# TestBoardTarget.net
KiCad netlist of a schematic drawn in EAGLE
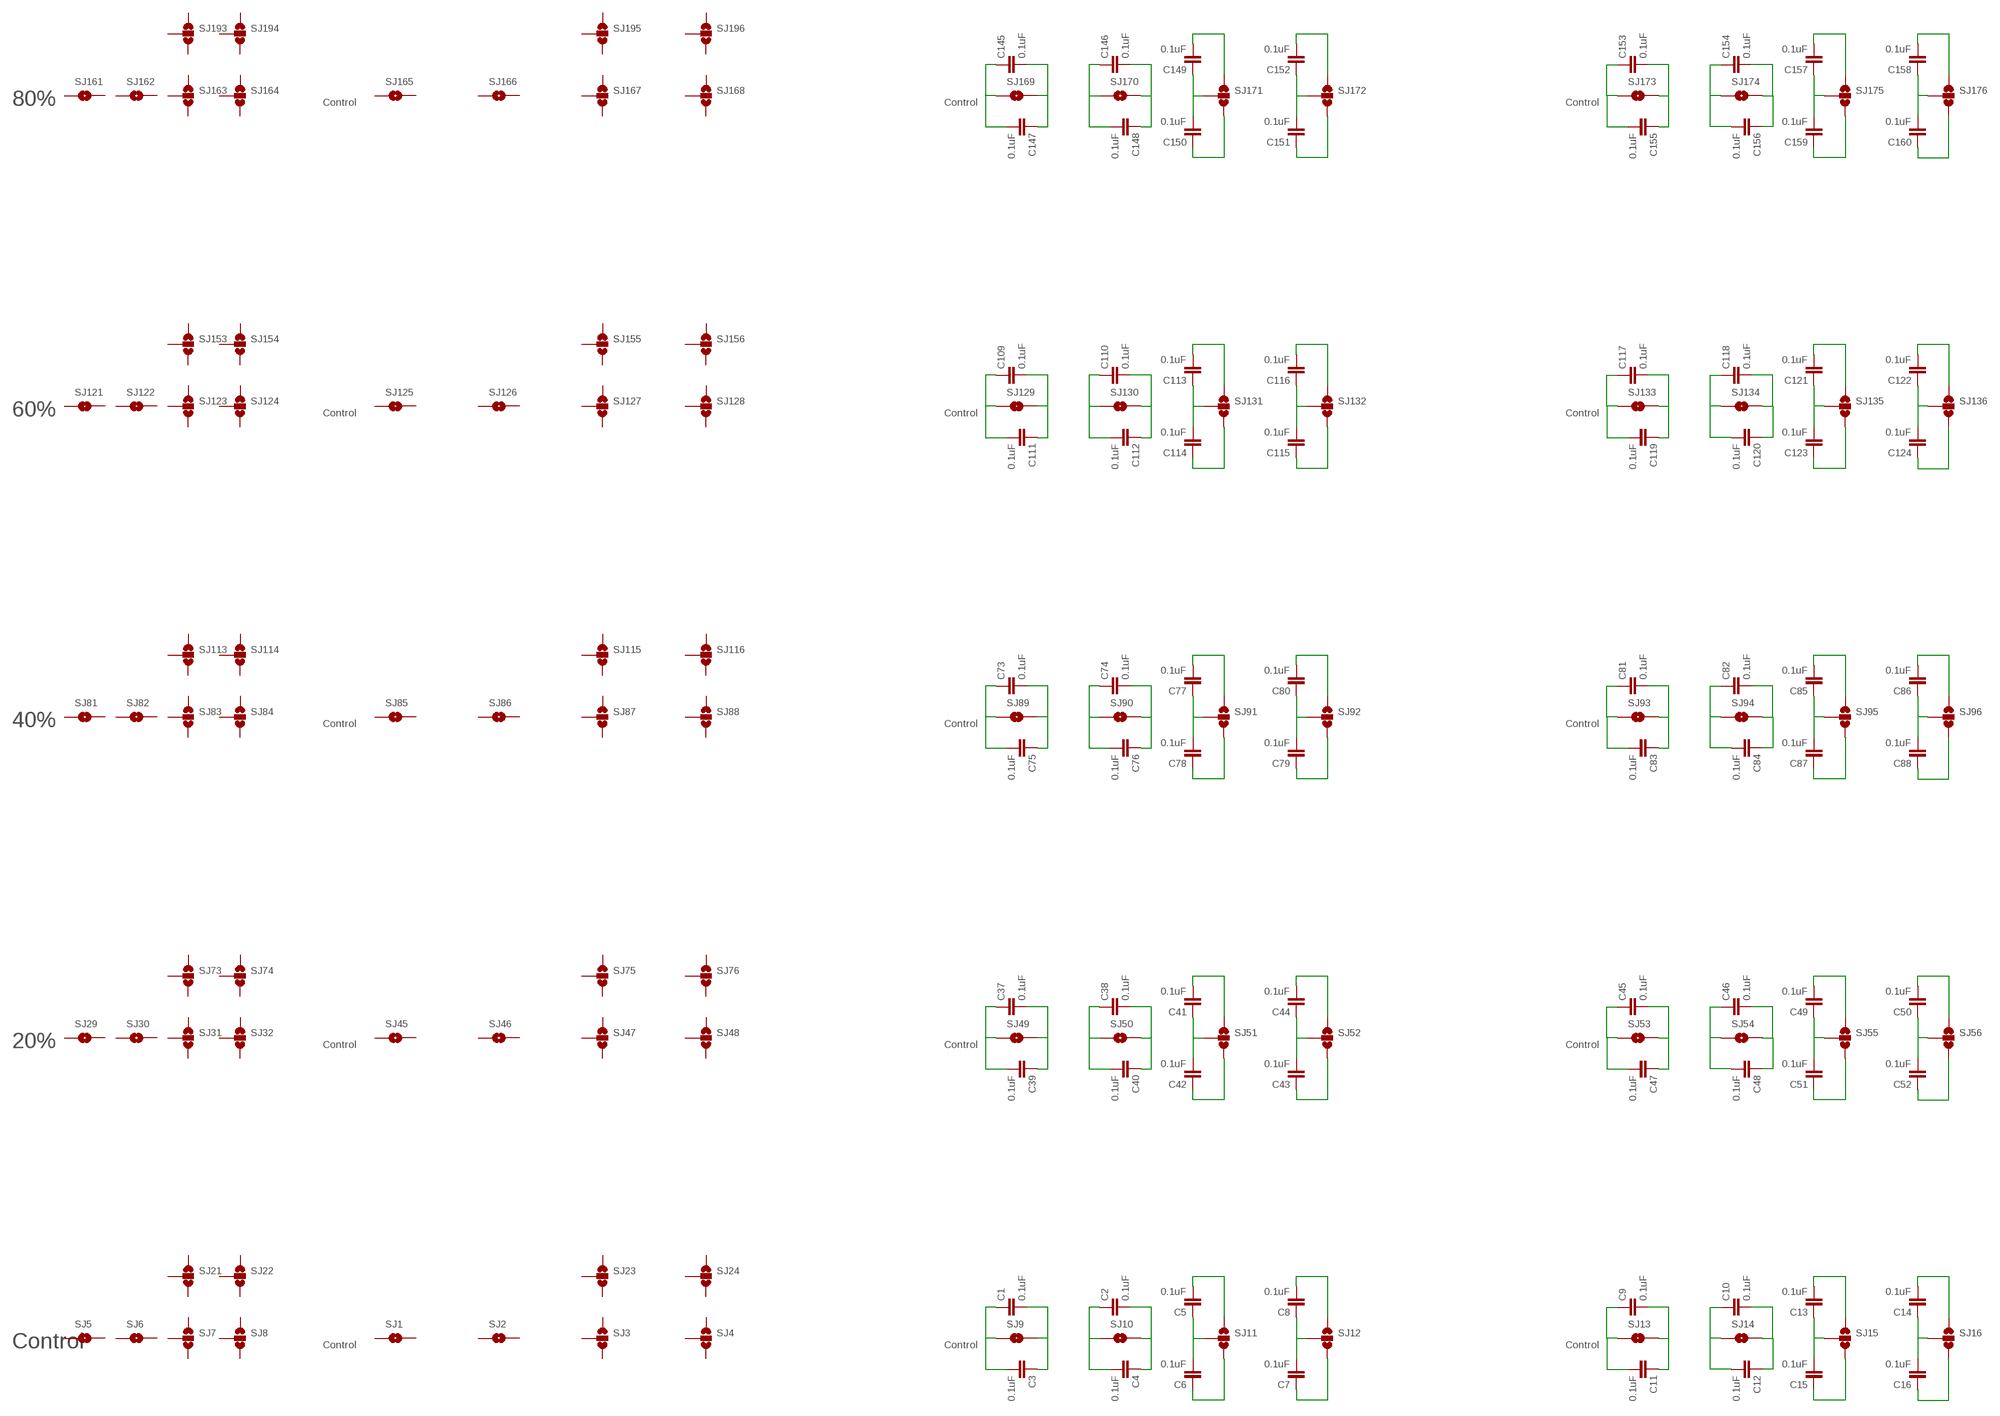
[diagram p0: schematic, sheet 1, part 1 of 3]
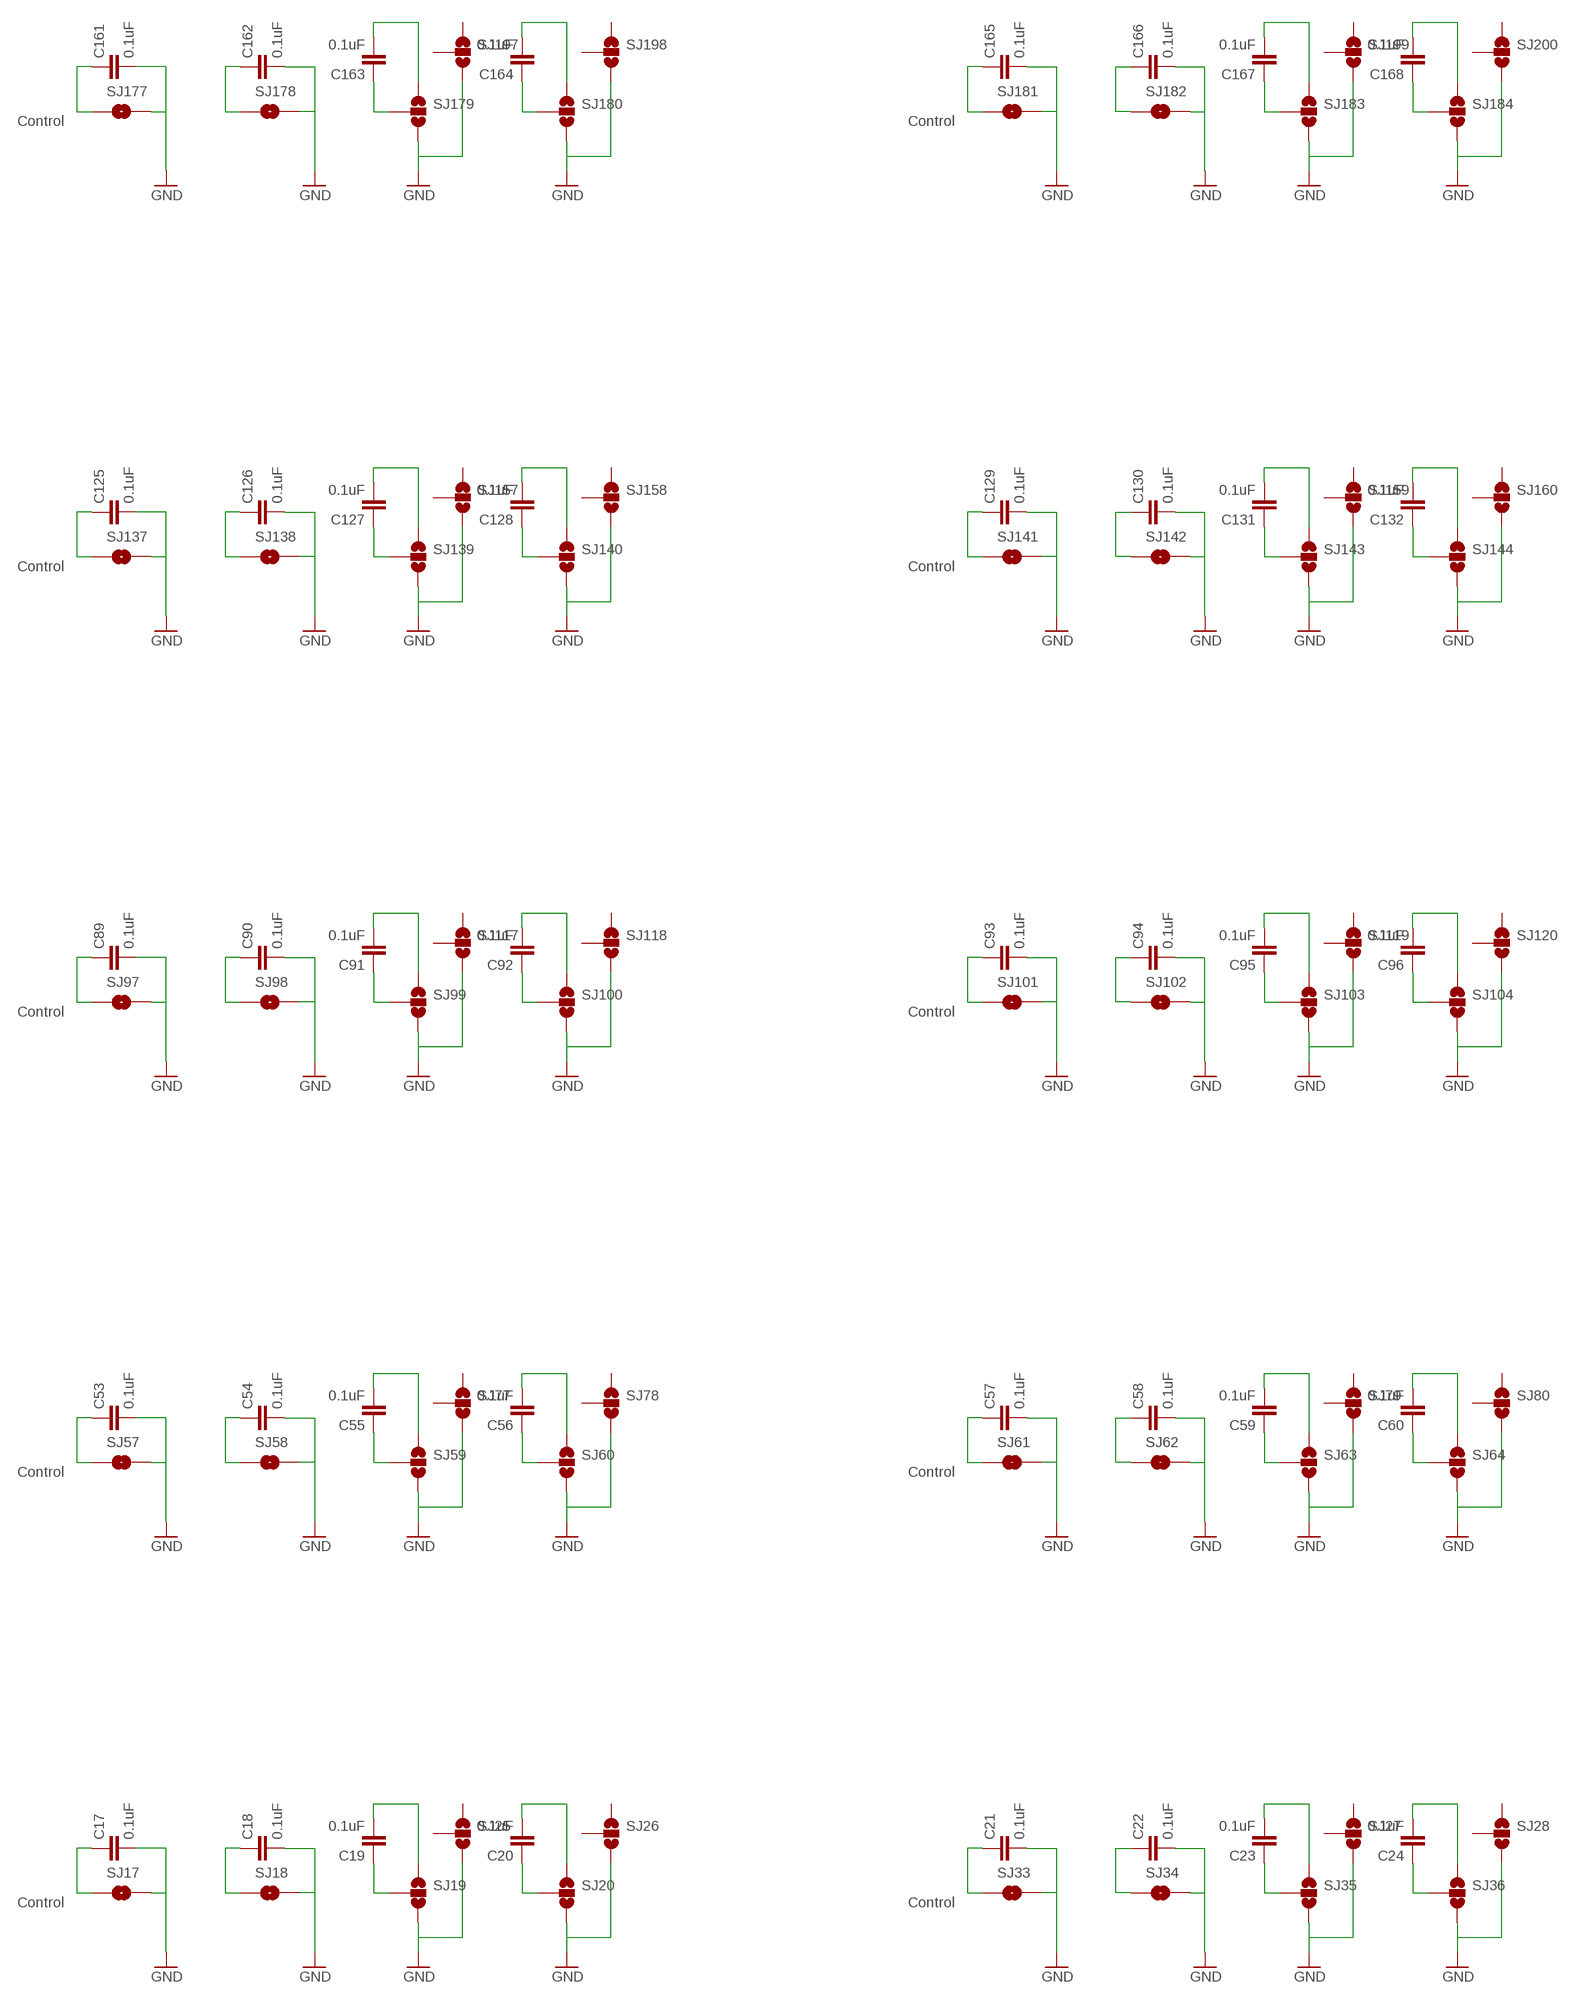
[diagram p1: schematic, sheet 1, part 2 of 3]
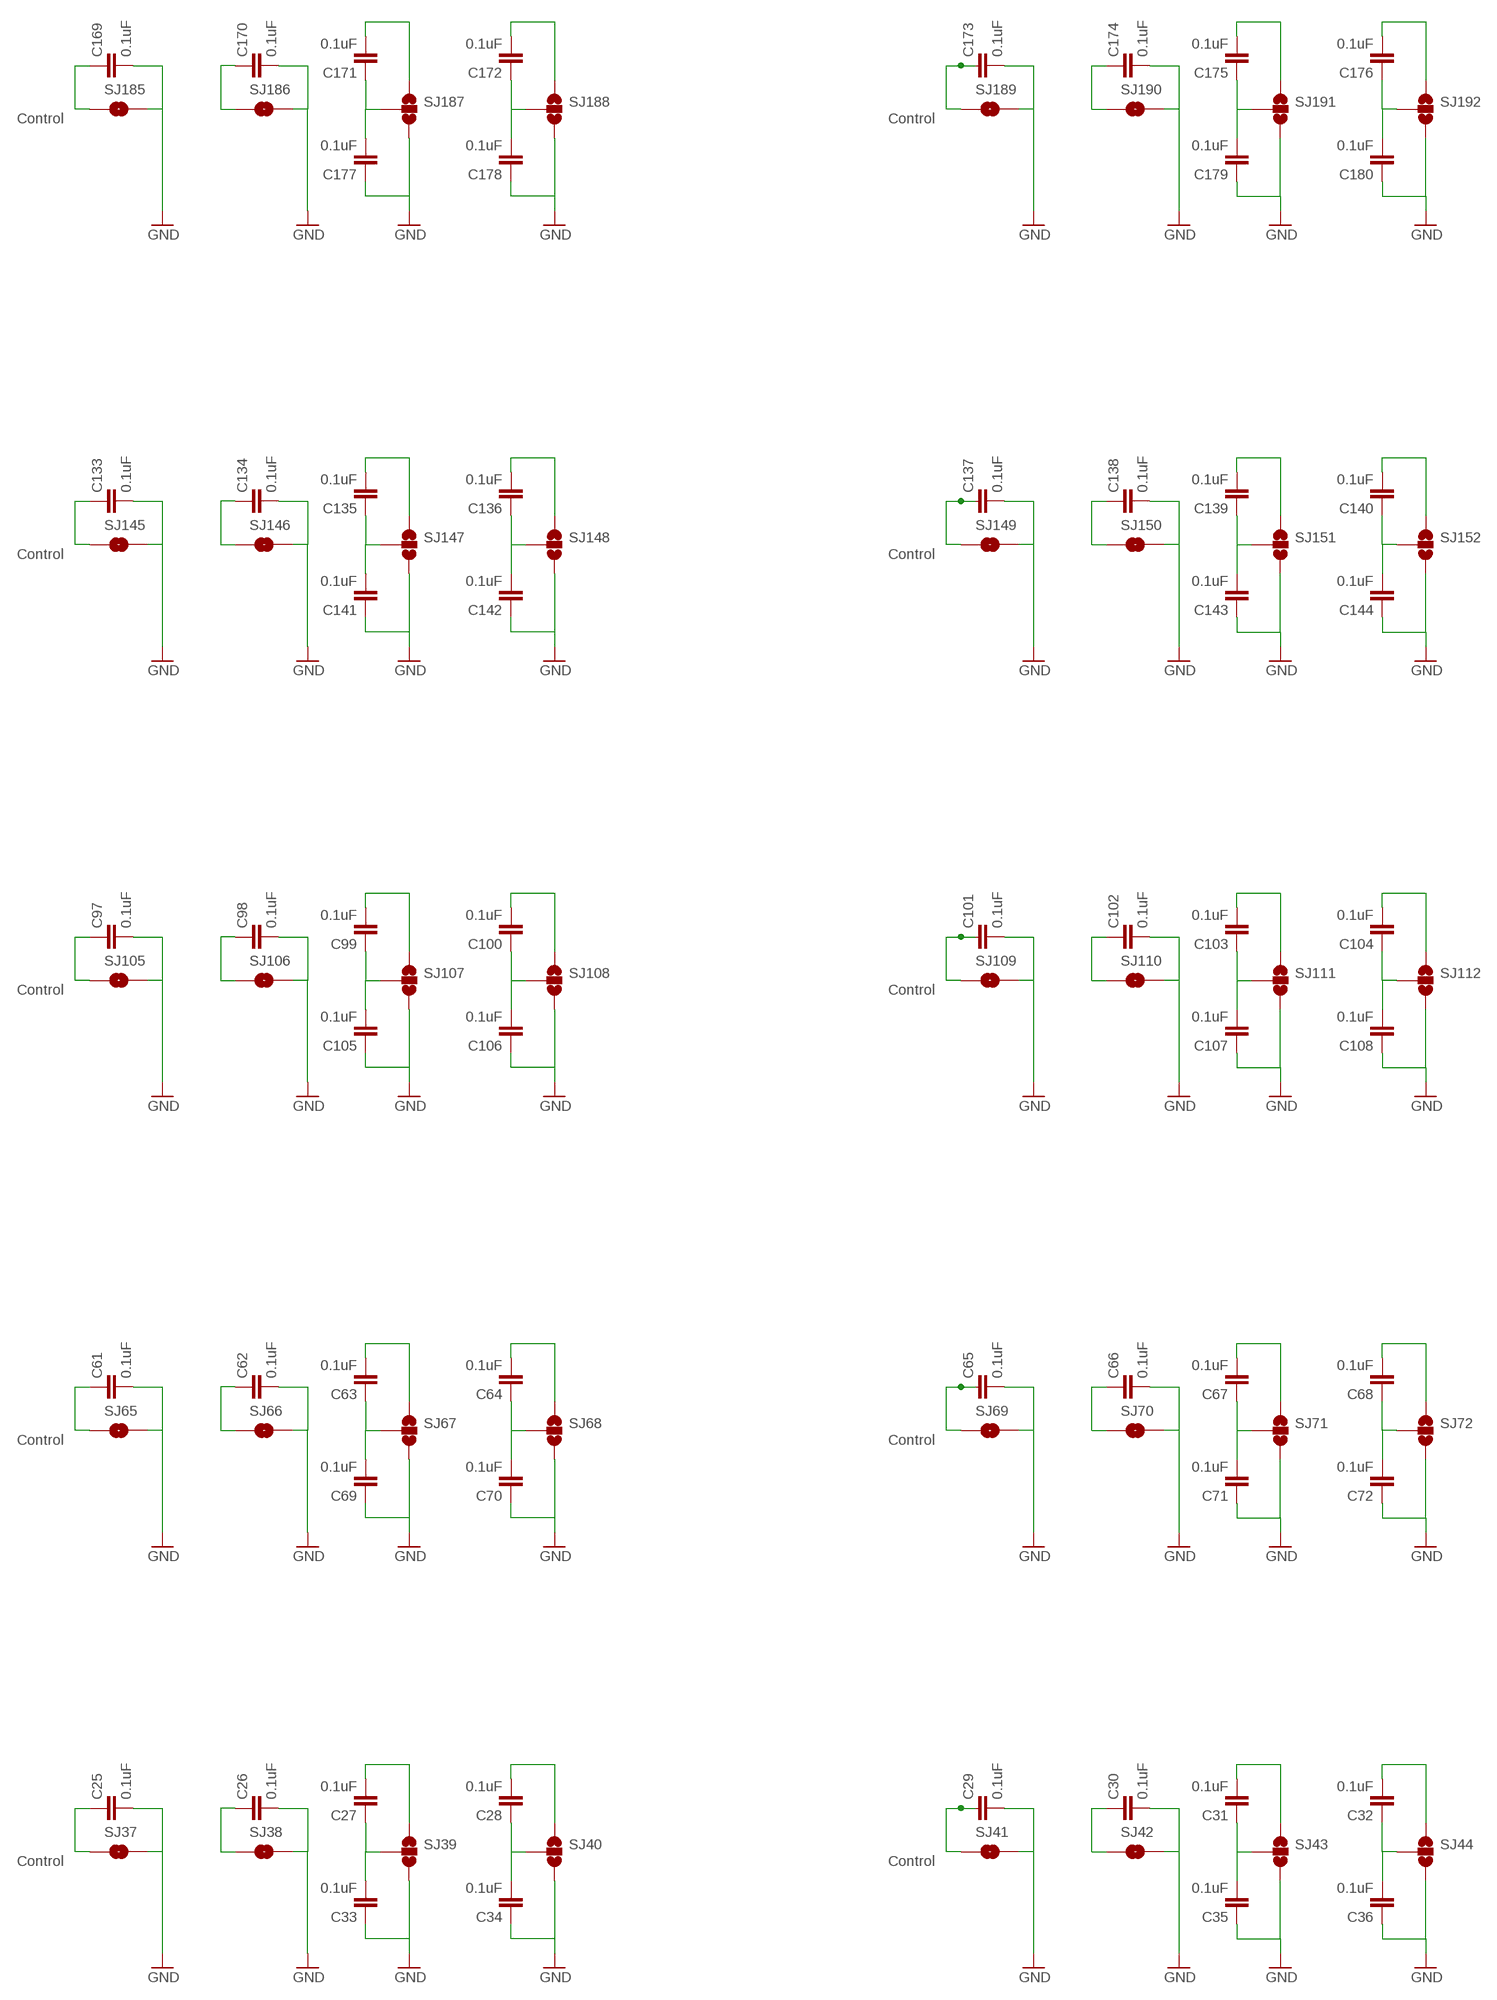
[diagram p2: schematic, sheet 1, part 3 of 3]

(export (version "E")
  (design (tool "Eeschema 10.0.6"))
  (components
    (comp (ref "C1")
      (value "0.1uF")
      (footprint "eagle-import:0603-CAP")
      (libsource (lib "eagle-import") (part "0.1UF-25V-5%(0603)"))
    )
    (comp (ref "C2")
      (value "0.1uF")
      (footprint "eagle-import:0603-CAP")
      (libsource (lib "eagle-import") (part "0.1UF-25V-5%(0603)"))
    )
    (comp (ref "C3")
      (value "0.1uF")
      (footprint "eagle-import:0603-CAP")
      (libsource (lib "eagle-import") (part "0.1UF-25V-5%(0603)"))
    )
    (comp (ref "C4")
      (value "0.1uF")
      (footprint "eagle-import:0603-CAP")
      (libsource (lib "eagle-import") (part "0.1UF-25V-5%(0603)"))
    )
    (comp (ref "C5")
      (value "0.1uF")
      (footprint "eagle-import:0603-CAP")
      (libsource (lib "eagle-import") (part "0.1UF-25V-5%(0603)"))
    )
    (comp (ref "C6")
      (value "0.1uF")
      (footprint "eagle-import:0603-CAP")
      (libsource (lib "eagle-import") (part "0.1UF-25V-5%(0603)"))
    )
    (comp (ref "C7")
      (value "0.1uF")
      (footprint "eagle-import:0603-CAP")
      (libsource (lib "eagle-import") (part "0.1UF-25V-5%(0603)"))
    )
    (comp (ref "C8")
      (value "0.1uF")
      (footprint "eagle-import:0603-CAP")
      (libsource (lib "eagle-import") (part "0.1UF-25V-5%(0603)"))
    )
    (comp (ref "C9")
      (value "0.1uF")
      (footprint "eagle-import:0603-CAP")
      (libsource (lib "eagle-import") (part "0.1UF-25V-5%(0603)"))
    )
    (comp (ref "C10")
      (value "0.1uF")
      (footprint "eagle-import:0603-CAP")
      (libsource (lib "eagle-import") (part "0.1UF-25V-5%(0603)"))
    )
    (comp (ref "C11")
      (value "0.1uF")
      (footprint "eagle-import:0603-CAP")
      (libsource (lib "eagle-import") (part "0.1UF-25V-5%(0603)"))
    )
    (comp (ref "C12")
      (value "0.1uF")
      (footprint "eagle-import:0603-CAP")
      (libsource (lib "eagle-import") (part "0.1UF-25V-5%(0603)"))
    )
    (comp (ref "C13")
      (value "0.1uF")
      (footprint "eagle-import:0603-CAP")
      (libsource (lib "eagle-import") (part "0.1UF-25V-5%(0603)"))
    )
    (comp (ref "C14")
      (value "0.1uF")
      (footprint "eagle-import:0603-CAP")
      (libsource (lib "eagle-import") (part "0.1UF-25V-5%(0603)"))
    )
    (comp (ref "C15")
      (value "0.1uF")
      (footprint "eagle-import:0603-CAP")
      (libsource (lib "eagle-import") (part "0.1UF-25V-5%(0603)"))
    )
    (comp (ref "C16")
      (value "0.1uF")
      (footprint "eagle-import:0603-CAP")
      (libsource (lib "eagle-import") (part "0.1UF-25V-5%(0603)"))
    )
    (comp (ref "C17")
      (value "0.1uF")
      (footprint "eagle-import:0603-CAP")
      (libsource (lib "eagle-import") (part "0.1UF-25V-5%(0603)"))
    )
    (comp (ref "C18")
      (value "0.1uF")
      (footprint "eagle-import:0603-CAP")
      (libsource (lib "eagle-import") (part "0.1UF-25V-5%(0603)"))
    )
    (comp (ref "C19")
      (value "0.1uF")
      (footprint "eagle-import:0603-CAP")
      (libsource (lib "eagle-import") (part "0.1UF-25V-5%(0603)"))
    )
    (comp (ref "C20")
      (value "0.1uF")
      (footprint "eagle-import:0603-CAP")
      (libsource (lib "eagle-import") (part "0.1UF-25V-5%(0603)"))
    )
    (comp (ref "C21")
      (value "0.1uF")
      (footprint "eagle-import:0603-CAP")
      (libsource (lib "eagle-import") (part "0.1UF-25V-5%(0603)"))
    )
    (comp (ref "C22")
      (value "0.1uF")
      (footprint "eagle-import:0603-CAP")
      (libsource (lib "eagle-import") (part "0.1UF-25V-5%(0603)"))
    )
    (comp (ref "C23")
      (value "0.1uF")
      (footprint "eagle-import:0603-CAP")
      (libsource (lib "eagle-import") (part "0.1UF-25V-5%(0603)"))
    )
    (comp (ref "C24")
      (value "0.1uF")
      (footprint "eagle-import:0603-CAP")
      (libsource (lib "eagle-import") (part "0.1UF-25V-5%(0603)"))
    )
    (comp (ref "C25")
      (value "0.1uF")
      (footprint "eagle-import:0603-CAP")
      (libsource (lib "eagle-import") (part "0.1UF-25V-5%(0603)"))
    )
    (comp (ref "C26")
      (value "0.1uF")
      (footprint "eagle-import:0603-CAP")
      (libsource (lib "eagle-import") (part "0.1UF-25V-5%(0603)"))
    )
    (comp (ref "C27")
      (value "0.1uF")
      (footprint "eagle-import:0603-CAP")
      (libsource (lib "eagle-import") (part "0.1UF-25V-5%(0603)"))
    )
    (comp (ref "C28")
      (value "0.1uF")
      (footprint "eagle-import:0603-CAP")
      (libsource (lib "eagle-import") (part "0.1UF-25V-5%(0603)"))
    )
    (comp (ref "C29")
      (value "0.1uF")
      (footprint "eagle-import:0603-CAP")
      (libsource (lib "eagle-import") (part "0.1UF-25V-5%(0603)"))
    )
    (comp (ref "C30")
      (value "0.1uF")
      (footprint "eagle-import:0603-CAP")
      (libsource (lib "eagle-import") (part "0.1UF-25V-5%(0603)"))
    )
    (comp (ref "C31")
      (value "0.1uF")
      (footprint "eagle-import:0603-CAP")
      (libsource (lib "eagle-import") (part "0.1UF-25V-5%(0603)"))
    )
    (comp (ref "C32")
      (value "0.1uF")
      (footprint "eagle-import:0603-CAP")
      (libsource (lib "eagle-import") (part "0.1UF-25V-5%(0603)"))
    )
    (comp (ref "C33")
      (value "0.1uF")
      (footprint "eagle-import:0603-CAP")
      (libsource (lib "eagle-import") (part "0.1UF-25V-5%(0603)"))
    )
    (comp (ref "C34")
      (value "0.1uF")
      (footprint "eagle-import:0603-CAP")
      (libsource (lib "eagle-import") (part "0.1UF-25V-5%(0603)"))
    )
    (comp (ref "C35")
      (value "0.1uF")
      (footprint "eagle-import:0603-CAP")
      (libsource (lib "eagle-import") (part "0.1UF-25V-5%(0603)"))
    )
    (comp (ref "C36")
      (value "0.1uF")
      (footprint "eagle-import:0603-CAP")
      (libsource (lib "eagle-import") (part "0.1UF-25V-5%(0603)"))
    )
    (comp (ref "C37")
      (value "0.1uF")
      (footprint "eagle-import:0603-CAP")
      (libsource (lib "eagle-import") (part "0.1UF-25V-5%(0603)"))
    )
    (comp (ref "C38")
      (value "0.1uF")
      (footprint "eagle-import:0603-CAP")
      (libsource (lib "eagle-import") (part "0.1UF-25V-5%(0603)"))
    )
    (comp (ref "C39")
      (value "0.1uF")
      (footprint "eagle-import:0603-CAP")
      (libsource (lib "eagle-import") (part "0.1UF-25V-5%(0603)"))
    )
    (comp (ref "C40")
      (value "0.1uF")
      (footprint "eagle-import:0603-CAP")
      (libsource (lib "eagle-import") (part "0.1UF-25V-5%(0603)"))
    )
    (comp (ref "C41")
      (value "0.1uF")
      (footprint "eagle-import:0603-CAP")
      (libsource (lib "eagle-import") (part "0.1UF-25V-5%(0603)"))
    )
    (comp (ref "C42")
      (value "0.1uF")
      (footprint "eagle-import:0603-CAP")
      (libsource (lib "eagle-import") (part "0.1UF-25V-5%(0603)"))
    )
    (comp (ref "C43")
      (value "0.1uF")
      (footprint "eagle-import:0603-CAP")
      (libsource (lib "eagle-import") (part "0.1UF-25V-5%(0603)"))
    )
    (comp (ref "C44")
      (value "0.1uF")
      (footprint "eagle-import:0603-CAP")
      (libsource (lib "eagle-import") (part "0.1UF-25V-5%(0603)"))
    )
    (comp (ref "C45")
      (value "0.1uF")
      (footprint "eagle-import:0603-CAP")
      (libsource (lib "eagle-import") (part "0.1UF-25V-5%(0603)"))
    )
    (comp (ref "C46")
      (value "0.1uF")
      (footprint "eagle-import:0603-CAP")
      (libsource (lib "eagle-import") (part "0.1UF-25V-5%(0603)"))
    )
    (comp (ref "C47")
      (value "0.1uF")
      (footprint "eagle-import:0603-CAP")
      (libsource (lib "eagle-import") (part "0.1UF-25V-5%(0603)"))
    )
    (comp (ref "C48")
      (value "0.1uF")
      (footprint "eagle-import:0603-CAP")
      (libsource (lib "eagle-import") (part "0.1UF-25V-5%(0603)"))
    )
    (comp (ref "C49")
      (value "0.1uF")
      (footprint "eagle-import:0603-CAP")
      (libsource (lib "eagle-import") (part "0.1UF-25V-5%(0603)"))
    )
    (comp (ref "C50")
      (value "0.1uF")
      (footprint "eagle-import:0603-CAP")
      (libsource (lib "eagle-import") (part "0.1UF-25V-5%(0603)"))
    )
    (comp (ref "C51")
      (value "0.1uF")
      (footprint "eagle-import:0603-CAP")
      (libsource (lib "eagle-import") (part "0.1UF-25V-5%(0603)"))
    )
    (comp (ref "C52")
      (value "0.1uF")
      (footprint "eagle-import:0603-CAP")
      (libsource (lib "eagle-import") (part "0.1UF-25V-5%(0603)"))
    )
    (comp (ref "C53")
      (value "0.1uF")
      (footprint "eagle-import:0603-CAP")
      (libsource (lib "eagle-import") (part "0.1UF-25V-5%(0603)"))
    )
    (comp (ref "C54")
      (value "0.1uF")
      (footprint "eagle-import:0603-CAP")
      (libsource (lib "eagle-import") (part "0.1UF-25V-5%(0603)"))
    )
    (comp (ref "C55")
      (value "0.1uF")
      (footprint "eagle-import:0603-CAP")
      (libsource (lib "eagle-import") (part "0.1UF-25V-5%(0603)"))
    )
    (comp (ref "C56")
      (value "0.1uF")
      (footprint "eagle-import:0603-CAP")
      (libsource (lib "eagle-import") (part "0.1UF-25V-5%(0603)"))
    )
    (comp (ref "C57")
      (value "0.1uF")
      (footprint "eagle-import:0603-CAP")
      (libsource (lib "eagle-import") (part "0.1UF-25V-5%(0603)"))
    )
    (comp (ref "C58")
      (value "0.1uF")
      (footprint "eagle-import:0603-CAP")
      (libsource (lib "eagle-import") (part "0.1UF-25V-5%(0603)"))
    )
    (comp (ref "C59")
      (value "0.1uF")
      (footprint "eagle-import:0603-CAP")
      (libsource (lib "eagle-import") (part "0.1UF-25V-5%(0603)"))
    )
    (comp (ref "C60")
      (value "0.1uF")
      (footprint "eagle-import:0603-CAP")
      (libsource (lib "eagle-import") (part "0.1UF-25V-5%(0603)"))
    )
    (comp (ref "C61")
      (value "0.1uF")
      (footprint "eagle-import:0603-CAP")
      (libsource (lib "eagle-import") (part "0.1UF-25V-5%(0603)"))
    )
    (comp (ref "C62")
      (value "0.1uF")
      (footprint "eagle-import:0603-CAP")
      (libsource (lib "eagle-import") (part "0.1UF-25V-5%(0603)"))
    )
    (comp (ref "C63")
      (value "0.1uF")
      (footprint "eagle-import:0603-CAP")
      (libsource (lib "eagle-import") (part "0.1UF-25V-5%(0603)"))
    )
    (comp (ref "C64")
      (value "0.1uF")
      (footprint "eagle-import:0603-CAP")
      (libsource (lib "eagle-import") (part "0.1UF-25V-5%(0603)"))
    )
    (comp (ref "C65")
      (value "0.1uF")
      (footprint "eagle-import:0603-CAP")
      (libsource (lib "eagle-import") (part "0.1UF-25V-5%(0603)"))
    )
    (comp (ref "C66")
      (value "0.1uF")
      (footprint "eagle-import:0603-CAP")
      (libsource (lib "eagle-import") (part "0.1UF-25V-5%(0603)"))
    )
    (comp (ref "C67")
      (value "0.1uF")
      (footprint "eagle-import:0603-CAP")
      (libsource (lib "eagle-import") (part "0.1UF-25V-5%(0603)"))
    )
    (comp (ref "C68")
      (value "0.1uF")
      (footprint "eagle-import:0603-CAP")
      (libsource (lib "eagle-import") (part "0.1UF-25V-5%(0603)"))
    )
    (comp (ref "C69")
      (value "0.1uF")
      (footprint "eagle-import:0603-CAP")
      (libsource (lib "eagle-import") (part "0.1UF-25V-5%(0603)"))
    )
    (comp (ref "C70")
      (value "0.1uF")
      (footprint "eagle-import:0603-CAP")
      (libsource (lib "eagle-import") (part "0.1UF-25V-5%(0603)"))
    )
    (comp (ref "C71")
      (value "0.1uF")
      (footprint "eagle-import:0603-CAP")
      (libsource (lib "eagle-import") (part "0.1UF-25V-5%(0603)"))
    )
    (comp (ref "C72")
      (value "0.1uF")
      (footprint "eagle-import:0603-CAP")
      (libsource (lib "eagle-import") (part "0.1UF-25V-5%(0603)"))
    )
    (comp (ref "C73")
      (value "0.1uF")
      (footprint "eagle-import:0603-CAP")
      (libsource (lib "eagle-import") (part "0.1UF-25V-5%(0603)"))
    )
    (comp (ref "C74")
      (value "0.1uF")
      (footprint "eagle-import:0603-CAP")
      (libsource (lib "eagle-import") (part "0.1UF-25V-5%(0603)"))
    )
    (comp (ref "C75")
      (value "0.1uF")
      (footprint "eagle-import:0603-CAP")
      (libsource (lib "eagle-import") (part "0.1UF-25V-5%(0603)"))
    )
    (comp (ref "C76")
      (value "0.1uF")
      (footprint "eagle-import:0603-CAP")
      (libsource (lib "eagle-import") (part "0.1UF-25V-5%(0603)"))
    )
    (comp (ref "C77")
      (value "0.1uF")
      (footprint "eagle-import:0603-CAP")
      (libsource (lib "eagle-import") (part "0.1UF-25V-5%(0603)"))
    )
    (comp (ref "C78")
      (value "0.1uF")
      (footprint "eagle-import:0603-CAP")
      (libsource (lib "eagle-import") (part "0.1UF-25V-5%(0603)"))
    )
    (comp (ref "C79")
      (value "0.1uF")
      (footprint "eagle-import:0603-CAP")
      (libsource (lib "eagle-import") (part "0.1UF-25V-5%(0603)"))
    )
    (comp (ref "C80")
      (value "0.1uF")
      (footprint "eagle-import:0603-CAP")
      (libsource (lib "eagle-import") (part "0.1UF-25V-5%(0603)"))
    )
    (comp (ref "C81")
      (value "0.1uF")
      (footprint "eagle-import:0603-CAP")
      (libsource (lib "eagle-import") (part "0.1UF-25V-5%(0603)"))
    )
    (comp (ref "C82")
      (value "0.1uF")
      (footprint "eagle-import:0603-CAP")
      (libsource (lib "eagle-import") (part "0.1UF-25V-5%(0603)"))
    )
    (comp (ref "C83")
      (value "0.1uF")
      (footprint "eagle-import:0603-CAP")
      (libsource (lib "eagle-import") (part "0.1UF-25V-5%(0603)"))
    )
    (comp (ref "C84")
      (value "0.1uF")
      (footprint "eagle-import:0603-CAP")
      (libsource (lib "eagle-import") (part "0.1UF-25V-5%(0603)"))
    )
    (comp (ref "C85")
      (value "0.1uF")
      (footprint "eagle-import:0603-CAP")
      (libsource (lib "eagle-import") (part "0.1UF-25V-5%(0603)"))
    )
    (comp (ref "C86")
      (value "0.1uF")
      (footprint "eagle-import:0603-CAP")
      (libsource (lib "eagle-import") (part "0.1UF-25V-5%(0603)"))
    )
    (comp (ref "C87")
      (value "0.1uF")
      (footprint "eagle-import:0603-CAP")
      (libsource (lib "eagle-import") (part "0.1UF-25V-5%(0603)"))
    )
    (comp (ref "C88")
      (value "0.1uF")
      (footprint "eagle-import:0603-CAP")
      (libsource (lib "eagle-import") (part "0.1UF-25V-5%(0603)"))
    )
    (comp (ref "C89")
      (value "0.1uF")
      (footprint "eagle-import:0603-CAP")
      (libsource (lib "eagle-import") (part "0.1UF-25V-5%(0603)"))
    )
    (comp (ref "C90")
      (value "0.1uF")
      (footprint "eagle-import:0603-CAP")
      (libsource (lib "eagle-import") (part "0.1UF-25V-5%(0603)"))
    )
    (comp (ref "C91")
      (value "0.1uF")
      (footprint "eagle-import:0603-CAP")
      (libsource (lib "eagle-import") (part "0.1UF-25V-5%(0603)"))
    )
    (comp (ref "C92")
      (value "0.1uF")
      (footprint "eagle-import:0603-CAP")
      (libsource (lib "eagle-import") (part "0.1UF-25V-5%(0603)"))
    )
    (comp (ref "C93")
      (value "0.1uF")
      (footprint "eagle-import:0603-CAP")
      (libsource (lib "eagle-import") (part "0.1UF-25V-5%(0603)"))
    )
    (comp (ref "C94")
      (value "0.1uF")
      (footprint "eagle-import:0603-CAP")
      (libsource (lib "eagle-import") (part "0.1UF-25V-5%(0603)"))
    )
    (comp (ref "C95")
      (value "0.1uF")
      (footprint "eagle-import:0603-CAP")
      (libsource (lib "eagle-import") (part "0.1UF-25V-5%(0603)"))
    )
    (comp (ref "C96")
      (value "0.1uF")
      (footprint "eagle-import:0603-CAP")
      (libsource (lib "eagle-import") (part "0.1UF-25V-5%(0603)"))
    )
    (comp (ref "C97")
      (value "0.1uF")
      (footprint "eagle-import:0603-CAP")
      (libsource (lib "eagle-import") (part "0.1UF-25V-5%(0603)"))
    )
    (comp (ref "C98")
      (value "0.1uF")
      (footprint "eagle-import:0603-CAP")
      (libsource (lib "eagle-import") (part "0.1UF-25V-5%(0603)"))
    )
    (comp (ref "C99")
      (value "0.1uF")
      (footprint "eagle-import:0603-CAP")
      (libsource (lib "eagle-import") (part "0.1UF-25V-5%(0603)"))
    )
    (comp (ref "C100")
      (value "0.1uF")
      (footprint "eagle-import:0603-CAP")
      (libsource (lib "eagle-import") (part "0.1UF-25V-5%(0603)"))
    )
    (comp (ref "C101")
      (value "0.1uF")
      (footprint "eagle-import:0603-CAP")
      (libsource (lib "eagle-import") (part "0.1UF-25V-5%(0603)"))
    )
    (comp (ref "C102")
      (value "0.1uF")
      (footprint "eagle-import:0603-CAP")
      (libsource (lib "eagle-import") (part "0.1UF-25V-5%(0603)"))
    )
    (comp (ref "C103")
      (value "0.1uF")
      (footprint "eagle-import:0603-CAP")
      (libsource (lib "eagle-import") (part "0.1UF-25V-5%(0603)"))
    )
    (comp (ref "C104")
      (value "0.1uF")
      (footprint "eagle-import:0603-CAP")
      (libsource (lib "eagle-import") (part "0.1UF-25V-5%(0603)"))
    )
    (comp (ref "C105")
      (value "0.1uF")
      (footprint "eagle-import:0603-CAP")
      (libsource (lib "eagle-import") (part "0.1UF-25V-5%(0603)"))
    )
    (comp (ref "C106")
      (value "0.1uF")
      (footprint "eagle-import:0603-CAP")
      (libsource (lib "eagle-import") (part "0.1UF-25V-5%(0603)"))
    )
    (comp (ref "C107")
      (value "0.1uF")
      (footprint "eagle-import:0603-CAP")
      (libsource (lib "eagle-import") (part "0.1UF-25V-5%(0603)"))
    )
    (comp (ref "C108")
      (value "0.1uF")
      (footprint "eagle-import:0603-CAP")
      (libsource (lib "eagle-import") (part "0.1UF-25V-5%(0603)"))
    )
    (comp (ref "C109")
      (value "0.1uF")
      (footprint "eagle-import:0603-CAP")
      (libsource (lib "eagle-import") (part "0.1UF-25V-5%(0603)"))
    )
    (comp (ref "C110")
      (value "0.1uF")
      (footprint "eagle-import:0603-CAP")
      (libsource (lib "eagle-import") (part "0.1UF-25V-5%(0603)"))
    )
    (comp (ref "C111")
      (value "0.1uF")
      (footprint "eagle-import:0603-CAP")
      (libsource (lib "eagle-import") (part "0.1UF-25V-5%(0603)"))
    )
    (comp (ref "C112")
      (value "0.1uF")
      (footprint "eagle-import:0603-CAP")
      (libsource (lib "eagle-import") (part "0.1UF-25V-5%(0603)"))
    )
    (comp (ref "C113")
      (value "0.1uF")
      (footprint "eagle-import:0603-CAP")
      (libsource (lib "eagle-import") (part "0.1UF-25V-5%(0603)"))
    )
    (comp (ref "C114")
      (value "0.1uF")
      (footprint "eagle-import:0603-CAP")
      (libsource (lib "eagle-import") (part "0.1UF-25V-5%(0603)"))
    )
    (comp (ref "C115")
      (value "0.1uF")
      (footprint "eagle-import:0603-CAP")
      (libsource (lib "eagle-import") (part "0.1UF-25V-5%(0603)"))
    )
    (comp (ref "C116")
      (value "0.1uF")
      (footprint "eagle-import:0603-CAP")
      (libsource (lib "eagle-import") (part "0.1UF-25V-5%(0603)"))
    )
    (comp (ref "C117")
      (value "0.1uF")
      (footprint "eagle-import:0603-CAP")
      (libsource (lib "eagle-import") (part "0.1UF-25V-5%(0603)"))
    )
    (comp (ref "C118")
      (value "0.1uF")
      (footprint "eagle-import:0603-CAP")
      (libsource (lib "eagle-import") (part "0.1UF-25V-5%(0603)"))
    )
    (comp (ref "C119")
      (value "0.1uF")
      (footprint "eagle-import:0603-CAP")
      (libsource (lib "eagle-import") (part "0.1UF-25V-5%(0603)"))
    )
    (comp (ref "C120")
      (value "0.1uF")
      (footprint "eagle-import:0603-CAP")
      (libsource (lib "eagle-import") (part "0.1UF-25V-5%(0603)"))
    )
    (comp (ref "C121")
      (value "0.1uF")
      (footprint "eagle-import:0603-CAP")
      (libsource (lib "eagle-import") (part "0.1UF-25V-5%(0603)"))
    )
    (comp (ref "C122")
      (value "0.1uF")
      (footprint "eagle-import:0603-CAP")
      (libsource (lib "eagle-import") (part "0.1UF-25V-5%(0603)"))
    )
    (comp (ref "C123")
      (value "0.1uF")
      (footprint "eagle-import:0603-CAP")
      (libsource (lib "eagle-import") (part "0.1UF-25V-5%(0603)"))
    )
    (comp (ref "C124")
      (value "0.1uF")
      (footprint "eagle-import:0603-CAP")
      (libsource (lib "eagle-import") (part "0.1UF-25V-5%(0603)"))
    )
    (comp (ref "C125")
      (value "0.1uF")
      (footprint "eagle-import:0603-CAP")
      (libsource (lib "eagle-import") (part "0.1UF-25V-5%(0603)"))
    )
    (comp (ref "C126")
      (value "0.1uF")
      (footprint "eagle-import:0603-CAP")
      (libsource (lib "eagle-import") (part "0.1UF-25V-5%(0603)"))
    )
    (comp (ref "C127")
      (value "0.1uF")
      (footprint "eagle-import:0603-CAP")
      (libsource (lib "eagle-import") (part "0.1UF-25V-5%(0603)"))
    )
    (comp (ref "C128")
      (value "0.1uF")
      (footprint "eagle-import:0603-CAP")
      (libsource (lib "eagle-import") (part "0.1UF-25V-5%(0603)"))
    )
    (comp (ref "C129")
      (value "0.1uF")
      (footprint "eagle-import:0603-CAP")
      (libsource (lib "eagle-import") (part "0.1UF-25V-5%(0603)"))
    )
    (comp (ref "C130")
      (value "0.1uF")
      (footprint "eagle-import:0603-CAP")
      (libsource (lib "eagle-import") (part "0.1UF-25V-5%(0603)"))
    )
    (comp (ref "C131")
      (value "0.1uF")
      (footprint "eagle-import:0603-CAP")
      (libsource (lib "eagle-import") (part "0.1UF-25V-5%(0603)"))
    )
    (comp (ref "C132")
      (value "0.1uF")
      (footprint "eagle-import:0603-CAP")
      (libsource (lib "eagle-import") (part "0.1UF-25V-5%(0603)"))
    )
    (comp (ref "C133")
      (value "0.1uF")
      (footprint "eagle-import:0603-CAP")
      (libsource (lib "eagle-import") (part "0.1UF-25V-5%(0603)"))
    )
    (comp (ref "C134")
      (value "0.1uF")
      (footprint "eagle-import:0603-CAP")
      (libsource (lib "eagle-import") (part "0.1UF-25V-5%(0603)"))
    )
    (comp (ref "C135")
      (value "0.1uF")
      (footprint "eagle-import:0603-CAP")
      (libsource (lib "eagle-import") (part "0.1UF-25V-5%(0603)"))
    )
    (comp (ref "C136")
      (value "0.1uF")
      (footprint "eagle-import:0603-CAP")
      (libsource (lib "eagle-import") (part "0.1UF-25V-5%(0603)"))
    )
    (comp (ref "C137")
      (value "0.1uF")
      (footprint "eagle-import:0603-CAP")
      (libsource (lib "eagle-import") (part "0.1UF-25V-5%(0603)"))
    )
    (comp (ref "C138")
      (value "0.1uF")
      (footprint "eagle-import:0603-CAP")
      (libsource (lib "eagle-import") (part "0.1UF-25V-5%(0603)"))
    )
    (comp (ref "C139")
      (value "0.1uF")
      (footprint "eagle-import:0603-CAP")
      (libsource (lib "eagle-import") (part "0.1UF-25V-5%(0603)"))
    )
    (comp (ref "C140")
      (value "0.1uF")
      (footprint "eagle-import:0603-CAP")
      (libsource (lib "eagle-import") (part "0.1UF-25V-5%(0603)"))
    )
    (comp (ref "C141")
      (value "0.1uF")
      (footprint "eagle-import:0603-CAP")
      (libsource (lib "eagle-import") (part "0.1UF-25V-5%(0603)"))
    )
    (comp (ref "C142")
      (value "0.1uF")
      (footprint "eagle-import:0603-CAP")
      (libsource (lib "eagle-import") (part "0.1UF-25V-5%(0603)"))
    )
    (comp (ref "C143")
      (value "0.1uF")
      (footprint "eagle-import:0603-CAP")
      (libsource (lib "eagle-import") (part "0.1UF-25V-5%(0603)"))
    )
    (comp (ref "C144")
      (value "0.1uF")
      (footprint "eagle-import:0603-CAP")
      (libsource (lib "eagle-import") (part "0.1UF-25V-5%(0603)"))
    )
    (comp (ref "C145")
      (value "0.1uF")
      (footprint "eagle-import:0603-CAP")
      (libsource (lib "eagle-import") (part "0.1UF-25V-5%(0603)"))
    )
    (comp (ref "C146")
      (value "0.1uF")
      (footprint "eagle-import:0603-CAP")
      (libsource (lib "eagle-import") (part "0.1UF-25V-5%(0603)"))
    )
    (comp (ref "C147")
      (value "0.1uF")
      (footprint "eagle-import:0603-CAP")
      (libsource (lib "eagle-import") (part "0.1UF-25V-5%(0603)"))
    )
    (comp (ref "C148")
      (value "0.1uF")
      (footprint "eagle-import:0603-CAP")
      (libsource (lib "eagle-import") (part "0.1UF-25V-5%(0603)"))
    )
    (comp (ref "C149")
      (value "0.1uF")
      (footprint "eagle-import:0603-CAP")
      (libsource (lib "eagle-import") (part "0.1UF-25V-5%(0603)"))
    )
    (comp (ref "C150")
      (value "0.1uF")
      (footprint "eagle-import:0603-CAP")
      (libsource (lib "eagle-import") (part "0.1UF-25V-5%(0603)"))
    )
    (comp (ref "C151")
      (value "0.1uF")
      (footprint "eagle-import:0603-CAP")
      (libsource (lib "eagle-import") (part "0.1UF-25V-5%(0603)"))
    )
    (comp (ref "C152")
      (value "0.1uF")
      (footprint "eagle-import:0603-CAP")
      (libsource (lib "eagle-import") (part "0.1UF-25V-5%(0603)"))
    )
    (comp (ref "C153")
      (value "0.1uF")
      (footprint "eagle-import:0603-CAP")
      (libsource (lib "eagle-import") (part "0.1UF-25V-5%(0603)"))
    )
    (comp (ref "C154")
      (value "0.1uF")
      (footprint "eagle-import:0603-CAP")
      (libsource (lib "eagle-import") (part "0.1UF-25V-5%(0603)"))
    )
    (comp (ref "C155")
      (value "0.1uF")
      (footprint "eagle-import:0603-CAP")
      (libsource (lib "eagle-import") (part "0.1UF-25V-5%(0603)"))
    )
    (comp (ref "C156")
      (value "0.1uF")
      (footprint "eagle-import:0603-CAP")
      (libsource (lib "eagle-import") (part "0.1UF-25V-5%(0603)"))
    )
    (comp (ref "C157")
      (value "0.1uF")
      (footprint "eagle-import:0603-CAP")
      (libsource (lib "eagle-import") (part "0.1UF-25V-5%(0603)"))
    )
    (comp (ref "C158")
      (value "0.1uF")
      (footprint "eagle-import:0603-CAP")
      (libsource (lib "eagle-import") (part "0.1UF-25V-5%(0603)"))
    )
    (comp (ref "C159")
      (value "0.1uF")
      (footprint "eagle-import:0603-CAP")
      (libsource (lib "eagle-import") (part "0.1UF-25V-5%(0603)"))
    )
    (comp (ref "C160")
      (value "0.1uF")
      (footprint "eagle-import:0603-CAP")
      (libsource (lib "eagle-import") (part "0.1UF-25V-5%(0603)"))
    )
    (comp (ref "C161")
      (value "0.1uF")
      (footprint "eagle-import:0603-CAP")
      (libsource (lib "eagle-import") (part "0.1UF-25V-5%(0603)"))
    )
    (comp (ref "C162")
      (value "0.1uF")
      (footprint "eagle-import:0603-CAP")
      (libsource (lib "eagle-import") (part "0.1UF-25V-5%(0603)"))
    )
    (comp (ref "C163")
      (value "0.1uF")
      (footprint "eagle-import:0603-CAP")
      (libsource (lib "eagle-import") (part "0.1UF-25V-5%(0603)"))
    )
    (comp (ref "C164")
      (value "0.1uF")
      (footprint "eagle-import:0603-CAP")
      (libsource (lib "eagle-import") (part "0.1UF-25V-5%(0603)"))
    )
    (comp (ref "C165")
      (value "0.1uF")
      (footprint "eagle-import:0603-CAP")
      (libsource (lib "eagle-import") (part "0.1UF-25V-5%(0603)"))
    )
    (comp (ref "C166")
      (value "0.1uF")
      (footprint "eagle-import:0603-CAP")
      (libsource (lib "eagle-import") (part "0.1UF-25V-5%(0603)"))
    )
    (comp (ref "C167")
      (value "0.1uF")
      (footprint "eagle-import:0603-CAP")
      (libsource (lib "eagle-import") (part "0.1UF-25V-5%(0603)"))
    )
    (comp (ref "C168")
      (value "0.1uF")
      (footprint "eagle-import:0603-CAP")
      (libsource (lib "eagle-import") (part "0.1UF-25V-5%(0603)"))
    )
    (comp (ref "C169")
      (value "0.1uF")
      (footprint "eagle-import:0603-CAP")
      (libsource (lib "eagle-import") (part "0.1UF-25V-5%(0603)"))
    )
    (comp (ref "C170")
      (value "0.1uF")
      (footprint "eagle-import:0603-CAP")
      (libsource (lib "eagle-import") (part "0.1UF-25V-5%(0603)"))
    )
    (comp (ref "C171")
      (value "0.1uF")
      (footprint "eagle-import:0603-CAP")
      (libsource (lib "eagle-import") (part "0.1UF-25V-5%(0603)"))
    )
    (comp (ref "C172")
      (value "0.1uF")
      (footprint "eagle-import:0603-CAP")
      (libsource (lib "eagle-import") (part "0.1UF-25V-5%(0603)"))
    )
    (comp (ref "C173")
      (value "0.1uF")
      (footprint "eagle-import:0603-CAP")
      (libsource (lib "eagle-import") (part "0.1UF-25V-5%(0603)"))
    )
    (comp (ref "C174")
      (value "0.1uF")
      (footprint "eagle-import:0603-CAP")
      (libsource (lib "eagle-import") (part "0.1UF-25V-5%(0603)"))
    )
    (comp (ref "C175")
      (value "0.1uF")
      (footprint "eagle-import:0603-CAP")
      (libsource (lib "eagle-import") (part "0.1UF-25V-5%(0603)"))
    )
    (comp (ref "C176")
      (value "0.1uF")
      (footprint "eagle-import:0603-CAP")
      (libsource (lib "eagle-import") (part "0.1UF-25V-5%(0603)"))
    )
    (comp (ref "C177")
      (value "0.1uF")
      (footprint "eagle-import:0603-CAP")
      (libsource (lib "eagle-import") (part "0.1UF-25V-5%(0603)"))
    )
    (comp (ref "C178")
      (value "0.1uF")
      (footprint "eagle-import:0603-CAP")
      (libsource (lib "eagle-import") (part "0.1UF-25V-5%(0603)"))
    )
    (comp (ref "C179")
      (value "0.1uF")
      (footprint "eagle-import:0603-CAP")
      (libsource (lib "eagle-import") (part "0.1UF-25V-5%(0603)"))
    )
    (comp (ref "C180")
      (value "0.1uF")
      (footprint "eagle-import:0603-CAP")
      (libsource (lib "eagle-import") (part "0.1UF-25V-5%(0603)"))
    )
    (comp (ref "SJ1")
      (value "JUMPER-PAD-2-NO")
      (footprint "eagle-import:PAD-JUMPER-2-NO_NO_SILK")
      (libsource (lib "eagle-import") (part "JUMPER-PAD-2-NO"))
    )
    (comp (ref "SJ2")
      (value "JUMPER-PAD-2-NO")
      (footprint "eagle-import:PAD-JUMPER-2-NO_NO_SILK")
      (libsource (lib "eagle-import") (part "JUMPER-PAD-2-NO"))
    )
    (comp (ref "SJ3")
      (value "JUMPER-PAD-3-NOYES_SILK")
      (footprint "eagle-import:PAD-JUMPER-3-NO_YES_SILK")
      (libsource (lib "eagle-import") (part "JUMPER-PAD-3-NOYES_SILK"))
    )
    (comp (ref "SJ4")
      (value "JUMPER-PAD-3-NOYES_SILK")
      (footprint "eagle-import:PAD-JUMPER-3-NO_YES_SILK")
      (libsource (lib "eagle-import") (part "JUMPER-PAD-3-NOYES_SILK"))
    )
    (comp (ref "SJ5")
      (value "JUMPER-PAD-2-NO")
      (footprint "eagle-import:PAD-JUMPER-2-NO_NO_SILK")
      (libsource (lib "eagle-import") (part "JUMPER-PAD-2-NO"))
    )
    (comp (ref "SJ6")
      (value "JUMPER-PAD-2-NO")
      (footprint "eagle-import:PAD-JUMPER-2-NO_NO_SILK")
      (libsource (lib "eagle-import") (part "JUMPER-PAD-2-NO"))
    )
    (comp (ref "SJ7")
      (value "JUMPER-PAD-3-NOYES_SILK")
      (footprint "eagle-import:PAD-JUMPER-3-NO_YES_SILK")
      (libsource (lib "eagle-import") (part "JUMPER-PAD-3-NOYES_SILK"))
    )
    (comp (ref "SJ8")
      (value "JUMPER-PAD-3-NOYES_SILK")
      (footprint "eagle-import:PAD-JUMPER-3-NO_YES_SILK")
      (libsource (lib "eagle-import") (part "JUMPER-PAD-3-NOYES_SILK"))
    )
    (comp (ref "SJ9")
      (value "JUMPER-PAD-2-NO")
      (footprint "eagle-import:PAD-JUMPER-2-NO_NO_SILK")
      (libsource (lib "eagle-import") (part "JUMPER-PAD-2-NO"))
    )
    (comp (ref "SJ10")
      (value "JUMPER-PAD-2-NO")
      (footprint "eagle-import:PAD-JUMPER-2-NO_NO_SILK")
      (libsource (lib "eagle-import") (part "JUMPER-PAD-2-NO"))
    )
    (comp (ref "SJ11")
      (value "JUMPER-PAD-3-NOYES_SILK")
      (footprint "eagle-import:PAD-JUMPER-3-NO_YES_SILK")
      (libsource (lib "eagle-import") (part "JUMPER-PAD-3-NOYES_SILK"))
    )
    (comp (ref "SJ12")
      (value "JUMPER-PAD-3-NOYES_SILK")
      (footprint "eagle-import:PAD-JUMPER-3-NO_YES_SILK")
      (libsource (lib "eagle-import") (part "JUMPER-PAD-3-NOYES_SILK"))
    )
    (comp (ref "SJ13")
      (value "JUMPER-PAD-2-NO")
      (footprint "eagle-import:PAD-JUMPER-2-NO_NO_SILK")
      (libsource (lib "eagle-import") (part "JUMPER-PAD-2-NO"))
    )
    (comp (ref "SJ14")
      (value "JUMPER-PAD-2-NO")
      (footprint "eagle-import:PAD-JUMPER-2-NO_NO_SILK")
      (libsource (lib "eagle-import") (part "JUMPER-PAD-2-NO"))
    )
    (comp (ref "SJ15")
      (value "JUMPER-PAD-3-NOYES_SILK")
      (footprint "eagle-import:PAD-JUMPER-3-NO_YES_SILK")
      (libsource (lib "eagle-import") (part "JUMPER-PAD-3-NOYES_SILK"))
    )
    (comp (ref "SJ16")
      (value "JUMPER-PAD-3-NOYES_SILK")
      (footprint "eagle-import:PAD-JUMPER-3-NO_YES_SILK")
      (libsource (lib "eagle-import") (part "JUMPER-PAD-3-NOYES_SILK"))
    )
    (comp (ref "SJ17")
      (value "JUMPER-PAD-2-NO")
      (footprint "eagle-import:PAD-JUMPER-2-NO_NO_SILK")
      (libsource (lib "eagle-import") (part "JUMPER-PAD-2-NO"))
    )
    (comp (ref "SJ18")
      (value "JUMPER-PAD-2-NO")
      (footprint "eagle-import:PAD-JUMPER-2-NO_NO_SILK")
      (libsource (lib "eagle-import") (part "JUMPER-PAD-2-NO"))
    )
    (comp (ref "SJ19")
      (value "JUMPER-PAD-3-NOYES_SILK")
      (footprint "eagle-import:PAD-JUMPER-3-NO_YES_SILK")
      (libsource (lib "eagle-import") (part "JUMPER-PAD-3-NOYES_SILK"))
    )
    (comp (ref "SJ20")
      (value "JUMPER-PAD-3-NOYES_SILK")
      (footprint "eagle-import:PAD-JUMPER-3-NO_YES_SILK")
      (libsource (lib "eagle-import") (part "JUMPER-PAD-3-NOYES_SILK"))
    )
    (comp (ref "SJ21")
      (value "JUMPER-PAD-3-NOYES_SILK")
      (footprint "eagle-import:PAD-JUMPER-3-NO_YES_SILK")
      (libsource (lib "eagle-import") (part "JUMPER-PAD-3-NOYES_SILK"))
    )
    (comp (ref "SJ22")
      (value "JUMPER-PAD-3-NOYES_SILK")
      (footprint "eagle-import:PAD-JUMPER-3-NO_YES_SILK")
      (libsource (lib "eagle-import") (part "JUMPER-PAD-3-NOYES_SILK"))
    )
    (comp (ref "SJ23")
      (value "JUMPER-PAD-3-NOYES_SILK")
      (footprint "eagle-import:PAD-JUMPER-3-NO_YES_SILK")
      (libsource (lib "eagle-import") (part "JUMPER-PAD-3-NOYES_SILK"))
    )
    (comp (ref "SJ24")
      (value "JUMPER-PAD-3-NOYES_SILK")
      (footprint "eagle-import:PAD-JUMPER-3-NO_YES_SILK")
      (libsource (lib "eagle-import") (part "JUMPER-PAD-3-NOYES_SILK"))
    )
    (comp (ref "SJ25")
      (value "JUMPER-PAD-3-NO3_0")
      (footprint "eagle-import:PAD-JUMPER-3-NO_YES_SILK_ALL")
      (libsource (lib "eagle-import") (part "JUMPER-PAD-3-NO3_0"))
    )
    (comp (ref "SJ26")
      (value "JUMPER-PAD-3-NO3_0")
      (footprint "eagle-import:PAD-JUMPER-3-NO_YES_SILK_ALL")
      (libsource (lib "eagle-import") (part "JUMPER-PAD-3-NO3_0"))
    )
    (comp (ref "SJ27")
      (value "JUMPER-PAD-3-NO3_0")
      (footprint "eagle-import:PAD-JUMPER-3-NO_YES_SILK_ALL")
      (libsource (lib "eagle-import") (part "JUMPER-PAD-3-NO3_0"))
    )
    (comp (ref "SJ28")
      (value "JUMPER-PAD-3-NO3_0")
      (footprint "eagle-import:PAD-JUMPER-3-NO_YES_SILK_ALL")
      (libsource (lib "eagle-import") (part "JUMPER-PAD-3-NO3_0"))
    )
    (comp (ref "SJ29")
      (value "JUMPER-PAD-2-NO20")
      (footprint "eagle-import:PAD-JUMPER-2-NO_NO_SILK_20")
      (libsource (lib "eagle-import") (part "JUMPER-PAD-2-NO20"))
    )
    (comp (ref "SJ30")
      (value "JUMPER-PAD-2-NO20")
      (footprint "eagle-import:PAD-JUMPER-2-NO_NO_SILK_20")
      (libsource (lib "eagle-import") (part "JUMPER-PAD-2-NO20"))
    )
    (comp (ref "SJ31")
      (value "JUMPER-PAD-3-NO2_20")
      (footprint "eagle-import:PAD-JUMPER-3-NO_YES_SILK_20")
      (libsource (lib "eagle-import") (part "JUMPER-PAD-3-NO2_20"))
    )
    (comp (ref "SJ32")
      (value "JUMPER-PAD-3-NO2_20")
      (footprint "eagle-import:PAD-JUMPER-3-NO_YES_SILK_20")
      (libsource (lib "eagle-import") (part "JUMPER-PAD-3-NO2_20"))
    )
    (comp (ref "SJ33")
      (value "JUMPER-PAD-2-NO")
      (footprint "eagle-import:PAD-JUMPER-2-NO_NO_SILK")
      (libsource (lib "eagle-import") (part "JUMPER-PAD-2-NO"))
    )
    (comp (ref "SJ34")
      (value "JUMPER-PAD-2-NO")
      (footprint "eagle-import:PAD-JUMPER-2-NO_NO_SILK")
      (libsource (lib "eagle-import") (part "JUMPER-PAD-2-NO"))
    )
    (comp (ref "SJ35")
      (value "JUMPER-PAD-3-NOYES_SILK")
      (footprint "eagle-import:PAD-JUMPER-3-NO_YES_SILK")
      (libsource (lib "eagle-import") (part "JUMPER-PAD-3-NOYES_SILK"))
    )
    (comp (ref "SJ36")
      (value "JUMPER-PAD-3-NOYES_SILK")
      (footprint "eagle-import:PAD-JUMPER-3-NO_YES_SILK")
      (libsource (lib "eagle-import") (part "JUMPER-PAD-3-NOYES_SILK"))
    )
    (comp (ref "SJ37")
      (value "JUMPER-PAD-2-NO")
      (footprint "eagle-import:PAD-JUMPER-2-NO_NO_SILK")
      (libsource (lib "eagle-import") (part "JUMPER-PAD-2-NO"))
    )
    (comp (ref "SJ38")
      (value "JUMPER-PAD-2-NO")
      (footprint "eagle-import:PAD-JUMPER-2-NO_NO_SILK")
      (libsource (lib "eagle-import") (part "JUMPER-PAD-2-NO"))
    )
    (comp (ref "SJ39")
      (value "JUMPER-PAD-3-NOYES_SILK")
      (footprint "eagle-import:PAD-JUMPER-3-NO_YES_SILK")
      (libsource (lib "eagle-import") (part "JUMPER-PAD-3-NOYES_SILK"))
    )
    (comp (ref "SJ40")
      (value "JUMPER-PAD-3-NOYES_SILK")
      (footprint "eagle-import:PAD-JUMPER-3-NO_YES_SILK")
      (libsource (lib "eagle-import") (part "JUMPER-PAD-3-NOYES_SILK"))
    )
    (comp (ref "SJ41")
      (value "JUMPER-PAD-2-NO")
      (footprint "eagle-import:PAD-JUMPER-2-NO_NO_SILK")
      (libsource (lib "eagle-import") (part "JUMPER-PAD-2-NO"))
    )
    (comp (ref "SJ42")
      (value "JUMPER-PAD-2-NO")
      (footprint "eagle-import:PAD-JUMPER-2-NO_NO_SILK")
      (libsource (lib "eagle-import") (part "JUMPER-PAD-2-NO"))
    )
    (comp (ref "SJ43")
      (value "JUMPER-PAD-3-NOYES_SILK")
      (footprint "eagle-import:PAD-JUMPER-3-NO_YES_SILK")
      (libsource (lib "eagle-import") (part "JUMPER-PAD-3-NOYES_SILK"))
    )
    (comp (ref "SJ44")
      (value "JUMPER-PAD-3-NOYES_SILK")
      (footprint "eagle-import:PAD-JUMPER-3-NO_YES_SILK")
      (libsource (lib "eagle-import") (part "JUMPER-PAD-3-NOYES_SILK"))
    )
    (comp (ref "SJ45")
      (value "JUMPER-PAD-2-NO20")
      (footprint "eagle-import:PAD-JUMPER-2-NO_NO_SILK_20")
      (libsource (lib "eagle-import") (part "JUMPER-PAD-2-NO20"))
    )
    (comp (ref "SJ46")
      (value "JUMPER-PAD-2-NO20")
      (footprint "eagle-import:PAD-JUMPER-2-NO_NO_SILK_20")
      (libsource (lib "eagle-import") (part "JUMPER-PAD-2-NO20"))
    )
    (comp (ref "SJ47")
      (value "JUMPER-PAD-3-NO2_20")
      (footprint "eagle-import:PAD-JUMPER-3-NO_YES_SILK_20")
      (libsource (lib "eagle-import") (part "JUMPER-PAD-3-NO2_20"))
    )
    (comp (ref "SJ48")
      (value "JUMPER-PAD-3-NO2_20")
      (footprint "eagle-import:PAD-JUMPER-3-NO_YES_SILK_20")
      (libsource (lib "eagle-import") (part "JUMPER-PAD-3-NO2_20"))
    )
    (comp (ref "SJ49")
      (value "JUMPER-PAD-2-NO20")
      (footprint "eagle-import:PAD-JUMPER-2-NO_NO_SILK_20")
      (libsource (lib "eagle-import") (part "JUMPER-PAD-2-NO20"))
    )
    (comp (ref "SJ50")
      (value "JUMPER-PAD-2-NO20")
      (footprint "eagle-import:PAD-JUMPER-2-NO_NO_SILK_20")
      (libsource (lib "eagle-import") (part "JUMPER-PAD-2-NO20"))
    )
    (comp (ref "SJ51")
      (value "JUMPER-PAD-3-NO2_20")
      (footprint "eagle-import:PAD-JUMPER-3-NO_YES_SILK_20")
      (libsource (lib "eagle-import") (part "JUMPER-PAD-3-NO2_20"))
    )
    (comp (ref "SJ52")
      (value "JUMPER-PAD-3-NO2_20")
      (footprint "eagle-import:PAD-JUMPER-3-NO_YES_SILK_20")
      (libsource (lib "eagle-import") (part "JUMPER-PAD-3-NO2_20"))
    )
    (comp (ref "SJ53")
      (value "JUMPER-PAD-2-NO20")
      (footprint "eagle-import:PAD-JUMPER-2-NO_NO_SILK_20")
      (libsource (lib "eagle-import") (part "JUMPER-PAD-2-NO20"))
    )
    (comp (ref "SJ54")
      (value "JUMPER-PAD-2-NO20")
      (footprint "eagle-import:PAD-JUMPER-2-NO_NO_SILK_20")
      (libsource (lib "eagle-import") (part "JUMPER-PAD-2-NO20"))
    )
    (comp (ref "SJ55")
      (value "JUMPER-PAD-3-NO2_20")
      (footprint "eagle-import:PAD-JUMPER-3-NO_YES_SILK_20")
      (libsource (lib "eagle-import") (part "JUMPER-PAD-3-NO2_20"))
    )
    (comp (ref "SJ56")
      (value "JUMPER-PAD-3-NO2_20")
      (footprint "eagle-import:PAD-JUMPER-3-NO_YES_SILK_20")
      (libsource (lib "eagle-import") (part "JUMPER-PAD-3-NO2_20"))
    )
    (comp (ref "SJ57")
      (value "JUMPER-PAD-2-NO20")
      (footprint "eagle-import:PAD-JUMPER-2-NO_NO_SILK_20")
      (libsource (lib "eagle-import") (part "JUMPER-PAD-2-NO20"))
    )
    (comp (ref "SJ58")
      (value "JUMPER-PAD-2-NO20")
      (footprint "eagle-import:PAD-JUMPER-2-NO_NO_SILK_20")
      (libsource (lib "eagle-import") (part "JUMPER-PAD-2-NO20"))
    )
    (comp (ref "SJ59")
      (value "JUMPER-PAD-3-NO2_20")
      (footprint "eagle-import:PAD-JUMPER-3-NO_YES_SILK_20")
      (libsource (lib "eagle-import") (part "JUMPER-PAD-3-NO2_20"))
    )
    (comp (ref "SJ60")
      (value "JUMPER-PAD-3-NO2_20")
      (footprint "eagle-import:PAD-JUMPER-3-NO_YES_SILK_20")
      (libsource (lib "eagle-import") (part "JUMPER-PAD-3-NO2_20"))
    )
    (comp (ref "SJ61")
      (value "JUMPER-PAD-2-NO20")
      (footprint "eagle-import:PAD-JUMPER-2-NO_NO_SILK_20")
      (libsource (lib "eagle-import") (part "JUMPER-PAD-2-NO20"))
    )
    (comp (ref "SJ62")
      (value "JUMPER-PAD-2-NO20")
      (footprint "eagle-import:PAD-JUMPER-2-NO_NO_SILK_20")
      (libsource (lib "eagle-import") (part "JUMPER-PAD-2-NO20"))
    )
    (comp (ref "SJ63")
      (value "JUMPER-PAD-3-NO2_20")
      (footprint "eagle-import:PAD-JUMPER-3-NO_YES_SILK_20")
      (libsource (lib "eagle-import") (part "JUMPER-PAD-3-NO2_20"))
    )
    (comp (ref "SJ64")
      (value "JUMPER-PAD-3-NO2_20")
      (footprint "eagle-import:PAD-JUMPER-3-NO_YES_SILK_20")
      (libsource (lib "eagle-import") (part "JUMPER-PAD-3-NO2_20"))
    )
    (comp (ref "SJ65")
      (value "JUMPER-PAD-2-NO20")
      (footprint "eagle-import:PAD-JUMPER-2-NO_NO_SILK_20")
      (libsource (lib "eagle-import") (part "JUMPER-PAD-2-NO20"))
    )
    (comp (ref "SJ66")
      (value "JUMPER-PAD-2-NO20")
      (footprint "eagle-import:PAD-JUMPER-2-NO_NO_SILK_20")
      (libsource (lib "eagle-import") (part "JUMPER-PAD-2-NO20"))
    )
    (comp (ref "SJ67")
      (value "JUMPER-PAD-3-NO2_20")
      (footprint "eagle-import:PAD-JUMPER-3-NO_YES_SILK_20")
      (libsource (lib "eagle-import") (part "JUMPER-PAD-3-NO2_20"))
    )
    (comp (ref "SJ68")
      (value "JUMPER-PAD-3-NO2_20")
      (footprint "eagle-import:PAD-JUMPER-3-NO_YES_SILK_20")
      (libsource (lib "eagle-import") (part "JUMPER-PAD-3-NO2_20"))
    )
    (comp (ref "SJ69")
      (value "JUMPER-PAD-2-NO")
      (footprint "eagle-import:PAD-JUMPER-2-NO_NO_SILK")
      (libsource (lib "eagle-import") (part "JUMPER-PAD-2-NO"))
    )
    (comp (ref "SJ70")
      (value "JUMPER-PAD-2-NO")
      (footprint "eagle-import:PAD-JUMPER-2-NO_NO_SILK")
      (libsource (lib "eagle-import") (part "JUMPER-PAD-2-NO"))
    )
    (comp (ref "SJ71")
      (value "JUMPER-PAD-3-NO2_20")
      (footprint "eagle-import:PAD-JUMPER-3-NO_YES_SILK_20")
      (libsource (lib "eagle-import") (part "JUMPER-PAD-3-NO2_20"))
    )
    (comp (ref "SJ72")
      (value "JUMPER-PAD-3-NO2_20")
      (footprint "eagle-import:PAD-JUMPER-3-NO_YES_SILK_20")
      (libsource (lib "eagle-import") (part "JUMPER-PAD-3-NO2_20"))
    )
    (comp (ref "SJ73")
      (value "JUMPER-PAD-3-NOYES_SILK")
      (footprint "eagle-import:PAD-JUMPER-3-NO_YES_SILK")
      (libsource (lib "eagle-import") (part "JUMPER-PAD-3-NOYES_SILK"))
    )
    (comp (ref "SJ74")
      (value "JUMPER-PAD-3-NOYES_SILK")
      (footprint "eagle-import:PAD-JUMPER-3-NO_YES_SILK")
      (libsource (lib "eagle-import") (part "JUMPER-PAD-3-NOYES_SILK"))
    )
    (comp (ref "SJ75")
      (value "JUMPER-PAD-3-NOYES_SILK")
      (footprint "eagle-import:PAD-JUMPER-3-NO_YES_SILK")
      (libsource (lib "eagle-import") (part "JUMPER-PAD-3-NOYES_SILK"))
    )
    (comp (ref "SJ76")
      (value "JUMPER-PAD-3-NOYES_SILK")
      (footprint "eagle-import:PAD-JUMPER-3-NO_YES_SILK")
      (libsource (lib "eagle-import") (part "JUMPER-PAD-3-NOYES_SILK"))
    )
    (comp (ref "SJ77")
      (value "JUMPER-PAD-3-NO3_20")
      (footprint "eagle-import:PAD-JUMPER-3-NO_YES_SILK_ALL_20")
      (libsource (lib "eagle-import") (part "JUMPER-PAD-3-NO3_20"))
    )
    (comp (ref "SJ78")
      (value "JUMPER-PAD-3-NO3_20")
      (footprint "eagle-import:PAD-JUMPER-3-NO_YES_SILK_ALL_20")
      (libsource (lib "eagle-import") (part "JUMPER-PAD-3-NO3_20"))
    )
    (comp (ref "SJ79")
      (value "JUMPER-PAD-3-NO3_20")
      (footprint "eagle-import:PAD-JUMPER-3-NO_YES_SILK_ALL_20")
      (libsource (lib "eagle-import") (part "JUMPER-PAD-3-NO3_20"))
    )
    (comp (ref "SJ80")
      (value "JUMPER-PAD-3-NO3_20")
      (footprint "eagle-import:PAD-JUMPER-3-NO_YES_SILK_ALL_20")
      (libsource (lib "eagle-import") (part "JUMPER-PAD-3-NO3_20"))
    )
    (comp (ref "SJ81")
      (value "JUMPER-PAD-2-NO40")
      (footprint "eagle-import:PAD-JUMPER-2-NO_NO_SILK_40")
      (libsource (lib "eagle-import") (part "JUMPER-PAD-2-NO40"))
    )
    (comp (ref "SJ82")
      (value "JUMPER-PAD-2-NO40")
      (footprint "eagle-import:PAD-JUMPER-2-NO_NO_SILK_40")
      (libsource (lib "eagle-import") (part "JUMPER-PAD-2-NO40"))
    )
    (comp (ref "SJ83")
      (value "JUMPER-PAD-3-NO2_40")
      (footprint "eagle-import:PAD-JUMPER-3-NO_YES_SILK_40")
      (libsource (lib "eagle-import") (part "JUMPER-PAD-3-NO2_40"))
    )
    (comp (ref "SJ84")
      (value "JUMPER-PAD-3-NO2_40")
      (footprint "eagle-import:PAD-JUMPER-3-NO_YES_SILK_40")
      (libsource (lib "eagle-import") (part "JUMPER-PAD-3-NO2_40"))
    )
    (comp (ref "SJ85")
      (value "JUMPER-PAD-2-NO40")
      (footprint "eagle-import:PAD-JUMPER-2-NO_NO_SILK_40")
      (libsource (lib "eagle-import") (part "JUMPER-PAD-2-NO40"))
    )
    (comp (ref "SJ86")
      (value "JUMPER-PAD-2-NO40")
      (footprint "eagle-import:PAD-JUMPER-2-NO_NO_SILK_40")
      (libsource (lib "eagle-import") (part "JUMPER-PAD-2-NO40"))
    )
    (comp (ref "SJ87")
      (value "JUMPER-PAD-3-NO2_40")
      (footprint "eagle-import:PAD-JUMPER-3-NO_YES_SILK_40")
      (libsource (lib "eagle-import") (part "JUMPER-PAD-3-NO2_40"))
    )
    (comp (ref "SJ88")
      (value "JUMPER-PAD-3-NO2_40")
      (footprint "eagle-import:PAD-JUMPER-3-NO_YES_SILK_40")
      (libsource (lib "eagle-import") (part "JUMPER-PAD-3-NO2_40"))
    )
    (comp (ref "SJ89")
      (value "JUMPER-PAD-2-NO40")
      (footprint "eagle-import:PAD-JUMPER-2-NO_NO_SILK_40")
      (libsource (lib "eagle-import") (part "JUMPER-PAD-2-NO40"))
    )
    (comp (ref "SJ90")
      (value "JUMPER-PAD-2-NO40")
      (footprint "eagle-import:PAD-JUMPER-2-NO_NO_SILK_40")
      (libsource (lib "eagle-import") (part "JUMPER-PAD-2-NO40"))
    )
    (comp (ref "SJ91")
      (value "JUMPER-PAD-3-NO2_40")
      (footprint "eagle-import:PAD-JUMPER-3-NO_YES_SILK_40")
      (libsource (lib "eagle-import") (part "JUMPER-PAD-3-NO2_40"))
    )
    (comp (ref "SJ92")
      (value "JUMPER-PAD-3-NO2_40")
      (footprint "eagle-import:PAD-JUMPER-3-NO_YES_SILK_40")
      (libsource (lib "eagle-import") (part "JUMPER-PAD-3-NO2_40"))
    )
    (comp (ref "SJ93")
      (value "JUMPER-PAD-2-NO40")
      (footprint "eagle-import:PAD-JUMPER-2-NO_NO_SILK_40")
      (libsource (lib "eagle-import") (part "JUMPER-PAD-2-NO40"))
    )
    (comp (ref "SJ94")
      (value "JUMPER-PAD-2-NO40")
      (footprint "eagle-import:PAD-JUMPER-2-NO_NO_SILK_40")
      (libsource (lib "eagle-import") (part "JUMPER-PAD-2-NO40"))
    )
    (comp (ref "SJ95")
      (value "JUMPER-PAD-3-NO2_40")
      (footprint "eagle-import:PAD-JUMPER-3-NO_YES_SILK_40")
      (libsource (lib "eagle-import") (part "JUMPER-PAD-3-NO2_40"))
    )
    (comp (ref "SJ96")
      (value "JUMPER-PAD-3-NO2_40")
      (footprint "eagle-import:PAD-JUMPER-3-NO_YES_SILK_40")
      (libsource (lib "eagle-import") (part "JUMPER-PAD-3-NO2_40"))
    )
    (comp (ref "SJ97")
      (value "JUMPER-PAD-2-NO40")
      (footprint "eagle-import:PAD-JUMPER-2-NO_NO_SILK_40")
      (libsource (lib "eagle-import") (part "JUMPER-PAD-2-NO40"))
    )
    (comp (ref "SJ98")
      (value "JUMPER-PAD-2-NO40")
      (footprint "eagle-import:PAD-JUMPER-2-NO_NO_SILK_40")
      (libsource (lib "eagle-import") (part "JUMPER-PAD-2-NO40"))
    )
    (comp (ref "SJ99")
      (value "JUMPER-PAD-3-NO2_40")
      (footprint "eagle-import:PAD-JUMPER-3-NO_YES_SILK_40")
      (libsource (lib "eagle-import") (part "JUMPER-PAD-3-NO2_40"))
    )
    (comp (ref "SJ100")
      (value "JUMPER-PAD-3-NO2_40")
      (footprint "eagle-import:PAD-JUMPER-3-NO_YES_SILK_40")
      (libsource (lib "eagle-import") (part "JUMPER-PAD-3-NO2_40"))
    )
    (comp (ref "SJ101")
      (value "JUMPER-PAD-2-NO40")
      (footprint "eagle-import:PAD-JUMPER-2-NO_NO_SILK_40")
      (libsource (lib "eagle-import") (part "JUMPER-PAD-2-NO40"))
    )
    (comp (ref "SJ102")
      (value "JUMPER-PAD-2-NO40")
      (footprint "eagle-import:PAD-JUMPER-2-NO_NO_SILK_40")
      (libsource (lib "eagle-import") (part "JUMPER-PAD-2-NO40"))
    )
    (comp (ref "SJ103")
      (value "JUMPER-PAD-3-NO2_40")
      (footprint "eagle-import:PAD-JUMPER-3-NO_YES_SILK_40")
      (libsource (lib "eagle-import") (part "JUMPER-PAD-3-NO2_40"))
    )
    (comp (ref "SJ104")
      (value "JUMPER-PAD-3-NO2_40")
      (footprint "eagle-import:PAD-JUMPER-3-NO_YES_SILK_40")
      (libsource (lib "eagle-import") (part "JUMPER-PAD-3-NO2_40"))
    )
    (comp (ref "SJ105")
      (value "JUMPER-PAD-2-NO40")
      (footprint "eagle-import:PAD-JUMPER-2-NO_NO_SILK_40")
      (libsource (lib "eagle-import") (part "JUMPER-PAD-2-NO40"))
    )
    (comp (ref "SJ106")
      (value "JUMPER-PAD-2-NO40")
      (footprint "eagle-import:PAD-JUMPER-2-NO_NO_SILK_40")
      (libsource (lib "eagle-import") (part "JUMPER-PAD-2-NO40"))
    )
    (comp (ref "SJ107")
      (value "JUMPER-PAD-3-NO2_40")
      (footprint "eagle-import:PAD-JUMPER-3-NO_YES_SILK_40")
      (libsource (lib "eagle-import") (part "JUMPER-PAD-3-NO2_40"))
    )
    (comp (ref "SJ108")
      (value "JUMPER-PAD-3-NO2_40")
      (footprint "eagle-import:PAD-JUMPER-3-NO_YES_SILK_40")
      (libsource (lib "eagle-import") (part "JUMPER-PAD-3-NO2_40"))
    )
    (comp (ref "SJ109")
      (value "JUMPER-PAD-2-NO40")
      (footprint "eagle-import:PAD-JUMPER-2-NO_NO_SILK_40")
      (libsource (lib "eagle-import") (part "JUMPER-PAD-2-NO40"))
    )
    (comp (ref "SJ110")
      (value "JUMPER-PAD-2-NO40")
      (footprint "eagle-import:PAD-JUMPER-2-NO_NO_SILK_40")
      (libsource (lib "eagle-import") (part "JUMPER-PAD-2-NO40"))
    )
    (comp (ref "SJ111")
      (value "JUMPER-PAD-3-NO2_40")
      (footprint "eagle-import:PAD-JUMPER-3-NO_YES_SILK_40")
      (libsource (lib "eagle-import") (part "JUMPER-PAD-3-NO2_40"))
    )
    (comp (ref "SJ112")
      (value "JUMPER-PAD-3-NO2_40")
      (footprint "eagle-import:PAD-JUMPER-3-NO_YES_SILK_40")
      (libsource (lib "eagle-import") (part "JUMPER-PAD-3-NO2_40"))
    )
    (comp (ref "SJ113")
      (value "JUMPER-PAD-3-NO3_40")
      (footprint "eagle-import:PAD-JUMPER-3-NO_YES_SILK_ALL_40")
      (libsource (lib "eagle-import") (part "JUMPER-PAD-3-NO3_40"))
    )
    (comp (ref "SJ114")
      (value "JUMPER-PAD-3-NO3_40")
      (footprint "eagle-import:PAD-JUMPER-3-NO_YES_SILK_ALL_40")
      (libsource (lib "eagle-import") (part "JUMPER-PAD-3-NO3_40"))
    )
    (comp (ref "SJ115")
      (value "JUMPER-PAD-3-NO3_40")
      (footprint "eagle-import:PAD-JUMPER-3-NO_YES_SILK_ALL_40")
      (libsource (lib "eagle-import") (part "JUMPER-PAD-3-NO3_40"))
    )
    (comp (ref "SJ116")
      (value "JUMPER-PAD-3-NO3_40")
      (footprint "eagle-import:PAD-JUMPER-3-NO_YES_SILK_ALL_40")
      (libsource (lib "eagle-import") (part "JUMPER-PAD-3-NO3_40"))
    )
    (comp (ref "SJ117")
      (value "JUMPER-PAD-3-NO3_40")
      (footprint "eagle-import:PAD-JUMPER-3-NO_YES_SILK_ALL_40")
      (libsource (lib "eagle-import") (part "JUMPER-PAD-3-NO3_40"))
    )
    (comp (ref "SJ118")
      (value "JUMPER-PAD-3-NO3_40")
      (footprint "eagle-import:PAD-JUMPER-3-NO_YES_SILK_ALL_40")
      (libsource (lib "eagle-import") (part "JUMPER-PAD-3-NO3_40"))
    )
    (comp (ref "SJ119")
      (value "JUMPER-PAD-3-NO3_40")
      (footprint "eagle-import:PAD-JUMPER-3-NO_YES_SILK_ALL_40")
      (libsource (lib "eagle-import") (part "JUMPER-PAD-3-NO3_40"))
    )
    (comp (ref "SJ120")
      (value "JUMPER-PAD-3-NO3_40")
      (footprint "eagle-import:PAD-JUMPER-3-NO_YES_SILK_ALL_40")
      (libsource (lib "eagle-import") (part "JUMPER-PAD-3-NO3_40"))
    )
    (comp (ref "SJ121")
      (value "JUMPER-PAD-2-NO60")
      (footprint "eagle-import:PAD-JUMPER-2-NO_NO_SILK_60")
      (libsource (lib "eagle-import") (part "JUMPER-PAD-2-NO60"))
    )
    (comp (ref "SJ122")
      (value "JUMPER-PAD-2-NO60")
      (footprint "eagle-import:PAD-JUMPER-2-NO_NO_SILK_60")
      (libsource (lib "eagle-import") (part "JUMPER-PAD-2-NO60"))
    )
    (comp (ref "SJ123")
      (value "JUMPER-PAD-3-NO2_60")
      (footprint "eagle-import:PAD-JUMPER-3-NO_YES_SILK_60")
      (libsource (lib "eagle-import") (part "JUMPER-PAD-3-NO2_60"))
    )
    (comp (ref "SJ124")
      (value "JUMPER-PAD-3-NO2_60")
      (footprint "eagle-import:PAD-JUMPER-3-NO_YES_SILK_60")
      (libsource (lib "eagle-import") (part "JUMPER-PAD-3-NO2_60"))
    )
    (comp (ref "SJ125")
      (value "JUMPER-PAD-2-NO60")
      (footprint "eagle-import:PAD-JUMPER-2-NO_NO_SILK_60")
      (libsource (lib "eagle-import") (part "JUMPER-PAD-2-NO60"))
    )
    (comp (ref "SJ126")
      (value "JUMPER-PAD-2-NO60")
      (footprint "eagle-import:PAD-JUMPER-2-NO_NO_SILK_60")
      (libsource (lib "eagle-import") (part "JUMPER-PAD-2-NO60"))
    )
    (comp (ref "SJ127")
      (value "JUMPER-PAD-3-NO2_60")
      (footprint "eagle-import:PAD-JUMPER-3-NO_YES_SILK_60")
      (libsource (lib "eagle-import") (part "JUMPER-PAD-3-NO2_60"))
    )
    (comp (ref "SJ128")
      (value "JUMPER-PAD-3-NO2_60")
      (footprint "eagle-import:PAD-JUMPER-3-NO_YES_SILK_60")
      (libsource (lib "eagle-import") (part "JUMPER-PAD-3-NO2_60"))
    )
    (comp (ref "SJ129")
      (value "JUMPER-PAD-2-NO60")
      (footprint "eagle-import:PAD-JUMPER-2-NO_NO_SILK_60")
      (libsource (lib "eagle-import") (part "JUMPER-PAD-2-NO60"))
    )
    (comp (ref "SJ130")
      (value "JUMPER-PAD-2-NO60")
      (footprint "eagle-import:PAD-JUMPER-2-NO_NO_SILK_60")
      (libsource (lib "eagle-import") (part "JUMPER-PAD-2-NO60"))
    )
    (comp (ref "SJ131")
      (value "JUMPER-PAD-3-NO2_60")
      (footprint "eagle-import:PAD-JUMPER-3-NO_YES_SILK_60")
      (libsource (lib "eagle-import") (part "JUMPER-PAD-3-NO2_60"))
    )
    (comp (ref "SJ132")
      (value "JUMPER-PAD-3-NO2_60")
      (footprint "eagle-import:PAD-JUMPER-3-NO_YES_SILK_60")
      (libsource (lib "eagle-import") (part "JUMPER-PAD-3-NO2_60"))
    )
    (comp (ref "SJ133")
      (value "JUMPER-PAD-2-NO60")
      (footprint "eagle-import:PAD-JUMPER-2-NO_NO_SILK_60")
      (libsource (lib "eagle-import") (part "JUMPER-PAD-2-NO60"))
    )
    (comp (ref "SJ134")
      (value "JUMPER-PAD-2-NO60")
      (footprint "eagle-import:PAD-JUMPER-2-NO_NO_SILK_60")
      (libsource (lib "eagle-import") (part "JUMPER-PAD-2-NO60"))
    )
    (comp (ref "SJ135")
      (value "JUMPER-PAD-3-NO2_60")
      (footprint "eagle-import:PAD-JUMPER-3-NO_YES_SILK_60")
      (libsource (lib "eagle-import") (part "JUMPER-PAD-3-NO2_60"))
    )
    (comp (ref "SJ136")
      (value "JUMPER-PAD-3-NO2_60")
      (footprint "eagle-import:PAD-JUMPER-3-NO_YES_SILK_60")
      (libsource (lib "eagle-import") (part "JUMPER-PAD-3-NO2_60"))
    )
    (comp (ref "SJ137")
      (value "JUMPER-PAD-2-NO60")
      (footprint "eagle-import:PAD-JUMPER-2-NO_NO_SILK_60")
      (libsource (lib "eagle-import") (part "JUMPER-PAD-2-NO60"))
    )
    (comp (ref "SJ138")
      (value "JUMPER-PAD-2-NO60")
      (footprint "eagle-import:PAD-JUMPER-2-NO_NO_SILK_60")
      (libsource (lib "eagle-import") (part "JUMPER-PAD-2-NO60"))
    )
    (comp (ref "SJ139")
      (value "JUMPER-PAD-3-NO2_60")
      (footprint "eagle-import:PAD-JUMPER-3-NO_YES_SILK_60")
      (libsource (lib "eagle-import") (part "JUMPER-PAD-3-NO2_60"))
    )
    (comp (ref "SJ140")
      (value "JUMPER-PAD-3-NO2_60")
      (footprint "eagle-import:PAD-JUMPER-3-NO_YES_SILK_60")
      (libsource (lib "eagle-import") (part "JUMPER-PAD-3-NO2_60"))
    )
    (comp (ref "SJ141")
      (value "JUMPER-PAD-2-NO60")
      (footprint "eagle-import:PAD-JUMPER-2-NO_NO_SILK_60")
      (libsource (lib "eagle-import") (part "JUMPER-PAD-2-NO60"))
    )
    (comp (ref "SJ142")
      (value "JUMPER-PAD-2-NO60")
      (footprint "eagle-import:PAD-JUMPER-2-NO_NO_SILK_60")
      (libsource (lib "eagle-import") (part "JUMPER-PAD-2-NO60"))
    )
    (comp (ref "SJ143")
      (value "JUMPER-PAD-3-NO2_60")
      (footprint "eagle-import:PAD-JUMPER-3-NO_YES_SILK_60")
      (libsource (lib "eagle-import") (part "JUMPER-PAD-3-NO2_60"))
    )
    (comp (ref "SJ144")
      (value "JUMPER-PAD-3-NO2_60")
      (footprint "eagle-import:PAD-JUMPER-3-NO_YES_SILK_60")
      (libsource (lib "eagle-import") (part "JUMPER-PAD-3-NO2_60"))
    )
    (comp (ref "SJ145")
      (value "JUMPER-PAD-2-NO60")
      (footprint "eagle-import:PAD-JUMPER-2-NO_NO_SILK_60")
      (libsource (lib "eagle-import") (part "JUMPER-PAD-2-NO60"))
    )
    (comp (ref "SJ146")
      (value "JUMPER-PAD-2-NO60")
      (footprint "eagle-import:PAD-JUMPER-2-NO_NO_SILK_60")
      (libsource (lib "eagle-import") (part "JUMPER-PAD-2-NO60"))
    )
    (comp (ref "SJ147")
      (value "JUMPER-PAD-3-NO2_60")
      (footprint "eagle-import:PAD-JUMPER-3-NO_YES_SILK_60")
      (libsource (lib "eagle-import") (part "JUMPER-PAD-3-NO2_60"))
    )
    (comp (ref "SJ148")
      (value "JUMPER-PAD-3-NO2_60")
      (footprint "eagle-import:PAD-JUMPER-3-NO_YES_SILK_60")
      (libsource (lib "eagle-import") (part "JUMPER-PAD-3-NO2_60"))
    )
    (comp (ref "SJ149")
      (value "JUMPER-PAD-2-NO60")
      (footprint "eagle-import:PAD-JUMPER-2-NO_NO_SILK_60")
      (libsource (lib "eagle-import") (part "JUMPER-PAD-2-NO60"))
    )
    (comp (ref "SJ150")
      (value "JUMPER-PAD-2-NO60")
      (footprint "eagle-import:PAD-JUMPER-2-NO_NO_SILK_60")
      (libsource (lib "eagle-import") (part "JUMPER-PAD-2-NO60"))
    )
    (comp (ref "SJ151")
      (value "JUMPER-PAD-3-NO2_60")
      (footprint "eagle-import:PAD-JUMPER-3-NO_YES_SILK_60")
      (libsource (lib "eagle-import") (part "JUMPER-PAD-3-NO2_60"))
    )
    (comp (ref "SJ152")
      (value "JUMPER-PAD-3-NO2_60")
      (footprint "eagle-import:PAD-JUMPER-3-NO_YES_SILK_60")
      (libsource (lib "eagle-import") (part "JUMPER-PAD-3-NO2_60"))
    )
    (comp (ref "SJ153")
      (value "JUMPER-PAD-3-NO3_60")
      (footprint "eagle-import:PAD-JUMPER-3-NO_YES_SILK_ALL_60")
      (libsource (lib "eagle-import") (part "JUMPER-PAD-3-NO3_60"))
    )
    (comp (ref "SJ154")
      (value "JUMPER-PAD-3-NO3_60")
      (footprint "eagle-import:PAD-JUMPER-3-NO_YES_SILK_ALL_60")
      (libsource (lib "eagle-import") (part "JUMPER-PAD-3-NO3_60"))
    )
    (comp (ref "SJ155")
      (value "JUMPER-PAD-3-NO3_60")
      (footprint "eagle-import:PAD-JUMPER-3-NO_YES_SILK_ALL_60")
      (libsource (lib "eagle-import") (part "JUMPER-PAD-3-NO3_60"))
    )
    (comp (ref "SJ156")
      (value "JUMPER-PAD-3-NO3_60")
      (footprint "eagle-import:PAD-JUMPER-3-NO_YES_SILK_ALL_60")
      (libsource (lib "eagle-import") (part "JUMPER-PAD-3-NO3_60"))
    )
    (comp (ref "SJ157")
      (value "JUMPER-PAD-3-NO3_60")
      (footprint "eagle-import:PAD-JUMPER-3-NO_YES_SILK_ALL_60")
      (libsource (lib "eagle-import") (part "JUMPER-PAD-3-NO3_60"))
    )
    (comp (ref "SJ158")
      (value "JUMPER-PAD-3-NO3_60")
      (footprint "eagle-import:PAD-JUMPER-3-NO_YES_SILK_ALL_60")
      (libsource (lib "eagle-import") (part "JUMPER-PAD-3-NO3_60"))
    )
    (comp (ref "SJ159")
      (value "JUMPER-PAD-3-NO3_60")
      (footprint "eagle-import:PAD-JUMPER-3-NO_YES_SILK_ALL_60")
      (libsource (lib "eagle-import") (part "JUMPER-PAD-3-NO3_60"))
    )
    (comp (ref "SJ160")
      (value "JUMPER-PAD-3-NO3_60")
      (footprint "eagle-import:PAD-JUMPER-3-NO_YES_SILK_ALL_60")
      (libsource (lib "eagle-import") (part "JUMPER-PAD-3-NO3_60"))
    )
    (comp (ref "SJ161")
      (value "JUMPER-PAD-2-NO80")
      (footprint "eagle-import:PAD-JUMPER-2-NO_NO_SILK_80")
      (libsource (lib "eagle-import") (part "JUMPER-PAD-2-NO80"))
    )
    (comp (ref "SJ162")
      (value "JUMPER-PAD-2-NO80")
      (footprint "eagle-import:PAD-JUMPER-2-NO_NO_SILK_80")
      (libsource (lib "eagle-import") (part "JUMPER-PAD-2-NO80"))
    )
    (comp (ref "SJ163")
      (value "JUMPER-PAD-3-NO2_80")
      (footprint "eagle-import:PAD-JUMPER-3-NO_YES_SILK_80")
      (libsource (lib "eagle-import") (part "JUMPER-PAD-3-NO2_80"))
    )
    (comp (ref "SJ164")
      (value "JUMPER-PAD-3-NO2_80")
      (footprint "eagle-import:PAD-JUMPER-3-NO_YES_SILK_80")
      (libsource (lib "eagle-import") (part "JUMPER-PAD-3-NO2_80"))
    )
    (comp (ref "SJ165")
      (value "JUMPER-PAD-2-NO80")
      (footprint "eagle-import:PAD-JUMPER-2-NO_NO_SILK_80")
      (libsource (lib "eagle-import") (part "JUMPER-PAD-2-NO80"))
    )
    (comp (ref "SJ166")
      (value "JUMPER-PAD-2-NO80")
      (footprint "eagle-import:PAD-JUMPER-2-NO_NO_SILK_80")
      (libsource (lib "eagle-import") (part "JUMPER-PAD-2-NO80"))
    )
    (comp (ref "SJ167")
      (value "JUMPER-PAD-3-NO2_80")
      (footprint "eagle-import:PAD-JUMPER-3-NO_YES_SILK_80")
      (libsource (lib "eagle-import") (part "JUMPER-PAD-3-NO2_80"))
    )
    (comp (ref "SJ168")
      (value "JUMPER-PAD-3-NO2_80")
      (footprint "eagle-import:PAD-JUMPER-3-NO_YES_SILK_80")
      (libsource (lib "eagle-import") (part "JUMPER-PAD-3-NO2_80"))
    )
    (comp (ref "SJ169")
      (value "JUMPER-PAD-2-NO80")
      (footprint "eagle-import:PAD-JUMPER-2-NO_NO_SILK_80")
      (libsource (lib "eagle-import") (part "JUMPER-PAD-2-NO80"))
    )
    (comp (ref "SJ170")
      (value "JUMPER-PAD-2-NO80")
      (footprint "eagle-import:PAD-JUMPER-2-NO_NO_SILK_80")
      (libsource (lib "eagle-import") (part "JUMPER-PAD-2-NO80"))
    )
    (comp (ref "SJ171")
      (value "JUMPER-PAD-3-NO2_80")
      (footprint "eagle-import:PAD-JUMPER-3-NO_YES_SILK_80")
      (libsource (lib "eagle-import") (part "JUMPER-PAD-3-NO2_80"))
    )
    (comp (ref "SJ172")
      (value "JUMPER-PAD-3-NO2_80")
      (footprint "eagle-import:PAD-JUMPER-3-NO_YES_SILK_80")
      (libsource (lib "eagle-import") (part "JUMPER-PAD-3-NO2_80"))
    )
    (comp (ref "SJ173")
      (value "JUMPER-PAD-2-NO80")
      (footprint "eagle-import:PAD-JUMPER-2-NO_NO_SILK_80")
      (libsource (lib "eagle-import") (part "JUMPER-PAD-2-NO80"))
    )
    (comp (ref "SJ174")
      (value "JUMPER-PAD-2-NO80")
      (footprint "eagle-import:PAD-JUMPER-2-NO_NO_SILK_80")
      (libsource (lib "eagle-import") (part "JUMPER-PAD-2-NO80"))
    )
    (comp (ref "SJ175")
      (value "JUMPER-PAD-3-NO2_80")
      (footprint "eagle-import:PAD-JUMPER-3-NO_YES_SILK_80")
      (libsource (lib "eagle-import") (part "JUMPER-PAD-3-NO2_80"))
    )
    (comp (ref "SJ176")
      (value "JUMPER-PAD-3-NO2_80")
      (footprint "eagle-import:PAD-JUMPER-3-NO_YES_SILK_80")
      (libsource (lib "eagle-import") (part "JUMPER-PAD-3-NO2_80"))
    )
    (comp (ref "SJ177")
      (value "JUMPER-PAD-2-NO80")
      (footprint "eagle-import:PAD-JUMPER-2-NO_NO_SILK_80")
      (libsource (lib "eagle-import") (part "JUMPER-PAD-2-NO80"))
    )
    (comp (ref "SJ178")
      (value "JUMPER-PAD-2-NO80")
      (footprint "eagle-import:PAD-JUMPER-2-NO_NO_SILK_80")
      (libsource (lib "eagle-import") (part "JUMPER-PAD-2-NO80"))
    )
    (comp (ref "SJ179")
      (value "JUMPER-PAD-3-NO2_80")
      (footprint "eagle-import:PAD-JUMPER-3-NO_YES_SILK_80")
      (libsource (lib "eagle-import") (part "JUMPER-PAD-3-NO2_80"))
    )
    (comp (ref "SJ180")
      (value "JUMPER-PAD-3-NO2_80")
      (footprint "eagle-import:PAD-JUMPER-3-NO_YES_SILK_80")
      (libsource (lib "eagle-import") (part "JUMPER-PAD-3-NO2_80"))
    )
    (comp (ref "SJ181")
      (value "JUMPER-PAD-2-NO80")
      (footprint "eagle-import:PAD-JUMPER-2-NO_NO_SILK_80")
      (libsource (lib "eagle-import") (part "JUMPER-PAD-2-NO80"))
    )
    (comp (ref "SJ182")
      (value "JUMPER-PAD-2-NO80")
      (footprint "eagle-import:PAD-JUMPER-2-NO_NO_SILK_80")
      (libsource (lib "eagle-import") (part "JUMPER-PAD-2-NO80"))
    )
    (comp (ref "SJ183")
      (value "JUMPER-PAD-3-NO2_80")
      (footprint "eagle-import:PAD-JUMPER-3-NO_YES_SILK_80")
      (libsource (lib "eagle-import") (part "JUMPER-PAD-3-NO2_80"))
    )
    (comp (ref "SJ184")
      (value "JUMPER-PAD-3-NO2_80")
      (footprint "eagle-import:PAD-JUMPER-3-NO_YES_SILK_80")
      (libsource (lib "eagle-import") (part "JUMPER-PAD-3-NO2_80"))
    )
    (comp (ref "SJ185")
      (value "JUMPER-PAD-2-NO80")
      (footprint "eagle-import:PAD-JUMPER-2-NO_NO_SILK_80")
      (libsource (lib "eagle-import") (part "JUMPER-PAD-2-NO80"))
    )
    (comp (ref "SJ186")
      (value "JUMPER-PAD-2-NO80")
      (footprint "eagle-import:PAD-JUMPER-2-NO_NO_SILK_80")
      (libsource (lib "eagle-import") (part "JUMPER-PAD-2-NO80"))
    )
    (comp (ref "SJ187")
      (value "JUMPER-PAD-3-NO2_80")
      (footprint "eagle-import:PAD-JUMPER-3-NO_YES_SILK_80")
      (libsource (lib "eagle-import") (part "JUMPER-PAD-3-NO2_80"))
    )
    (comp (ref "SJ188")
      (value "JUMPER-PAD-3-NO2_80")
      (footprint "eagle-import:PAD-JUMPER-3-NO_YES_SILK_80")
      (libsource (lib "eagle-import") (part "JUMPER-PAD-3-NO2_80"))
    )
    (comp (ref "SJ189")
      (value "JUMPER-PAD-2-NO80")
      (footprint "eagle-import:PAD-JUMPER-2-NO_NO_SILK_80")
      (libsource (lib "eagle-import") (part "JUMPER-PAD-2-NO80"))
    )
    (comp (ref "SJ190")
      (value "JUMPER-PAD-2-NO80")
      (footprint "eagle-import:PAD-JUMPER-2-NO_NO_SILK_80")
      (libsource (lib "eagle-import") (part "JUMPER-PAD-2-NO80"))
    )
    (comp (ref "SJ191")
      (value "JUMPER-PAD-3-NO2_80")
      (footprint "eagle-import:PAD-JUMPER-3-NO_YES_SILK_80")
      (libsource (lib "eagle-import") (part "JUMPER-PAD-3-NO2_80"))
    )
    (comp (ref "SJ192")
      (value "JUMPER-PAD-3-NO2_80")
      (footprint "eagle-import:PAD-JUMPER-3-NO_YES_SILK_80")
      (libsource (lib "eagle-import") (part "JUMPER-PAD-3-NO2_80"))
    )
    (comp (ref "SJ193")
      (value "JUMPER-PAD-3-NO3_80")
      (footprint "eagle-import:PAD-JUMPER-3-NO_YES_SILK_ALL_80")
      (libsource (lib "eagle-import") (part "JUMPER-PAD-3-NO3_80"))
    )
    (comp (ref "SJ194")
      (value "JUMPER-PAD-3-NO3_80")
      (footprint "eagle-import:PAD-JUMPER-3-NO_YES_SILK_ALL_80")
      (libsource (lib "eagle-import") (part "JUMPER-PAD-3-NO3_80"))
    )
    (comp (ref "SJ195")
      (value "JUMPER-PAD-3-NO3_80")
      (footprint "eagle-import:PAD-JUMPER-3-NO_YES_SILK_ALL_80")
      (libsource (lib "eagle-import") (part "JUMPER-PAD-3-NO3_80"))
    )
    (comp (ref "SJ196")
      (value "JUMPER-PAD-3-NO3_80")
      (footprint "eagle-import:PAD-JUMPER-3-NO_YES_SILK_ALL_80")
      (libsource (lib "eagle-import") (part "JUMPER-PAD-3-NO3_80"))
    )
    (comp (ref "SJ197")
      (value "JUMPER-PAD-3-NO3_80")
      (footprint "eagle-import:PAD-JUMPER-3-NO_YES_SILK_ALL_80")
      (libsource (lib "eagle-import") (part "JUMPER-PAD-3-NO3_80"))
    )
    (comp (ref "SJ198")
      (value "JUMPER-PAD-3-NO3_80")
      (footprint "eagle-import:PAD-JUMPER-3-NO_YES_SILK_ALL_80")
      (libsource (lib "eagle-import") (part "JUMPER-PAD-3-NO3_80"))
    )
    (comp (ref "SJ199")
      (value "JUMPER-PAD-3-NO3_80")
      (footprint "eagle-import:PAD-JUMPER-3-NO_YES_SILK_ALL_80")
      (libsource (lib "eagle-import") (part "JUMPER-PAD-3-NO3_80"))
    )
    (comp (ref "SJ200")
      (value "JUMPER-PAD-3-NO3_80")
      (footprint "eagle-import:PAD-JUMPER-3-NO_YES_SILK_ALL_80")
      (libsource (lib "eagle-import") (part "JUMPER-PAD-3-NO3_80"))
    )
  )
  (nets
    (net (code "1") (name "GND") (class "Default")
      (node (ref "C101") (pin "2") (pinfunction "2_2") (pintype "passive"))
      (node (ref "C102") (pin "2") (pinfunction "2_2") (pintype "passive"))
      (node (ref "C105") (pin "1") (pinfunction "1_1") (pintype "passive"))
      (node (ref "C106") (pin "1") (pinfunction "1_1") (pintype "passive"))
      (node (ref "C107") (pin "1") (pinfunction "1_1") (pintype "passive"))
      (node (ref "C108") (pin "1") (pinfunction "1_1") (pintype "passive"))
      (node (ref "C125") (pin "2") (pinfunction "2_2") (pintype "passive"))
      (node (ref "C126") (pin "2") (pinfunction "2_2") (pintype "passive"))
      (node (ref "C129") (pin "2") (pinfunction "2_2") (pintype "passive"))
      (node (ref "C130") (pin "2") (pinfunction "2_2") (pintype "passive"))
      (node (ref "C133") (pin "2") (pinfunction "2_2") (pintype "passive"))
      (node (ref "C134") (pin "2") (pinfunction "2_2") (pintype "passive"))
      (node (ref "C137") (pin "2") (pinfunction "2_2") (pintype "passive"))
      (node (ref "C138") (pin "2") (pinfunction "2_2") (pintype "passive"))
      (node (ref "C141") (pin "1") (pinfunction "1_1") (pintype "passive"))
      (node (ref "C142") (pin "1") (pinfunction "1_1") (pintype "passive"))
      (node (ref "C143") (pin "1") (pinfunction "1_1") (pintype "passive"))
      (node (ref "C144") (pin "1") (pinfunction "1_1") (pintype "passive"))
      (node (ref "C161") (pin "2") (pinfunction "2_2") (pintype "passive"))
      (node (ref "C162") (pin "2") (pinfunction "2_2") (pintype "passive"))
      (node (ref "C165") (pin "2") (pinfunction "2_2") (pintype "passive"))
      (node (ref "C166") (pin "2") (pinfunction "2_2") (pintype "passive"))
      (node (ref "C169") (pin "2") (pinfunction "2_2") (pintype "passive"))
      (node (ref "C17") (pin "2") (pinfunction "2_2") (pintype "passive"))
      (node (ref "C170") (pin "2") (pinfunction "2_2") (pintype "passive"))
      (node (ref "C173") (pin "2") (pinfunction "2_2") (pintype "passive"))
      (node (ref "C174") (pin "2") (pinfunction "2_2") (pintype "passive"))
      (node (ref "C177") (pin "1") (pinfunction "1_1") (pintype "passive"))
      (node (ref "C178") (pin "1") (pinfunction "1_1") (pintype "passive"))
      (node (ref "C179") (pin "1") (pinfunction "1_1") (pintype "passive"))
      (node (ref "C18") (pin "2") (pinfunction "2_2") (pintype "passive"))
      (node (ref "C180") (pin "1") (pinfunction "1_1") (pintype "passive"))
      (node (ref "C21") (pin "2") (pinfunction "2_2") (pintype "passive"))
      (node (ref "C22") (pin "2") (pinfunction "2_2") (pintype "passive"))
      (node (ref "C25") (pin "2") (pinfunction "2_2") (pintype "passive"))
      (node (ref "C26") (pin "2") (pinfunction "2_2") (pintype "passive"))
      (node (ref "C29") (pin "2") (pinfunction "2_2") (pintype "passive"))
      (node (ref "C30") (pin "2") (pinfunction "2_2") (pintype "passive"))
      (node (ref "C33") (pin "1") (pinfunction "1_1") (pintype "passive"))
      (node (ref "C34") (pin "1") (pinfunction "1_1") (pintype "passive"))
      (node (ref "C35") (pin "1") (pinfunction "1_1") (pintype "passive"))
      (node (ref "C36") (pin "1") (pinfunction "1_1") (pintype "passive"))
      (node (ref "C53") (pin "2") (pinfunction "2_2") (pintype "passive"))
      (node (ref "C54") (pin "2") (pinfunction "2_2") (pintype "passive"))
      (node (ref "C57") (pin "2") (pinfunction "2_2") (pintype "passive"))
      (node (ref "C58") (pin "2") (pinfunction "2_2") (pintype "passive"))
      (node (ref "C61") (pin "2") (pinfunction "2_2") (pintype "passive"))
      (node (ref "C62") (pin "2") (pinfunction "2_2") (pintype "passive"))
      (node (ref "C65") (pin "2") (pinfunction "2_2") (pintype "passive"))
      (node (ref "C66") (pin "2") (pinfunction "2_2") (pintype "passive"))
      (node (ref "C69") (pin "1") (pinfunction "1_1") (pintype "passive"))
      (node (ref "C70") (pin "1") (pinfunction "1_1") (pintype "passive"))
      (node (ref "C71") (pin "1") (pinfunction "1_1") (pintype "passive"))
      (node (ref "C72") (pin "1") (pinfunction "1_1") (pintype "passive"))
      (node (ref "C89") (pin "2") (pinfunction "2_2") (pintype "passive"))
      (node (ref "C90") (pin "2") (pinfunction "2_2") (pintype "passive"))
      (node (ref "C93") (pin "2") (pinfunction "2_2") (pintype "passive"))
      (node (ref "C94") (pin "2") (pinfunction "2_2") (pintype "passive"))
      (node (ref "C97") (pin "2") (pinfunction "2_2") (pintype "passive"))
      (node (ref "C98") (pin "2") (pinfunction "2_2") (pintype "passive"))
      (node (ref "SJ100") (pin "3") (pinfunction "3_3") (pintype "passive"))
      (node (ref "SJ101") (pin "2") (pinfunction "2_2") (pintype "passive"))
      (node (ref "SJ102") (pin "2") (pinfunction "2_2") (pintype "passive"))
      (node (ref "SJ103") (pin "3") (pinfunction "3_3") (pintype "passive"))
      (node (ref "SJ104") (pin "3") (pinfunction "3_3") (pintype "passive"))
      (node (ref "SJ105") (pin "2") (pinfunction "2_2") (pintype "passive"))
      (node (ref "SJ106") (pin "2") (pinfunction "2_2") (pintype "passive"))
      (node (ref "SJ107") (pin "3") (pinfunction "3_3") (pintype "passive"))
      (node (ref "SJ108") (pin "3") (pinfunction "3_3") (pintype "passive"))
      (node (ref "SJ109") (pin "2") (pinfunction "2_2") (pintype "passive"))
      (node (ref "SJ110") (pin "2") (pinfunction "2_2") (pintype "passive"))
      (node (ref "SJ111") (pin "3") (pinfunction "3_3") (pintype "passive"))
      (node (ref "SJ112") (pin "3") (pinfunction "3_3") (pintype "passive"))
      (node (ref "SJ117") (pin "3") (pinfunction "3_3") (pintype "passive"))
      (node (ref "SJ118") (pin "3") (pinfunction "3_3") (pintype "passive"))
      (node (ref "SJ119") (pin "3") (pinfunction "3_3") (pintype "passive"))
      (node (ref "SJ120") (pin "3") (pinfunction "3_3") (pintype "passive"))
      (node (ref "SJ137") (pin "2") (pinfunction "2_2") (pintype "passive"))
      (node (ref "SJ138") (pin "2") (pinfunction "2_2") (pintype "passive"))
      (node (ref "SJ139") (pin "3") (pinfunction "3_3") (pintype "passive"))
      (node (ref "SJ140") (pin "3") (pinfunction "3_3") (pintype "passive"))
      (node (ref "SJ141") (pin "2") (pinfunction "2_2") (pintype "passive"))
      (node (ref "SJ142") (pin "2") (pinfunction "2_2") (pintype "passive"))
      (node (ref "SJ143") (pin "3") (pinfunction "3_3") (pintype "passive"))
      (node (ref "SJ144") (pin "3") (pinfunction "3_3") (pintype "passive"))
      (node (ref "SJ145") (pin "2") (pinfunction "2_2") (pintype "passive"))
      (node (ref "SJ146") (pin "2") (pinfunction "2_2") (pintype "passive"))
      (node (ref "SJ147") (pin "3") (pinfunction "3_3") (pintype "passive"))
      (node (ref "SJ148") (pin "3") (pinfunction "3_3") (pintype "passive"))
      (node (ref "SJ149") (pin "2") (pinfunction "2_2") (pintype "passive"))
      (node (ref "SJ150") (pin "2") (pinfunction "2_2") (pintype "passive"))
      (node (ref "SJ151") (pin "3") (pinfunction "3_3") (pintype "passive"))
      (node (ref "SJ152") (pin "3") (pinfunction "3_3") (pintype "passive"))
      (node (ref "SJ157") (pin "3") (pinfunction "3_3") (pintype "passive"))
      (node (ref "SJ158") (pin "3") (pinfunction "3_3") (pintype "passive"))
      (node (ref "SJ159") (pin "3") (pinfunction "3_3") (pintype "passive"))
      (node (ref "SJ160") (pin "3") (pinfunction "3_3") (pintype "passive"))
      (node (ref "SJ17") (pin "2") (pinfunction "2_2") (pintype "passive"))
      (node (ref "SJ177") (pin "2") (pinfunction "2_2") (pintype "passive"))
      (node (ref "SJ178") (pin "2") (pinfunction "2_2") (pintype "passive"))
      (node (ref "SJ179") (pin "3") (pinfunction "3_3") (pintype "passive"))
      (node (ref "SJ18") (pin "2") (pinfunction "2_2") (pintype "passive"))
      (node (ref "SJ180") (pin "3") (pinfunction "3_3") (pintype "passive"))
      (node (ref "SJ181") (pin "2") (pinfunction "2_2") (pintype "passive"))
      (node (ref "SJ182") (pin "2") (pinfunction "2_2") (pintype "passive"))
      (node (ref "SJ183") (pin "3") (pinfunction "3_3") (pintype "passive"))
      (node (ref "SJ184") (pin "3") (pinfunction "3_3") (pintype "passive"))
      (node (ref "SJ185") (pin "2") (pinfunction "2_2") (pintype "passive"))
      (node (ref "SJ186") (pin "2") (pinfunction "2_2") (pintype "passive"))
      (node (ref "SJ187") (pin "3") (pinfunction "3_3") (pintype "passive"))
      (node (ref "SJ188") (pin "3") (pinfunction "3_3") (pintype "passive"))
      (node (ref "SJ189") (pin "2") (pinfunction "2_2") (pintype "passive"))
      (node (ref "SJ19") (pin "3") (pinfunction "3_3") (pintype "passive"))
      (node (ref "SJ190") (pin "2") (pinfunction "2_2") (pintype "passive"))
      (node (ref "SJ191") (pin "3") (pinfunction "3_3") (pintype "passive"))
      (node (ref "SJ192") (pin "3") (pinfunction "3_3") (pintype "passive"))
      (node (ref "SJ197") (pin "3") (pinfunction "3_3") (pintype "passive"))
      (node (ref "SJ198") (pin "3") (pinfunction "3_3") (pintype "passive"))
      (node (ref "SJ199") (pin "3") (pinfunction "3_3") (pintype "passive"))
      (node (ref "SJ20") (pin "3") (pinfunction "3_3") (pintype "passive"))
      (node (ref "SJ200") (pin "3") (pinfunction "3_3") (pintype "passive"))
      (node (ref "SJ25") (pin "3") (pinfunction "3_3") (pintype "passive"))
      (node (ref "SJ26") (pin "3") (pinfunction "3_3") (pintype "passive"))
      (node (ref "SJ27") (pin "3") (pinfunction "3_3") (pintype "passive"))
      (node (ref "SJ28") (pin "3") (pinfunction "3_3") (pintype "passive"))
      (node (ref "SJ33") (pin "2") (pinfunction "2_2") (pintype "passive"))
      (node (ref "SJ34") (pin "2") (pinfunction "2_2") (pintype "passive"))
      (node (ref "SJ35") (pin "3") (pinfunction "3_3") (pintype "passive"))
      (node (ref "SJ36") (pin "3") (pinfunction "3_3") (pintype "passive"))
      (node (ref "SJ37") (pin "2") (pinfunction "2_2") (pintype "passive"))
      (node (ref "SJ38") (pin "2") (pinfunction "2_2") (pintype "passive"))
      (node (ref "SJ39") (pin "3") (pinfunction "3_3") (pintype "passive"))
      (node (ref "SJ40") (pin "3") (pinfunction "3_3") (pintype "passive"))
      (node (ref "SJ41") (pin "2") (pinfunction "2_2") (pintype "passive"))
      (node (ref "SJ42") (pin "2") (pinfunction "2_2") (pintype "passive"))
      (node (ref "SJ43") (pin "3") (pinfunction "3_3") (pintype "passive"))
      (node (ref "SJ44") (pin "3") (pinfunction "3_3") (pintype "passive"))
      (node (ref "SJ57") (pin "2") (pinfunction "2_2") (pintype "passive"))
      (node (ref "SJ58") (pin "2") (pinfunction "2_2") (pintype "passive"))
      (node (ref "SJ59") (pin "3") (pinfunction "3_3") (pintype "passive"))
      (node (ref "SJ60") (pin "3") (pinfunction "3_3") (pintype "passive"))
      (node (ref "SJ61") (pin "2") (pinfunction "2_2") (pintype "passive"))
      (node (ref "SJ62") (pin "2") (pinfunction "2_2") (pintype "passive"))
      (node (ref "SJ63") (pin "3") (pinfunction "3_3") (pintype "passive"))
      (node (ref "SJ64") (pin "3") (pinfunction "3_3") (pintype "passive"))
      (node (ref "SJ65") (pin "2") (pinfunction "2_2") (pintype "passive"))
      (node (ref "SJ66") (pin "2") (pinfunction "2_2") (pintype "passive"))
      (node (ref "SJ67") (pin "3") (pinfunction "3_3") (pintype "passive"))
      (node (ref "SJ68") (pin "3") (pinfunction "3_3") (pintype "passive"))
      (node (ref "SJ69") (pin "2") (pinfunction "2_2") (pintype "passive"))
      (node (ref "SJ70") (pin "2") (pinfunction "2_2") (pintype "passive"))
      (node (ref "SJ71") (pin "3") (pinfunction "3_3") (pintype "passive"))
      (node (ref "SJ72") (pin "3") (pinfunction "3_3") (pintype "passive"))
      (node (ref "SJ77") (pin "3") (pinfunction "3_3") (pintype "passive"))
      (node (ref "SJ78") (pin "3") (pinfunction "3_3") (pintype "passive"))
      (node (ref "SJ79") (pin "3") (pinfunction "3_3") (pintype "passive"))
      (node (ref "SJ80") (pin "3") (pinfunction "3_3") (pintype "passive"))
      (node (ref "SJ97") (pin "2") (pinfunction "2_2") (pintype "passive"))
      (node (ref "SJ98") (pin "2") (pinfunction "2_2") (pintype "passive"))
      (node (ref "SJ99") (pin "3") (pinfunction "3_3") (pintype "passive"))
    )
    (net (code "2") (name "Net-(C1-Pad1)") (class "Default")
      (node (ref "C1") (pin "1") (pinfunction "1_1") (pintype "passive"))
      (node (ref "C3") (pin "2") (pinfunction "2_2") (pintype "passive"))
      (node (ref "SJ9") (pin "1") (pinfunction "1_1") (pintype "passive"))
    )
    (net (code "3") (name "Net-(C1-Pad2)") (class "Default")
      (node (ref "C1") (pin "2") (pinfunction "2_2") (pintype "passive"))
      (node (ref "C3") (pin "1") (pinfunction "1_1") (pintype "passive"))
      (node (ref "SJ9") (pin "2") (pinfunction "2_2") (pintype "passive"))
    )
    (net (code "4") (name "Net-(C2-Pad1)") (class "Default")
      (node (ref "C2") (pin "1") (pinfunction "1_1") (pintype "passive"))
      (node (ref "C4") (pin "2") (pinfunction "2_2") (pintype "passive"))
      (node (ref "SJ10") (pin "1") (pinfunction "1_1") (pintype "passive"))
    )
    (net (code "5") (name "Net-(C2-Pad2)") (class "Default")
      (node (ref "C2") (pin "2") (pinfunction "2_2") (pintype "passive"))
      (node (ref "C4") (pin "1") (pinfunction "1_1") (pintype "passive"))
      (node (ref "SJ10") (pin "2") (pinfunction "2_2") (pintype "passive"))
    )
    (net (code "6") (name "Net-(C5-Pad1)") (class "Default")
      (node (ref "C5") (pin "1") (pinfunction "1_1") (pintype "passive"))
      (node (ref "C6") (pin "2") (pinfunction "2_2") (pintype "passive"))
      (node (ref "SJ11") (pin "2") (pinfunction "2_2") (pintype "passive"))
    )
    (net (code "7") (name "Net-(C5-Pad2)") (class "Default")
      (node (ref "C5") (pin "2") (pinfunction "2_2") (pintype "passive"))
      (node (ref "SJ11") (pin "1") (pinfunction "1_1") (pintype "passive"))
    )
    (net (code "8") (name "Net-(C6-Pad1)") (class "Default")
      (node (ref "C6") (pin "1") (pinfunction "1_1") (pintype "passive"))
      (node (ref "SJ11") (pin "3") (pinfunction "3_3") (pintype "passive"))
    )
    (net (code "9") (name "Net-(C7-Pad1)") (class "Default")
      (node (ref "C7") (pin "1") (pinfunction "1_1") (pintype "passive"))
      (node (ref "SJ12") (pin "3") (pinfunction "3_3") (pintype "passive"))
    )
    (net (code "10") (name "Net-(C7-Pad2)") (class "Default")
      (node (ref "C7") (pin "2") (pinfunction "2_2") (pintype "passive"))
      (node (ref "C8") (pin "1") (pinfunction "1_1") (pintype "passive"))
      (node (ref "SJ12") (pin "2") (pinfunction "2_2") (pintype "passive"))
    )
    (net (code "11") (name "Net-(C8-Pad2)") (class "Default")
      (node (ref "C8") (pin "2") (pinfunction "2_2") (pintype "passive"))
      (node (ref "SJ12") (pin "1") (pinfunction "1_1") (pintype "passive"))
    )
    (net (code "12") (name "Net-(C10-Pad1)") (class "Default")
      (node (ref "C10") (pin "1") (pinfunction "1_1") (pintype "passive"))
      (node (ref "C12") (pin "2") (pinfunction "2_2") (pintype "passive"))
      (node (ref "SJ14") (pin "1") (pinfunction "1_1") (pintype "passive"))
    )
    (net (code "13") (name "Net-(C10-Pad2)") (class "Default")
      (node (ref "C10") (pin "2") (pinfunction "2_2") (pintype "passive"))
      (node (ref "C12") (pin "1") (pinfunction "1_1") (pintype "passive"))
      (node (ref "SJ14") (pin "2") (pinfunction "2_2") (pintype "passive"))
    )
    (net (code "14") (name "Net-(C11-Pad1)") (class "Default")
      (node (ref "C11") (pin "1") (pinfunction "1_1") (pintype "passive"))
      (node (ref "C9") (pin "2") (pinfunction "2_2") (pintype "passive"))
      (node (ref "SJ13") (pin "2") (pinfunction "2_2") (pintype "passive"))
    )
    (net (code "15") (name "Net-(C11-Pad2)") (class "Default")
      (node (ref "C11") (pin "2") (pinfunction "2_2") (pintype "passive"))
      (node (ref "C9") (pin "1") (pinfunction "1_1") (pintype "passive"))
      (node (ref "SJ13") (pin "1") (pinfunction "1_1") (pintype "passive"))
    )
    (net (code "16") (name "Net-(C13-Pad1)") (class "Default")
      (node (ref "C13") (pin "1") (pinfunction "1_1") (pintype "passive"))
      (node (ref "C15") (pin "2") (pinfunction "2_2") (pintype "passive"))
      (node (ref "SJ15") (pin "2") (pinfunction "2_2") (pintype "passive"))
    )
    (net (code "17") (name "Net-(C13-Pad2)") (class "Default")
      (node (ref "C13") (pin "2") (pinfunction "2_2") (pintype "passive"))
      (node (ref "SJ15") (pin "1") (pinfunction "1_1") (pintype "passive"))
    )
    (net (code "18") (name "Net-(C14-Pad1)") (class "Default")
      (node (ref "C14") (pin "1") (pinfunction "1_1") (pintype "passive"))
      (node (ref "C16") (pin "2") (pinfunction "2_2") (pintype "passive"))
      (node (ref "SJ16") (pin "2") (pinfunction "2_2") (pintype "passive"))
    )
    (net (code "19") (name "Net-(C14-Pad2)") (class "Default")
      (node (ref "C14") (pin "2") (pinfunction "2_2") (pintype "passive"))
      (node (ref "SJ16") (pin "1") (pinfunction "1_1") (pintype "passive"))
    )
    (net (code "20") (name "Net-(C15-Pad1)") (class "Default")
      (node (ref "C15") (pin "1") (pinfunction "1_1") (pintype "passive"))
      (node (ref "SJ15") (pin "3") (pinfunction "3_3") (pintype "passive"))
    )
    (net (code "21") (name "Net-(C16-Pad1)") (class "Default")
      (node (ref "C16") (pin "1") (pinfunction "1_1") (pintype "passive"))
      (node (ref "SJ16") (pin "3") (pinfunction "3_3") (pintype "passive"))
    )
    (net (code "22") (name "Net-(C17-Pad1)") (class "Default")
      (node (ref "C17") (pin "1") (pinfunction "1_1") (pintype "passive"))
      (node (ref "SJ17") (pin "1") (pinfunction "1_1") (pintype "passive"))
    )
    (net (code "23") (name "Net-(C18-Pad1)") (class "Default")
      (node (ref "C18") (pin "1") (pinfunction "1_1") (pintype "passive"))
      (node (ref "SJ18") (pin "1") (pinfunction "1_1") (pintype "passive"))
    )
    (net (code "24") (name "Net-(C19-Pad1)") (class "Default")
      (node (ref "C19") (pin "1") (pinfunction "1_1") (pintype "passive"))
      (node (ref "SJ19") (pin "2") (pinfunction "2_2") (pintype "passive"))
    )
    (net (code "25") (name "Net-(C19-Pad2)") (class "Default")
      (node (ref "C19") (pin "2") (pinfunction "2_2") (pintype "passive"))
      (node (ref "SJ19") (pin "1") (pinfunction "1_1") (pintype "passive"))
    )
    (net (code "26") (name "Net-(C20-Pad1)") (class "Default")
      (node (ref "C20") (pin "1") (pinfunction "1_1") (pintype "passive"))
      (node (ref "SJ20") (pin "2") (pinfunction "2_2") (pintype "passive"))
    )
    (net (code "27") (name "Net-(C20-Pad2)") (class "Default")
      (node (ref "C20") (pin "2") (pinfunction "2_2") (pintype "passive"))
      (node (ref "SJ20") (pin "1") (pinfunction "1_1") (pintype "passive"))
    )
    (net (code "28") (name "Net-(C21-Pad1)") (class "Default")
      (node (ref "C21") (pin "1") (pinfunction "1_1") (pintype "passive"))
      (node (ref "SJ33") (pin "1") (pinfunction "1_1") (pintype "passive"))
    )
    (net (code "29") (name "Net-(C22-Pad1)") (class "Default")
      (node (ref "C22") (pin "1") (pinfunction "1_1") (pintype "passive"))
      (node (ref "SJ34") (pin "1") (pinfunction "1_1") (pintype "passive"))
    )
    (net (code "30") (name "Net-(C23-Pad1)") (class "Default")
      (node (ref "C23") (pin "1") (pinfunction "1_1") (pintype "passive"))
      (node (ref "SJ35") (pin "2") (pinfunction "2_2") (pintype "passive"))
    )
    (net (code "31") (name "Net-(C23-Pad2)") (class "Default")
      (node (ref "C23") (pin "2") (pinfunction "2_2") (pintype "passive"))
      (node (ref "SJ35") (pin "1") (pinfunction "1_1") (pintype "passive"))
    )
    (net (code "32") (name "Net-(C24-Pad1)") (class "Default")
      (node (ref "C24") (pin "1") (pinfunction "1_1") (pintype "passive"))
      (node (ref "SJ36") (pin "2") (pinfunction "2_2") (pintype "passive"))
    )
    (net (code "33") (name "Net-(C24-Pad2)") (class "Default")
      (node (ref "C24") (pin "2") (pinfunction "2_2") (pintype "passive"))
      (node (ref "SJ36") (pin "1") (pinfunction "1_1") (pintype "passive"))
    )
    (net (code "34") (name "Net-(C25-Pad1)") (class "Default")
      (node (ref "C25") (pin "1") (pinfunction "1_1") (pintype "passive"))
      (node (ref "SJ37") (pin "1") (pinfunction "1_1") (pintype "passive"))
    )
    (net (code "35") (name "Net-(C26-Pad1)") (class "Default")
      (node (ref "C26") (pin "1") (pinfunction "1_1") (pintype "passive"))
      (node (ref "SJ38") (pin "1") (pinfunction "1_1") (pintype "passive"))
    )
    (net (code "36") (name "Net-(C27-Pad1)") (class "Default")
      (node (ref "C27") (pin "1") (pinfunction "1_1") (pintype "passive"))
      (node (ref "C33") (pin "2") (pinfunction "2_2") (pintype "passive"))
      (node (ref "SJ39") (pin "2") (pinfunction "2_2") (pintype "passive"))
    )
    (net (code "37") (name "Net-(C27-Pad2)") (class "Default")
      (node (ref "C27") (pin "2") (pinfunction "2_2") (pintype "passive"))
      (node (ref "SJ39") (pin "1") (pinfunction "1_1") (pintype "passive"))
    )
    (net (code "38") (name "Net-(C28-Pad1)") (class "Default")
      (node (ref "C28") (pin "1") (pinfunction "1_1") (pintype "passive"))
      (node (ref "C34") (pin "2") (pinfunction "2_2") (pintype "passive"))
      (node (ref "SJ40") (pin "2") (pinfunction "2_2") (pintype "passive"))
    )
    (net (code "39") (name "Net-(C28-Pad2)") (class "Default")
      (node (ref "C28") (pin "2") (pinfunction "2_2") (pintype "passive"))
      (node (ref "SJ40") (pin "1") (pinfunction "1_1") (pintype "passive"))
    )
    (net (code "40") (name "Net-(C29-Pad1)") (class "Default")
      (node (ref "C29") (pin "1") (pinfunction "1_1") (pintype "passive"))
      (node (ref "SJ41") (pin "1") (pinfunction "1_1") (pintype "passive"))
    )
    (net (code "41") (name "Net-(C30-Pad1)") (class "Default")
      (node (ref "C30") (pin "1") (pinfunction "1_1") (pintype "passive"))
      (node (ref "SJ42") (pin "1") (pinfunction "1_1") (pintype "passive"))
    )
    (net (code "42") (name "Net-(C31-Pad1)") (class "Default")
      (node (ref "C31") (pin "1") (pinfunction "1_1") (pintype "passive"))
      (node (ref "C35") (pin "2") (pinfunction "2_2") (pintype "passive"))
      (node (ref "SJ43") (pin "2") (pinfunction "2_2") (pintype "passive"))
    )
    (net (code "43") (name "Net-(C31-Pad2)") (class "Default")
      (node (ref "C31") (pin "2") (pinfunction "2_2") (pintype "passive"))
      (node (ref "SJ43") (pin "1") (pinfunction "1_1") (pintype "passive"))
    )
    (net (code "44") (name "Net-(C32-Pad1)") (class "Default")
      (node (ref "C32") (pin "1") (pinfunction "1_1") (pintype "passive"))
      (node (ref "C36") (pin "2") (pinfunction "2_2") (pintype "passive"))
      (node (ref "SJ44") (pin "2") (pinfunction "2_2") (pintype "passive"))
    )
    (net (code "45") (name "Net-(C32-Pad2)") (class "Default")
      (node (ref "C32") (pin "2") (pinfunction "2_2") (pintype "passive"))
      (node (ref "SJ44") (pin "1") (pinfunction "1_1") (pintype "passive"))
    )
    (net (code "46") (name "Net-(C37-Pad1)") (class "Default")
      (node (ref "C37") (pin "1") (pinfunction "1_1") (pintype "passive"))
      (node (ref "C39") (pin "2") (pinfunction "2_2") (pintype "passive"))
      (node (ref "SJ49") (pin "1") (pinfunction "1_1") (pintype "passive"))
    )
    (net (code "47") (name "Net-(C37-Pad2)") (class "Default")
      (node (ref "C37") (pin "2") (pinfunction "2_2") (pintype "passive"))
      (node (ref "C39") (pin "1") (pinfunction "1_1") (pintype "passive"))
      (node (ref "SJ49") (pin "2") (pinfunction "2_2") (pintype "passive"))
    )
    (net (code "48") (name "Net-(C38-Pad1)") (class "Default")
      (node (ref "C38") (pin "1") (pinfunction "1_1") (pintype "passive"))
      (node (ref "C40") (pin "2") (pinfunction "2_2") (pintype "passive"))
      (node (ref "SJ50") (pin "1") (pinfunction "1_1") (pintype "passive"))
    )
    (net (code "49") (name "Net-(C38-Pad2)") (class "Default")
      (node (ref "C38") (pin "2") (pinfunction "2_2") (pintype "passive"))
      (node (ref "C40") (pin "1") (pinfunction "1_1") (pintype "passive"))
      (node (ref "SJ50") (pin "2") (pinfunction "2_2") (pintype "passive"))
    )
    (net (code "50") (name "Net-(C41-Pad1)") (class "Default")
      (node (ref "C41") (pin "1") (pinfunction "1_1") (pintype "passive"))
      (node (ref "C42") (pin "2") (pinfunction "2_2") (pintype "passive"))
      (node (ref "SJ51") (pin "2") (pinfunction "2_2") (pintype "passive"))
    )
    (net (code "51") (name "Net-(C41-Pad2)") (class "Default")
      (node (ref "C41") (pin "2") (pinfunction "2_2") (pintype "passive"))
      (node (ref "SJ51") (pin "1") (pinfunction "1_1") (pintype "passive"))
    )
    (net (code "52") (name "Net-(C42-Pad1)") (class "Default")
      (node (ref "C42") (pin "1") (pinfunction "1_1") (pintype "passive"))
      (node (ref "SJ51") (pin "3") (pinfunction "3_3") (pintype "passive"))
    )
    (net (code "53") (name "Net-(C43-Pad1)") (class "Default")
      (node (ref "C43") (pin "1") (pinfunction "1_1") (pintype "passive"))
      (node (ref "SJ52") (pin "3") (pinfunction "3_3") (pintype "passive"))
    )
    (net (code "54") (name "Net-(C43-Pad2)") (class "Default")
      (node (ref "C43") (pin "2") (pinfunction "2_2") (pintype "passive"))
      (node (ref "C44") (pin "1") (pinfunction "1_1") (pintype "passive"))
      (node (ref "SJ52") (pin "2") (pinfunction "2_2") (pintype "passive"))
    )
    (net (code "55") (name "Net-(C44-Pad2)") (class "Default")
      (node (ref "C44") (pin "2") (pinfunction "2_2") (pintype "passive"))
      (node (ref "SJ52") (pin "1") (pinfunction "1_1") (pintype "passive"))
    )
    (net (code "56") (name "Net-(C45-Pad1)") (class "Default")
      (node (ref "C45") (pin "1") (pinfunction "1_1") (pintype "passive"))
      (node (ref "C47") (pin "2") (pinfunction "2_2") (pintype "passive"))
      (node (ref "SJ53") (pin "1") (pinfunction "1_1") (pintype "passive"))
    )
    (net (code "57") (name "Net-(C45-Pad2)") (class "Default")
      (node (ref "C45") (pin "2") (pinfunction "2_2") (pintype "passive"))
      (node (ref "C47") (pin "1") (pinfunction "1_1") (pintype "passive"))
      (node (ref "SJ53") (pin "2") (pinfunction "2_2") (pintype "passive"))
    )
    (net (code "58") (name "Net-(C46-Pad1)") (class "Default")
      (node (ref "C46") (pin "1") (pinfunction "1_1") (pintype "passive"))
      (node (ref "C48") (pin "2") (pinfunction "2_2") (pintype "passive"))
      (node (ref "SJ54") (pin "1") (pinfunction "1_1") (pintype "passive"))
    )
    (net (code "59") (name "Net-(C46-Pad2)") (class "Default")
      (node (ref "C46") (pin "2") (pinfunction "2_2") (pintype "passive"))
      (node (ref "C48") (pin "1") (pinfunction "1_1") (pintype "passive"))
      (node (ref "SJ54") (pin "2") (pinfunction "2_2") (pintype "passive"))
    )
    (net (code "60") (name "Net-(C49-Pad1)") (class "Default")
      (node (ref "C49") (pin "1") (pinfunction "1_1") (pintype "passive"))
      (node (ref "C51") (pin "2") (pinfunction "2_2") (pintype "passive"))
      (node (ref "SJ55") (pin "2") (pinfunction "2_2") (pintype "passive"))
    )
    (net (code "61") (name "Net-(C49-Pad2)") (class "Default")
      (node (ref "C49") (pin "2") (pinfunction "2_2") (pintype "passive"))
      (node (ref "SJ55") (pin "1") (pinfunction "1_1") (pintype "passive"))
    )
    (net (code "62") (name "Net-(C50-Pad1)") (class "Default")
      (node (ref "C50") (pin "1") (pinfunction "1_1") (pintype "passive"))
      (node (ref "C52") (pin "2") (pinfunction "2_2") (pintype "passive"))
      (node (ref "SJ56") (pin "2") (pinfunction "2_2") (pintype "passive"))
    )
    (net (code "63") (name "Net-(C50-Pad2)") (class "Default")
      (node (ref "C50") (pin "2") (pinfunction "2_2") (pintype "passive"))
      (node (ref "SJ56") (pin "1") (pinfunction "1_1") (pintype "passive"))
    )
    (net (code "64") (name "Net-(C51-Pad1)") (class "Default")
      (node (ref "C51") (pin "1") (pinfunction "1_1") (pintype "passive"))
      (node (ref "SJ55") (pin "3") (pinfunction "3_3") (pintype "passive"))
    )
    (net (code "65") (name "Net-(C52-Pad1)") (class "Default")
      (node (ref "C52") (pin "1") (pinfunction "1_1") (pintype "passive"))
      (node (ref "SJ56") (pin "3") (pinfunction "3_3") (pintype "passive"))
    )
    (net (code "66") (name "Net-(C53-Pad1)") (class "Default")
      (node (ref "C53") (pin "1") (pinfunction "1_1") (pintype "passive"))
      (node (ref "SJ57") (pin "1") (pinfunction "1_1") (pintype "passive"))
    )
    (net (code "67") (name "Net-(C54-Pad1)") (class "Default")
      (node (ref "C54") (pin "1") (pinfunction "1_1") (pintype "passive"))
      (node (ref "SJ58") (pin "1") (pinfunction "1_1") (pintype "passive"))
    )
    (net (code "68") (name "Net-(C55-Pad1)") (class "Default")
      (node (ref "C55") (pin "1") (pinfunction "1_1") (pintype "passive"))
      (node (ref "SJ59") (pin "2") (pinfunction "2_2") (pintype "passive"))
    )
    (net (code "69") (name "Net-(C55-Pad2)") (class "Default")
      (node (ref "C55") (pin "2") (pinfunction "2_2") (pintype "passive"))
      (node (ref "SJ59") (pin "1") (pinfunction "1_1") (pintype "passive"))
    )
    (net (code "70") (name "Net-(C56-Pad1)") (class "Default")
      (node (ref "C56") (pin "1") (pinfunction "1_1") (pintype "passive"))
      (node (ref "SJ60") (pin "2") (pinfunction "2_2") (pintype "passive"))
    )
    (net (code "71") (name "Net-(C56-Pad2)") (class "Default")
      (node (ref "C56") (pin "2") (pinfunction "2_2") (pintype "passive"))
      (node (ref "SJ60") (pin "1") (pinfunction "1_1") (pintype "passive"))
    )
    (net (code "72") (name "Net-(C57-Pad1)") (class "Default")
      (node (ref "C57") (pin "1") (pinfunction "1_1") (pintype "passive"))
      (node (ref "SJ61") (pin "1") (pinfunction "1_1") (pintype "passive"))
    )
    (net (code "73") (name "Net-(C58-Pad1)") (class "Default")
      (node (ref "C58") (pin "1") (pinfunction "1_1") (pintype "passive"))
      (node (ref "SJ62") (pin "1") (pinfunction "1_1") (pintype "passive"))
    )
    (net (code "74") (name "Net-(C59-Pad1)") (class "Default")
      (node (ref "C59") (pin "1") (pinfunction "1_1") (pintype "passive"))
      (node (ref "SJ63") (pin "2") (pinfunction "2_2") (pintype "passive"))
    )
    (net (code "75") (name "Net-(C59-Pad2)") (class "Default")
      (node (ref "C59") (pin "2") (pinfunction "2_2") (pintype "passive"))
      (node (ref "SJ63") (pin "1") (pinfunction "1_1") (pintype "passive"))
    )
    (net (code "76") (name "Net-(C60-Pad1)") (class "Default")
      (node (ref "C60") (pin "1") (pinfunction "1_1") (pintype "passive"))
      (node (ref "SJ64") (pin "2") (pinfunction "2_2") (pintype "passive"))
    )
    (net (code "77") (name "Net-(C60-Pad2)") (class "Default")
      (node (ref "C60") (pin "2") (pinfunction "2_2") (pintype "passive"))
      (node (ref "SJ64") (pin "1") (pinfunction "1_1") (pintype "passive"))
    )
    (net (code "78") (name "Net-(C61-Pad1)") (class "Default")
      (node (ref "C61") (pin "1") (pinfunction "1_1") (pintype "passive"))
      (node (ref "SJ65") (pin "1") (pinfunction "1_1") (pintype "passive"))
    )
    (net (code "79") (name "Net-(C62-Pad1)") (class "Default")
      (node (ref "C62") (pin "1") (pinfunction "1_1") (pintype "passive"))
      (node (ref "SJ66") (pin "1") (pinfunction "1_1") (pintype "passive"))
    )
    (net (code "80") (name "Net-(C63-Pad1)") (class "Default")
      (node (ref "C63") (pin "1") (pinfunction "1_1") (pintype "passive"))
      (node (ref "C69") (pin "2") (pinfunction "2_2") (pintype "passive"))
      (node (ref "SJ67") (pin "2") (pinfunction "2_2") (pintype "passive"))
    )
    (net (code "81") (name "Net-(C63-Pad2)") (class "Default")
      (node (ref "C63") (pin "2") (pinfunction "2_2") (pintype "passive"))
      (node (ref "SJ67") (pin "1") (pinfunction "1_1") (pintype "passive"))
    )
    (net (code "82") (name "Net-(C64-Pad1)") (class "Default")
      (node (ref "C64") (pin "1") (pinfunction "1_1") (pintype "passive"))
      (node (ref "C70") (pin "2") (pinfunction "2_2") (pintype "passive"))
      (node (ref "SJ68") (pin "2") (pinfunction "2_2") (pintype "passive"))
    )
    (net (code "83") (name "Net-(C64-Pad2)") (class "Default")
      (node (ref "C64") (pin "2") (pinfunction "2_2") (pintype "passive"))
      (node (ref "SJ68") (pin "1") (pinfunction "1_1") (pintype "passive"))
    )
    (net (code "84") (name "Net-(C65-Pad1)") (class "Default")
      (node (ref "C65") (pin "1") (pinfunction "1_1") (pintype "passive"))
      (node (ref "SJ69") (pin "1") (pinfunction "1_1") (pintype "passive"))
    )
    (net (code "85") (name "Net-(C66-Pad1)") (class "Default")
      (node (ref "C66") (pin "1") (pinfunction "1_1") (pintype "passive"))
      (node (ref "SJ70") (pin "1") (pinfunction "1_1") (pintype "passive"))
    )
    (net (code "86") (name "Net-(C67-Pad1)") (class "Default")
      (node (ref "C67") (pin "1") (pinfunction "1_1") (pintype "passive"))
      (node (ref "C71") (pin "2") (pinfunction "2_2") (pintype "passive"))
      (node (ref "SJ71") (pin "2") (pinfunction "2_2") (pintype "passive"))
    )
    (net (code "87") (name "Net-(C67-Pad2)") (class "Default")
      (node (ref "C67") (pin "2") (pinfunction "2_2") (pintype "passive"))
      (node (ref "SJ71") (pin "1") (pinfunction "1_1") (pintype "passive"))
    )
    (net (code "88") (name "Net-(C68-Pad1)") (class "Default")
      (node (ref "C68") (pin "1") (pinfunction "1_1") (pintype "passive"))
      (node (ref "C72") (pin "2") (pinfunction "2_2") (pintype "passive"))
      (node (ref "SJ72") (pin "2") (pinfunction "2_2") (pintype "passive"))
    )
    (net (code "89") (name "Net-(C68-Pad2)") (class "Default")
      (node (ref "C68") (pin "2") (pinfunction "2_2") (pintype "passive"))
      (node (ref "SJ72") (pin "1") (pinfunction "1_1") (pintype "passive"))
    )
    (net (code "90") (name "Net-(C73-Pad1)") (class "Default")
      (node (ref "C73") (pin "1") (pinfunction "1_1") (pintype "passive"))
      (node (ref "C75") (pin "2") (pinfunction "2_2") (pintype "passive"))
      (node (ref "SJ89") (pin "1") (pinfunction "1_1") (pintype "passive"))
    )
    (net (code "91") (name "Net-(C73-Pad2)") (class "Default")
      (node (ref "C73") (pin "2") (pinfunction "2_2") (pintype "passive"))
      (node (ref "C75") (pin "1") (pinfunction "1_1") (pintype "passive"))
      (node (ref "SJ89") (pin "2") (pinfunction "2_2") (pintype "passive"))
    )
    (net (code "92") (name "Net-(C74-Pad1)") (class "Default")
      (node (ref "C74") (pin "1") (pinfunction "1_1") (pintype "passive"))
      (node (ref "C76") (pin "2") (pinfunction "2_2") (pintype "passive"))
      (node (ref "SJ90") (pin "1") (pinfunction "1_1") (pintype "passive"))
    )
    (net (code "93") (name "Net-(C74-Pad2)") (class "Default")
      (node (ref "C74") (pin "2") (pinfunction "2_2") (pintype "passive"))
      (node (ref "C76") (pin "1") (pinfunction "1_1") (pintype "passive"))
      (node (ref "SJ90") (pin "2") (pinfunction "2_2") (pintype "passive"))
    )
    (net (code "94") (name "Net-(C77-Pad1)") (class "Default")
      (node (ref "C77") (pin "1") (pinfunction "1_1") (pintype "passive"))
      (node (ref "C78") (pin "2") (pinfunction "2_2") (pintype "passive"))
      (node (ref "SJ91") (pin "2") (pinfunction "2_2") (pintype "passive"))
    )
    (net (code "95") (name "Net-(C77-Pad2)") (class "Default")
      (node (ref "C77") (pin "2") (pinfunction "2_2") (pintype "passive"))
      (node (ref "SJ91") (pin "1") (pinfunction "1_1") (pintype "passive"))
    )
    (net (code "96") (name "Net-(C78-Pad1)") (class "Default")
      (node (ref "C78") (pin "1") (pinfunction "1_1") (pintype "passive"))
      (node (ref "SJ91") (pin "3") (pinfunction "3_3") (pintype "passive"))
    )
    (net (code "97") (name "Net-(C79-Pad1)") (class "Default")
      (node (ref "C79") (pin "1") (pinfunction "1_1") (pintype "passive"))
      (node (ref "SJ92") (pin "3") (pinfunction "3_3") (pintype "passive"))
    )
    (net (code "98") (name "Net-(C79-Pad2)") (class "Default")
      (node (ref "C79") (pin "2") (pinfunction "2_2") (pintype "passive"))
      (node (ref "C80") (pin "1") (pinfunction "1_1") (pintype "passive"))
      (node (ref "SJ92") (pin "2") (pinfunction "2_2") (pintype "passive"))
    )
    (net (code "99") (name "Net-(C80-Pad2)") (class "Default")
      (node (ref "C80") (pin "2") (pinfunction "2_2") (pintype "passive"))
      (node (ref "SJ92") (pin "1") (pinfunction "1_1") (pintype "passive"))
    )
    (net (code "100") (name "Net-(C81-Pad1)") (class "Default")
      (node (ref "C81") (pin "1") (pinfunction "1_1") (pintype "passive"))
      (node (ref "C83") (pin "2") (pinfunction "2_2") (pintype "passive"))
      (node (ref "SJ93") (pin "1") (pinfunction "1_1") (pintype "passive"))
    )
    (net (code "101") (name "Net-(C81-Pad2)") (class "Default")
      (node (ref "C81") (pin "2") (pinfunction "2_2") (pintype "passive"))
      (node (ref "C83") (pin "1") (pinfunction "1_1") (pintype "passive"))
      (node (ref "SJ93") (pin "2") (pinfunction "2_2") (pintype "passive"))
    )
    (net (code "102") (name "Net-(C82-Pad1)") (class "Default")
      (node (ref "C82") (pin "1") (pinfunction "1_1") (pintype "passive"))
      (node (ref "C84") (pin "2") (pinfunction "2_2") (pintype "passive"))
      (node (ref "SJ94") (pin "1") (pinfunction "1_1") (pintype "passive"))
    )
    (net (code "103") (name "Net-(C82-Pad2)") (class "Default")
      (node (ref "C82") (pin "2") (pinfunction "2_2") (pintype "passive"))
      (node (ref "C84") (pin "1") (pinfunction "1_1") (pintype "passive"))
      (node (ref "SJ94") (pin "2") (pinfunction "2_2") (pintype "passive"))
    )
    (net (code "104") (name "Net-(C85-Pad1)") (class "Default")
      (node (ref "C85") (pin "1") (pinfunction "1_1") (pintype "passive"))
      (node (ref "C87") (pin "2") (pinfunction "2_2") (pintype "passive"))
      (node (ref "SJ95") (pin "2") (pinfunction "2_2") (pintype "passive"))
    )
    (net (code "105") (name "Net-(C85-Pad2)") (class "Default")
      (node (ref "C85") (pin "2") (pinfunction "2_2") (pintype "passive"))
      (node (ref "SJ95") (pin "1") (pinfunction "1_1") (pintype "passive"))
    )
    (net (code "106") (name "Net-(C86-Pad1)") (class "Default")
      (node (ref "C86") (pin "1") (pinfunction "1_1") (pintype "passive"))
      (node (ref "C88") (pin "2") (pinfunction "2_2") (pintype "passive"))
      (node (ref "SJ96") (pin "2") (pinfunction "2_2") (pintype "passive"))
    )
    (net (code "107") (name "Net-(C86-Pad2)") (class "Default")
      (node (ref "C86") (pin "2") (pinfunction "2_2") (pintype "passive"))
      (node (ref "SJ96") (pin "1") (pinfunction "1_1") (pintype "passive"))
    )
    (net (code "108") (name "Net-(C87-Pad1)") (class "Default")
      (node (ref "C87") (pin "1") (pinfunction "1_1") (pintype "passive"))
      (node (ref "SJ95") (pin "3") (pinfunction "3_3") (pintype "passive"))
    )
    (net (code "109") (name "Net-(C88-Pad1)") (class "Default")
      (node (ref "C88") (pin "1") (pinfunction "1_1") (pintype "passive"))
      (node (ref "SJ96") (pin "3") (pinfunction "3_3") (pintype "passive"))
    )
    (net (code "110") (name "Net-(C89-Pad1)") (class "Default")
      (node (ref "C89") (pin "1") (pinfunction "1_1") (pintype "passive"))
      (node (ref "SJ97") (pin "1") (pinfunction "1_1") (pintype "passive"))
    )
    (net (code "111") (name "Net-(C90-Pad1)") (class "Default")
      (node (ref "C90") (pin "1") (pinfunction "1_1") (pintype "passive"))
      (node (ref "SJ98") (pin "1") (pinfunction "1_1") (pintype "passive"))
    )
    (net (code "112") (name "Net-(C91-Pad1)") (class "Default")
      (node (ref "C91") (pin "1") (pinfunction "1_1") (pintype "passive"))
      (node (ref "SJ99") (pin "2") (pinfunction "2_2") (pintype "passive"))
    )
    (net (code "113") (name "Net-(C91-Pad2)") (class "Default")
      (node (ref "C91") (pin "2") (pinfunction "2_2") (pintype "passive"))
      (node (ref "SJ99") (pin "1") (pinfunction "1_1") (pintype "passive"))
    )
    (net (code "114") (name "Net-(C92-Pad1)") (class "Default")
      (node (ref "C92") (pin "1") (pinfunction "1_1") (pintype "passive"))
      (node (ref "SJ100") (pin "2") (pinfunction "2_2") (pintype "passive"))
    )
    (net (code "115") (name "Net-(C92-Pad2)") (class "Default")
      (node (ref "C92") (pin "2") (pinfunction "2_2") (pintype "passive"))
      (node (ref "SJ100") (pin "1") (pinfunction "1_1") (pintype "passive"))
    )
    (net (code "116") (name "Net-(C93-Pad1)") (class "Default")
      (node (ref "C93") (pin "1") (pinfunction "1_1") (pintype "passive"))
      (node (ref "SJ101") (pin "1") (pinfunction "1_1") (pintype "passive"))
    )
    (net (code "117") (name "Net-(C94-Pad1)") (class "Default")
      (node (ref "C94") (pin "1") (pinfunction "1_1") (pintype "passive"))
      (node (ref "SJ102") (pin "1") (pinfunction "1_1") (pintype "passive"))
    )
    (net (code "118") (name "Net-(C95-Pad1)") (class "Default")
      (node (ref "C95") (pin "1") (pinfunction "1_1") (pintype "passive"))
      (node (ref "SJ103") (pin "2") (pinfunction "2_2") (pintype "passive"))
    )
    (net (code "119") (name "Net-(C95-Pad2)") (class "Default")
      (node (ref "C95") (pin "2") (pinfunction "2_2") (pintype "passive"))
      (node (ref "SJ103") (pin "1") (pinfunction "1_1") (pintype "passive"))
    )
    (net (code "120") (name "Net-(C96-Pad1)") (class "Default")
      (node (ref "C96") (pin "1") (pinfunction "1_1") (pintype "passive"))
      (node (ref "SJ104") (pin "2") (pinfunction "2_2") (pintype "passive"))
    )
    (net (code "121") (name "Net-(C96-Pad2)") (class "Default")
      (node (ref "C96") (pin "2") (pinfunction "2_2") (pintype "passive"))
      (node (ref "SJ104") (pin "1") (pinfunction "1_1") (pintype "passive"))
    )
    (net (code "122") (name "Net-(C97-Pad1)") (class "Default")
      (node (ref "C97") (pin "1") (pinfunction "1_1") (pintype "passive"))
      (node (ref "SJ105") (pin "1") (pinfunction "1_1") (pintype "passive"))
    )
    (net (code "123") (name "Net-(C98-Pad1)") (class "Default")
      (node (ref "C98") (pin "1") (pinfunction "1_1") (pintype "passive"))
      (node (ref "SJ106") (pin "1") (pinfunction "1_1") (pintype "passive"))
    )
    (net (code "124") (name "Net-(C99-Pad2)") (class "Default")
      (node (ref "C99") (pin "2") (pinfunction "2_2") (pintype "passive"))
      (node (ref "SJ107") (pin "1") (pinfunction "1_1") (pintype "passive"))
    )
    (net (code "125") (name "Net-(C100-Pad1)") (class "Default")
      (node (ref "C100") (pin "1") (pinfunction "1_1") (pintype "passive"))
      (node (ref "C106") (pin "2") (pinfunction "2_2") (pintype "passive"))
      (node (ref "SJ108") (pin "2") (pinfunction "2_2") (pintype "passive"))
    )
    (net (code "126") (name "Net-(C100-Pad2)") (class "Default")
      (node (ref "C100") (pin "2") (pinfunction "2_2") (pintype "passive"))
      (node (ref "SJ108") (pin "1") (pinfunction "1_1") (pintype "passive"))
    )
    (net (code "127") (name "Net-(C101-Pad1)") (class "Default")
      (node (ref "C101") (pin "1") (pinfunction "1_1") (pintype "passive"))
      (node (ref "SJ109") (pin "1") (pinfunction "1_1") (pintype "passive"))
    )
    (net (code "128") (name "Net-(C102-Pad1)") (class "Default")
      (node (ref "C102") (pin "1") (pinfunction "1_1") (pintype "passive"))
      (node (ref "SJ110") (pin "1") (pinfunction "1_1") (pintype "passive"))
    )
    (net (code "129") (name "Net-(C103-Pad1)") (class "Default")
      (node (ref "C103") (pin "1") (pinfunction "1_1") (pintype "passive"))
      (node (ref "C107") (pin "2") (pinfunction "2_2") (pintype "passive"))
      (node (ref "SJ111") (pin "2") (pinfunction "2_2") (pintype "passive"))
    )
    (net (code "130") (name "Net-(C103-Pad2)") (class "Default")
      (node (ref "C103") (pin "2") (pinfunction "2_2") (pintype "passive"))
      (node (ref "SJ111") (pin "1") (pinfunction "1_1") (pintype "passive"))
    )
    (net (code "131") (name "Net-(C104-Pad1)") (class "Default")
      (node (ref "C104") (pin "1") (pinfunction "1_1") (pintype "passive"))
      (node (ref "C108") (pin "2") (pinfunction "2_2") (pintype "passive"))
      (node (ref "SJ112") (pin "2") (pinfunction "2_2") (pintype "passive"))
    )
    (net (code "132") (name "Net-(C104-Pad2)") (class "Default")
      (node (ref "C104") (pin "2") (pinfunction "2_2") (pintype "passive"))
      (node (ref "SJ112") (pin "1") (pinfunction "1_1") (pintype "passive"))
    )
    (net (code "133") (name "Net-(C105-Pad2)") (class "Default")
      (node (ref "C105") (pin "2") (pinfunction "2_2") (pintype "passive"))
      (node (ref "C99") (pin "1") (pinfunction "1_1") (pintype "passive"))
      (node (ref "SJ107") (pin "2") (pinfunction "2_2") (pintype "passive"))
    )
    (net (code "134") (name "Net-(C109-Pad1)") (class "Default")
      (node (ref "C109") (pin "1") (pinfunction "1_1") (pintype "passive"))
      (node (ref "C111") (pin "2") (pinfunction "2_2") (pintype "passive"))
      (node (ref "SJ129") (pin "1") (pinfunction "1_1") (pintype "passive"))
    )
    (net (code "135") (name "Net-(C109-Pad2)") (class "Default")
      (node (ref "C109") (pin "2") (pinfunction "2_2") (pintype "passive"))
      (node (ref "C111") (pin "1") (pinfunction "1_1") (pintype "passive"))
      (node (ref "SJ129") (pin "2") (pinfunction "2_2") (pintype "passive"))
    )
    (net (code "136") (name "Net-(C110-Pad1)") (class "Default")
      (node (ref "C110") (pin "1") (pinfunction "1_1") (pintype "passive"))
      (node (ref "C112") (pin "2") (pinfunction "2_2") (pintype "passive"))
      (node (ref "SJ130") (pin "1") (pinfunction "1_1") (pintype "passive"))
    )
    (net (code "137") (name "Net-(C110-Pad2)") (class "Default")
      (node (ref "C110") (pin "2") (pinfunction "2_2") (pintype "passive"))
      (node (ref "C112") (pin "1") (pinfunction "1_1") (pintype "passive"))
      (node (ref "SJ130") (pin "2") (pinfunction "2_2") (pintype "passive"))
    )
    (net (code "138") (name "Net-(C113-Pad1)") (class "Default")
      (node (ref "C113") (pin "1") (pinfunction "1_1") (pintype "passive"))
      (node (ref "C114") (pin "2") (pinfunction "2_2") (pintype "passive"))
      (node (ref "SJ131") (pin "2") (pinfunction "2_2") (pintype "passive"))
    )
    (net (code "139") (name "Net-(C113-Pad2)") (class "Default")
      (node (ref "C113") (pin "2") (pinfunction "2_2") (pintype "passive"))
      (node (ref "SJ131") (pin "1") (pinfunction "1_1") (pintype "passive"))
    )
    (net (code "140") (name "Net-(C114-Pad1)") (class "Default")
      (node (ref "C114") (pin "1") (pinfunction "1_1") (pintype "passive"))
      (node (ref "SJ131") (pin "3") (pinfunction "3_3") (pintype "passive"))
    )
    (net (code "141") (name "Net-(C115-Pad1)") (class "Default")
      (node (ref "C115") (pin "1") (pinfunction "1_1") (pintype "passive"))
      (node (ref "SJ132") (pin "3") (pinfunction "3_3") (pintype "passive"))
    )
    (net (code "142") (name "Net-(C115-Pad2)") (class "Default")
      (node (ref "C115") (pin "2") (pinfunction "2_2") (pintype "passive"))
      (node (ref "C116") (pin "1") (pinfunction "1_1") (pintype "passive"))
      (node (ref "SJ132") (pin "2") (pinfunction "2_2") (pintype "passive"))
    )
    (net (code "143") (name "Net-(C116-Pad2)") (class "Default")
      (node (ref "C116") (pin "2") (pinfunction "2_2") (pintype "passive"))
      (node (ref "SJ132") (pin "1") (pinfunction "1_1") (pintype "passive"))
    )
    (net (code "144") (name "Net-(C117-Pad1)") (class "Default")
      (node (ref "C117") (pin "1") (pinfunction "1_1") (pintype "passive"))
      (node (ref "C119") (pin "2") (pinfunction "2_2") (pintype "passive"))
      (node (ref "SJ133") (pin "1") (pinfunction "1_1") (pintype "passive"))
    )
    (net (code "145") (name "Net-(C117-Pad2)") (class "Default")
      (node (ref "C117") (pin "2") (pinfunction "2_2") (pintype "passive"))
      (node (ref "C119") (pin "1") (pinfunction "1_1") (pintype "passive"))
      (node (ref "SJ133") (pin "2") (pinfunction "2_2") (pintype "passive"))
    )
    (net (code "146") (name "Net-(C118-Pad1)") (class "Default")
      (node (ref "C118") (pin "1") (pinfunction "1_1") (pintype "passive"))
      (node (ref "C120") (pin "2") (pinfunction "2_2") (pintype "passive"))
      (node (ref "SJ134") (pin "1") (pinfunction "1_1") (pintype "passive"))
    )
    (net (code "147") (name "Net-(C118-Pad2)") (class "Default")
      (node (ref "C118") (pin "2") (pinfunction "2_2") (pintype "passive"))
      (node (ref "C120") (pin "1") (pinfunction "1_1") (pintype "passive"))
      (node (ref "SJ134") (pin "2") (pinfunction "2_2") (pintype "passive"))
    )
    (net (code "148") (name "Net-(C121-Pad1)") (class "Default")
      (node (ref "C121") (pin "1") (pinfunction "1_1") (pintype "passive"))
      (node (ref "C123") (pin "2") (pinfunction "2_2") (pintype "passive"))
      (node (ref "SJ135") (pin "2") (pinfunction "2_2") (pintype "passive"))
    )
    (net (code "149") (name "Net-(C121-Pad2)") (class "Default")
      (node (ref "C121") (pin "2") (pinfunction "2_2") (pintype "passive"))
      (node (ref "SJ135") (pin "1") (pinfunction "1_1") (pintype "passive"))
    )
    (net (code "150") (name "Net-(C122-Pad1)") (class "Default")
      (node (ref "C122") (pin "1") (pinfunction "1_1") (pintype "passive"))
      (node (ref "C124") (pin "2") (pinfunction "2_2") (pintype "passive"))
      (node (ref "SJ136") (pin "2") (pinfunction "2_2") (pintype "passive"))
    )
    (net (code "151") (name "Net-(C122-Pad2)") (class "Default")
      (node (ref "C122") (pin "2") (pinfunction "2_2") (pintype "passive"))
      (node (ref "SJ136") (pin "1") (pinfunction "1_1") (pintype "passive"))
    )
    (net (code "152") (name "Net-(C123-Pad1)") (class "Default")
      (node (ref "C123") (pin "1") (pinfunction "1_1") (pintype "passive"))
      (node (ref "SJ135") (pin "3") (pinfunction "3_3") (pintype "passive"))
    )
    (net (code "153") (name "Net-(C124-Pad1)") (class "Default")
      (node (ref "C124") (pin "1") (pinfunction "1_1") (pintype "passive"))
      (node (ref "SJ136") (pin "3") (pinfunction "3_3") (pintype "passive"))
    )
    (net (code "154") (name "Net-(C125-Pad1)") (class "Default")
      (node (ref "C125") (pin "1") (pinfunction "1_1") (pintype "passive"))
      (node (ref "SJ137") (pin "1") (pinfunction "1_1") (pintype "passive"))
    )
    (net (code "155") (name "Net-(C126-Pad1)") (class "Default")
      (node (ref "C126") (pin "1") (pinfunction "1_1") (pintype "passive"))
      (node (ref "SJ138") (pin "1") (pinfunction "1_1") (pintype "passive"))
    )
    (net (code "156") (name "Net-(C127-Pad1)") (class "Default")
      (node (ref "C127") (pin "1") (pinfunction "1_1") (pintype "passive"))
      (node (ref "SJ139") (pin "2") (pinfunction "2_2") (pintype "passive"))
    )
    (net (code "157") (name "Net-(C127-Pad2)") (class "Default")
      (node (ref "C127") (pin "2") (pinfunction "2_2") (pintype "passive"))
      (node (ref "SJ139") (pin "1") (pinfunction "1_1") (pintype "passive"))
    )
    (net (code "158") (name "Net-(C128-Pad1)") (class "Default")
      (node (ref "C128") (pin "1") (pinfunction "1_1") (pintype "passive"))
      (node (ref "SJ140") (pin "2") (pinfunction "2_2") (pintype "passive"))
    )
    (net (code "159") (name "Net-(C128-Pad2)") (class "Default")
      (node (ref "C128") (pin "2") (pinfunction "2_2") (pintype "passive"))
      (node (ref "SJ140") (pin "1") (pinfunction "1_1") (pintype "passive"))
    )
    (net (code "160") (name "Net-(C129-Pad1)") (class "Default")
      (node (ref "C129") (pin "1") (pinfunction "1_1") (pintype "passive"))
      (node (ref "SJ141") (pin "1") (pinfunction "1_1") (pintype "passive"))
    )
    (net (code "161") (name "Net-(C130-Pad1)") (class "Default")
      (node (ref "C130") (pin "1") (pinfunction "1_1") (pintype "passive"))
      (node (ref "SJ142") (pin "1") (pinfunction "1_1") (pintype "passive"))
    )
    (net (code "162") (name "Net-(C131-Pad1)") (class "Default")
      (node (ref "C131") (pin "1") (pinfunction "1_1") (pintype "passive"))
      (node (ref "SJ143") (pin "2") (pinfunction "2_2") (pintype "passive"))
    )
    (net (code "163") (name "Net-(C131-Pad2)") (class "Default")
      (node (ref "C131") (pin "2") (pinfunction "2_2") (pintype "passive"))
      (node (ref "SJ143") (pin "1") (pinfunction "1_1") (pintype "passive"))
    )
    (net (code "164") (name "Net-(C132-Pad1)") (class "Default")
      (node (ref "C132") (pin "1") (pinfunction "1_1") (pintype "passive"))
      (node (ref "SJ144") (pin "2") (pinfunction "2_2") (pintype "passive"))
    )
    (net (code "165") (name "Net-(C132-Pad2)") (class "Default")
      (node (ref "C132") (pin "2") (pinfunction "2_2") (pintype "passive"))
      (node (ref "SJ144") (pin "1") (pinfunction "1_1") (pintype "passive"))
    )
    (net (code "166") (name "Net-(C133-Pad1)") (class "Default")
      (node (ref "C133") (pin "1") (pinfunction "1_1") (pintype "passive"))
      (node (ref "SJ145") (pin "1") (pinfunction "1_1") (pintype "passive"))
    )
    (net (code "167") (name "Net-(C134-Pad1)") (class "Default")
      (node (ref "C134") (pin "1") (pinfunction "1_1") (pintype "passive"))
      (node (ref "SJ146") (pin "1") (pinfunction "1_1") (pintype "passive"))
    )
    (net (code "168") (name "Net-(C135-Pad1)") (class "Default")
      (node (ref "C135") (pin "1") (pinfunction "1_1") (pintype "passive"))
      (node (ref "C141") (pin "2") (pinfunction "2_2") (pintype "passive"))
      (node (ref "SJ147") (pin "2") (pinfunction "2_2") (pintype "passive"))
    )
    (net (code "169") (name "Net-(C135-Pad2)") (class "Default")
      (node (ref "C135") (pin "2") (pinfunction "2_2") (pintype "passive"))
      (node (ref "SJ147") (pin "1") (pinfunction "1_1") (pintype "passive"))
    )
    (net (code "170") (name "Net-(C136-Pad1)") (class "Default")
      (node (ref "C136") (pin "1") (pinfunction "1_1") (pintype "passive"))
      (node (ref "C142") (pin "2") (pinfunction "2_2") (pintype "passive"))
      (node (ref "SJ148") (pin "2") (pinfunction "2_2") (pintype "passive"))
    )
    (net (code "171") (name "Net-(C136-Pad2)") (class "Default")
      (node (ref "C136") (pin "2") (pinfunction "2_2") (pintype "passive"))
      (node (ref "SJ148") (pin "1") (pinfunction "1_1") (pintype "passive"))
    )
    (net (code "172") (name "Net-(C137-Pad1)") (class "Default")
      (node (ref "C137") (pin "1") (pinfunction "1_1") (pintype "passive"))
      (node (ref "SJ149") (pin "1") (pinfunction "1_1") (pintype "passive"))
    )
    (net (code "173") (name "Net-(C138-Pad1)") (class "Default")
      (node (ref "C138") (pin "1") (pinfunction "1_1") (pintype "passive"))
      (node (ref "SJ150") (pin "1") (pinfunction "1_1") (pintype "passive"))
    )
    (net (code "174") (name "Net-(C139-Pad1)") (class "Default")
      (node (ref "C139") (pin "1") (pinfunction "1_1") (pintype "passive"))
      (node (ref "C143") (pin "2") (pinfunction "2_2") (pintype "passive"))
      (node (ref "SJ151") (pin "2") (pinfunction "2_2") (pintype "passive"))
    )
    (net (code "175") (name "Net-(C139-Pad2)") (class "Default")
      (node (ref "C139") (pin "2") (pinfunction "2_2") (pintype "passive"))
      (node (ref "SJ151") (pin "1") (pinfunction "1_1") (pintype "passive"))
    )
    (net (code "176") (name "Net-(C140-Pad1)") (class "Default")
      (node (ref "C140") (pin "1") (pinfunction "1_1") (pintype "passive"))
      (node (ref "C144") (pin "2") (pinfunction "2_2") (pintype "passive"))
      (node (ref "SJ152") (pin "2") (pinfunction "2_2") (pintype "passive"))
    )
    (net (code "177") (name "Net-(C140-Pad2)") (class "Default")
      (node (ref "C140") (pin "2") (pinfunction "2_2") (pintype "passive"))
      (node (ref "SJ152") (pin "1") (pinfunction "1_1") (pintype "passive"))
    )
    (net (code "178") (name "Net-(C145-Pad1)") (class "Default")
      (node (ref "C145") (pin "1") (pinfunction "1_1") (pintype "passive"))
      (node (ref "C147") (pin "2") (pinfunction "2_2") (pintype "passive"))
      (node (ref "SJ169") (pin "1") (pinfunction "1_1") (pintype "passive"))
    )
    (net (code "179") (name "Net-(C145-Pad2)") (class "Default")
      (node (ref "C145") (pin "2") (pinfunction "2_2") (pintype "passive"))
      (node (ref "C147") (pin "1") (pinfunction "1_1") (pintype "passive"))
      (node (ref "SJ169") (pin "2") (pinfunction "2_2") (pintype "passive"))
    )
    (net (code "180") (name "Net-(C146-Pad1)") (class "Default")
      (node (ref "C146") (pin "1") (pinfunction "1_1") (pintype "passive"))
      (node (ref "C148") (pin "2") (pinfunction "2_2") (pintype "passive"))
      (node (ref "SJ170") (pin "1") (pinfunction "1_1") (pintype "passive"))
    )
    (net (code "181") (name "Net-(C146-Pad2)") (class "Default")
      (node (ref "C146") (pin "2") (pinfunction "2_2") (pintype "passive"))
      (node (ref "C148") (pin "1") (pinfunction "1_1") (pintype "passive"))
      (node (ref "SJ170") (pin "2") (pinfunction "2_2") (pintype "passive"))
    )
    (net (code "182") (name "Net-(C149-Pad1)") (class "Default")
      (node (ref "C149") (pin "1") (pinfunction "1_1") (pintype "passive"))
      (node (ref "C150") (pin "2") (pinfunction "2_2") (pintype "passive"))
      (node (ref "SJ171") (pin "2") (pinfunction "2_2") (pintype "passive"))
    )
    (net (code "183") (name "Net-(C149-Pad2)") (class "Default")
      (node (ref "C149") (pin "2") (pinfunction "2_2") (pintype "passive"))
      (node (ref "SJ171") (pin "1") (pinfunction "1_1") (pintype "passive"))
    )
    (net (code "184") (name "Net-(C150-Pad1)") (class "Default")
      (node (ref "C150") (pin "1") (pinfunction "1_1") (pintype "passive"))
      (node (ref "SJ171") (pin "3") (pinfunction "3_3") (pintype "passive"))
    )
    (net (code "185") (name "Net-(C151-Pad1)") (class "Default")
      (node (ref "C151") (pin "1") (pinfunction "1_1") (pintype "passive"))
      (node (ref "SJ172") (pin "3") (pinfunction "3_3") (pintype "passive"))
    )
    (net (code "186") (name "Net-(C151-Pad2)") (class "Default")
      (node (ref "C151") (pin "2") (pinfunction "2_2") (pintype "passive"))
      (node (ref "C152") (pin "1") (pinfunction "1_1") (pintype "passive"))
      (node (ref "SJ172") (pin "2") (pinfunction "2_2") (pintype "passive"))
    )
    (net (code "187") (name "Net-(C152-Pad2)") (class "Default")
      (node (ref "C152") (pin "2") (pinfunction "2_2") (pintype "passive"))
      (node (ref "SJ172") (pin "1") (pinfunction "1_1") (pintype "passive"))
    )
    (net (code "188") (name "Net-(C153-Pad1)") (class "Default")
      (node (ref "C153") (pin "1") (pinfunction "1_1") (pintype "passive"))
      (node (ref "C155") (pin "2") (pinfunction "2_2") (pintype "passive"))
      (node (ref "SJ173") (pin "1") (pinfunction "1_1") (pintype "passive"))
    )
    (net (code "189") (name "Net-(C153-Pad2)") (class "Default")
      (node (ref "C153") (pin "2") (pinfunction "2_2") (pintype "passive"))
      (node (ref "C155") (pin "1") (pinfunction "1_1") (pintype "passive"))
      (node (ref "SJ173") (pin "2") (pinfunction "2_2") (pintype "passive"))
    )
    (net (code "190") (name "Net-(C154-Pad1)") (class "Default")
      (node (ref "C154") (pin "1") (pinfunction "1_1") (pintype "passive"))
      (node (ref "C156") (pin "2") (pinfunction "2_2") (pintype "passive"))
      (node (ref "SJ174") (pin "1") (pinfunction "1_1") (pintype "passive"))
    )
    (net (code "191") (name "Net-(C154-Pad2)") (class "Default")
      (node (ref "C154") (pin "2") (pinfunction "2_2") (pintype "passive"))
      (node (ref "C156") (pin "1") (pinfunction "1_1") (pintype "passive"))
      (node (ref "SJ174") (pin "2") (pinfunction "2_2") (pintype "passive"))
    )
    (net (code "192") (name "Net-(C157-Pad1)") (class "Default")
      (node (ref "C157") (pin "1") (pinfunction "1_1") (pintype "passive"))
      (node (ref "C159") (pin "2") (pinfunction "2_2") (pintype "passive"))
      (node (ref "SJ175") (pin "2") (pinfunction "2_2") (pintype "passive"))
    )
    (net (code "193") (name "Net-(C157-Pad2)") (class "Default")
      (node (ref "C157") (pin "2") (pinfunction "2_2") (pintype "passive"))
      (node (ref "SJ175") (pin "1") (pinfunction "1_1") (pintype "passive"))
    )
    (net (code "194") (name "Net-(C158-Pad1)") (class "Default")
      (node (ref "C158") (pin "1") (pinfunction "1_1") (pintype "passive"))
      (node (ref "C160") (pin "2") (pinfunction "2_2") (pintype "passive"))
      (node (ref "SJ176") (pin "2") (pinfunction "2_2") (pintype "passive"))
    )
    (net (code "195") (name "Net-(C158-Pad2)") (class "Default")
      (node (ref "C158") (pin "2") (pinfunction "2_2") (pintype "passive"))
      (node (ref "SJ176") (pin "1") (pinfunction "1_1") (pintype "passive"))
    )
    (net (code "196") (name "Net-(C159-Pad1)") (class "Default")
      (node (ref "C159") (pin "1") (pinfunction "1_1") (pintype "passive"))
      (node (ref "SJ175") (pin "3") (pinfunction "3_3") (pintype "passive"))
    )
    (net (code "197") (name "Net-(C160-Pad1)") (class "Default")
      (node (ref "C160") (pin "1") (pinfunction "1_1") (pintype "passive"))
      (node (ref "SJ176") (pin "3") (pinfunction "3_3") (pintype "passive"))
    )
    (net (code "198") (name "Net-(C161-Pad1)") (class "Default")
      (node (ref "C161") (pin "1") (pinfunction "1_1") (pintype "passive"))
      (node (ref "SJ177") (pin "1") (pinfunction "1_1") (pintype "passive"))
    )
    (net (code "199") (name "Net-(C162-Pad1)") (class "Default")
      (node (ref "C162") (pin "1") (pinfunction "1_1") (pintype "passive"))
      (node (ref "SJ178") (pin "1") (pinfunction "1_1") (pintype "passive"))
    )
    (net (code "200") (name "Net-(C163-Pad1)") (class "Default")
      (node (ref "C163") (pin "1") (pinfunction "1_1") (pintype "passive"))
      (node (ref "SJ179") (pin "2") (pinfunction "2_2") (pintype "passive"))
    )
    (net (code "201") (name "Net-(C163-Pad2)") (class "Default")
      (node (ref "C163") (pin "2") (pinfunction "2_2") (pintype "passive"))
      (node (ref "SJ179") (pin "1") (pinfunction "1_1") (pintype "passive"))
    )
    (net (code "202") (name "Net-(C164-Pad1)") (class "Default")
      (node (ref "C164") (pin "1") (pinfunction "1_1") (pintype "passive"))
      (node (ref "SJ180") (pin "2") (pinfunction "2_2") (pintype "passive"))
    )
    (net (code "203") (name "Net-(C164-Pad2)") (class "Default")
      (node (ref "C164") (pin "2") (pinfunction "2_2") (pintype "passive"))
      (node (ref "SJ180") (pin "1") (pinfunction "1_1") (pintype "passive"))
    )
    (net (code "204") (name "Net-(C165-Pad1)") (class "Default")
      (node (ref "C165") (pin "1") (pinfunction "1_1") (pintype "passive"))
      (node (ref "SJ181") (pin "1") (pinfunction "1_1") (pintype "passive"))
    )
    (net (code "205") (name "Net-(C166-Pad1)") (class "Default")
      (node (ref "C166") (pin "1") (pinfunction "1_1") (pintype "passive"))
      (node (ref "SJ182") (pin "1") (pinfunction "1_1") (pintype "passive"))
    )
    (net (code "206") (name "Net-(C167-Pad1)") (class "Default")
      (node (ref "C167") (pin "1") (pinfunction "1_1") (pintype "passive"))
      (node (ref "SJ183") (pin "2") (pinfunction "2_2") (pintype "passive"))
    )
    (net (code "207") (name "Net-(C167-Pad2)") (class "Default")
      (node (ref "C167") (pin "2") (pinfunction "2_2") (pintype "passive"))
      (node (ref "SJ183") (pin "1") (pinfunction "1_1") (pintype "passive"))
    )
    (net (code "208") (name "Net-(C168-Pad1)") (class "Default")
      (node (ref "C168") (pin "1") (pinfunction "1_1") (pintype "passive"))
      (node (ref "SJ184") (pin "2") (pinfunction "2_2") (pintype "passive"))
    )
    (net (code "209") (name "Net-(C168-Pad2)") (class "Default")
      (node (ref "C168") (pin "2") (pinfunction "2_2") (pintype "passive"))
      (node (ref "SJ184") (pin "1") (pinfunction "1_1") (pintype "passive"))
    )
    (net (code "210") (name "Net-(C169-Pad1)") (class "Default")
      (node (ref "C169") (pin "1") (pinfunction "1_1") (pintype "passive"))
      (node (ref "SJ185") (pin "1") (pinfunction "1_1") (pintype "passive"))
    )
    (net (code "211") (name "Net-(C170-Pad1)") (class "Default")
      (node (ref "C170") (pin "1") (pinfunction "1_1") (pintype "passive"))
      (node (ref "SJ186") (pin "1") (pinfunction "1_1") (pintype "passive"))
    )
    (net (code "212") (name "Net-(C171-Pad1)") (class "Default")
      (node (ref "C171") (pin "1") (pinfunction "1_1") (pintype "passive"))
      (node (ref "C177") (pin "2") (pinfunction "2_2") (pintype "passive"))
      (node (ref "SJ187") (pin "2") (pinfunction "2_2") (pintype "passive"))
    )
    (net (code "213") (name "Net-(C171-Pad2)") (class "Default")
      (node (ref "C171") (pin "2") (pinfunction "2_2") (pintype "passive"))
      (node (ref "SJ187") (pin "1") (pinfunction "1_1") (pintype "passive"))
    )
    (net (code "214") (name "Net-(C172-Pad1)") (class "Default")
      (node (ref "C172") (pin "1") (pinfunction "1_1") (pintype "passive"))
      (node (ref "C178") (pin "2") (pinfunction "2_2") (pintype "passive"))
      (node (ref "SJ188") (pin "2") (pinfunction "2_2") (pintype "passive"))
    )
    (net (code "215") (name "Net-(C172-Pad2)") (class "Default")
      (node (ref "C172") (pin "2") (pinfunction "2_2") (pintype "passive"))
      (node (ref "SJ188") (pin "1") (pinfunction "1_1") (pintype "passive"))
    )
    (net (code "216") (name "Net-(C173-Pad1)") (class "Default")
      (node (ref "C173") (pin "1") (pinfunction "1_1") (pintype "passive"))
      (node (ref "SJ189") (pin "1") (pinfunction "1_1") (pintype "passive"))
    )
    (net (code "217") (name "Net-(C174-Pad1)") (class "Default")
      (node (ref "C174") (pin "1") (pinfunction "1_1") (pintype "passive"))
      (node (ref "SJ190") (pin "1") (pinfunction "1_1") (pintype "passive"))
    )
    (net (code "218") (name "Net-(C175-Pad1)") (class "Default")
      (node (ref "C175") (pin "1") (pinfunction "1_1") (pintype "passive"))
      (node (ref "C179") (pin "2") (pinfunction "2_2") (pintype "passive"))
      (node (ref "SJ191") (pin "2") (pinfunction "2_2") (pintype "passive"))
    )
    (net (code "219") (name "Net-(C175-Pad2)") (class "Default")
      (node (ref "C175") (pin "2") (pinfunction "2_2") (pintype "passive"))
      (node (ref "SJ191") (pin "1") (pinfunction "1_1") (pintype "passive"))
    )
    (net (code "220") (name "Net-(C176-Pad1)") (class "Default")
      (node (ref "C176") (pin "1") (pinfunction "1_1") (pintype "passive"))
      (node (ref "C180") (pin "2") (pinfunction "2_2") (pintype "passive"))
      (node (ref "SJ192") (pin "2") (pinfunction "2_2") (pintype "passive"))
    )
    (net (code "221") (name "Net-(C176-Pad2)") (class "Default")
      (node (ref "C176") (pin "2") (pinfunction "2_2") (pintype "passive"))
      (node (ref "SJ192") (pin "1") (pinfunction "1_1") (pintype "passive"))
    )
    (net (code "222") (name "unconnected-(SJ1-Pad1)") (class "Default")
      (node (ref "SJ1") (pin "1") (pinfunction "1_1") (pintype "passive"))
    )
    (net (code "223") (name "unconnected-(SJ1-Pad2)") (class "Default")
      (node (ref "SJ1") (pin "2") (pinfunction "2_2") (pintype "passive"))
    )
    (net (code "224") (name "unconnected-(SJ2-Pad1)") (class "Default")
      (node (ref "SJ2") (pin "1") (pinfunction "1_1") (pintype "passive"))
    )
    (net (code "225") (name "unconnected-(SJ2-Pad2)") (class "Default")
      (node (ref "SJ2") (pin "2") (pinfunction "2_2") (pintype "passive"))
    )
    (net (code "226") (name "unconnected-(SJ3-Pad1)") (class "Default")
      (node (ref "SJ3") (pin "1") (pinfunction "1_1") (pintype "passive"))
    )
    (net (code "227") (name "unconnected-(SJ3-Pad2)") (class "Default")
      (node (ref "SJ3") (pin "2") (pinfunction "2_2") (pintype "passive"))
    )
    (net (code "228") (name "unconnected-(SJ3-Pad3)") (class "Default")
      (node (ref "SJ3") (pin "3") (pinfunction "3_3") (pintype "passive"))
    )
    (net (code "229") (name "unconnected-(SJ4-Pad1)") (class "Default")
      (node (ref "SJ4") (pin "1") (pinfunction "1_1") (pintype "passive"))
    )
    (net (code "230") (name "unconnected-(SJ4-Pad2)") (class "Default")
      (node (ref "SJ4") (pin "2") (pinfunction "2_2") (pintype "passive"))
    )
    (net (code "231") (name "unconnected-(SJ4-Pad3)") (class "Default")
      (node (ref "SJ4") (pin "3") (pinfunction "3_3") (pintype "passive"))
    )
    (net (code "232") (name "unconnected-(SJ5-Pad1)") (class "Default")
      (node (ref "SJ5") (pin "1") (pinfunction "1_1") (pintype "passive"))
    )
    (net (code "233") (name "unconnected-(SJ5-Pad2)") (class "Default")
      (node (ref "SJ5") (pin "2") (pinfunction "2_2") (pintype "passive"))
    )
    (net (code "234") (name "unconnected-(SJ6-Pad1)") (class "Default")
      (node (ref "SJ6") (pin "1") (pinfunction "1_1") (pintype "passive"))
    )
    (net (code "235") (name "unconnected-(SJ6-Pad2)") (class "Default")
      (node (ref "SJ6") (pin "2") (pinfunction "2_2") (pintype "passive"))
    )
    (net (code "236") (name "unconnected-(SJ7-Pad1)") (class "Default")
      (node (ref "SJ7") (pin "1") (pinfunction "1_1") (pintype "passive"))
    )
    (net (code "237") (name "unconnected-(SJ7-Pad2)") (class "Default")
      (node (ref "SJ7") (pin "2") (pinfunction "2_2") (pintype "passive"))
    )
    (net (code "238") (name "unconnected-(SJ7-Pad3)") (class "Default")
      (node (ref "SJ7") (pin "3") (pinfunction "3_3") (pintype "passive"))
    )
    (net (code "239") (name "unconnected-(SJ8-Pad1)") (class "Default")
      (node (ref "SJ8") (pin "1") (pinfunction "1_1") (pintype "passive"))
    )
    (net (code "240") (name "unconnected-(SJ8-Pad2)") (class "Default")
      (node (ref "SJ8") (pin "2") (pinfunction "2_2") (pintype "passive"))
    )
    (net (code "241") (name "unconnected-(SJ8-Pad3)") (class "Default")
      (node (ref "SJ8") (pin "3") (pinfunction "3_3") (pintype "passive"))
    )
    (net (code "242") (name "unconnected-(SJ21-Pad1)") (class "Default")
      (node (ref "SJ21") (pin "1") (pinfunction "1_1") (pintype "passive"))
    )
    (net (code "243") (name "unconnected-(SJ21-Pad2)") (class "Default")
      (node (ref "SJ21") (pin "2") (pinfunction "2_2") (pintype "passive"))
    )
    (net (code "244") (name "unconnected-(SJ21-Pad3)") (class "Default")
      (node (ref "SJ21") (pin "3") (pinfunction "3_3") (pintype "passive"))
    )
    (net (code "245") (name "unconnected-(SJ22-Pad1)") (class "Default")
      (node (ref "SJ22") (pin "1") (pinfunction "1_1") (pintype "passive"))
    )
    (net (code "246") (name "unconnected-(SJ22-Pad2)") (class "Default")
      (node (ref "SJ22") (pin "2") (pinfunction "2_2") (pintype "passive"))
    )
    (net (code "247") (name "unconnected-(SJ22-Pad3)") (class "Default")
      (node (ref "SJ22") (pin "3") (pinfunction "3_3") (pintype "passive"))
    )
    (net (code "248") (name "unconnected-(SJ23-Pad1)") (class "Default")
      (node (ref "SJ23") (pin "1") (pinfunction "1_1") (pintype "passive"))
    )
    (net (code "249") (name "unconnected-(SJ23-Pad2)") (class "Default")
      (node (ref "SJ23") (pin "2") (pinfunction "2_2") (pintype "passive"))
    )
    (net (code "250") (name "unconnected-(SJ23-Pad3)") (class "Default")
      (node (ref "SJ23") (pin "3") (pinfunction "3_3") (pintype "passive"))
    )
    (net (code "251") (name "unconnected-(SJ24-Pad1)") (class "Default")
      (node (ref "SJ24") (pin "1") (pinfunction "1_1") (pintype "passive"))
    )
    (net (code "252") (name "unconnected-(SJ24-Pad2)") (class "Default")
      (node (ref "SJ24") (pin "2") (pinfunction "2_2") (pintype "passive"))
    )
    (net (code "253") (name "unconnected-(SJ24-Pad3)") (class "Default")
      (node (ref "SJ24") (pin "3") (pinfunction "3_3") (pintype "passive"))
    )
    (net (code "254") (name "unconnected-(SJ25-Pad1)") (class "Default")
      (node (ref "SJ25") (pin "1") (pinfunction "1_1") (pintype "passive"))
    )
    (net (code "255") (name "unconnected-(SJ25-Pad2)") (class "Default")
      (node (ref "SJ25") (pin "2") (pinfunction "2_2") (pintype "passive"))
    )
    (net (code "256") (name "unconnected-(SJ26-Pad1)") (class "Default")
      (node (ref "SJ26") (pin "1") (pinfunction "1_1") (pintype "passive"))
    )
    (net (code "257") (name "unconnected-(SJ26-Pad2)") (class "Default")
      (node (ref "SJ26") (pin "2") (pinfunction "2_2") (pintype "passive"))
    )
    (net (code "258") (name "unconnected-(SJ27-Pad1)") (class "Default")
      (node (ref "SJ27") (pin "1") (pinfunction "1_1") (pintype "passive"))
    )
    (net (code "259") (name "unconnected-(SJ27-Pad2)") (class "Default")
      (node (ref "SJ27") (pin "2") (pinfunction "2_2") (pintype "passive"))
    )
    (net (code "260") (name "unconnected-(SJ28-Pad1)") (class "Default")
      (node (ref "SJ28") (pin "1") (pinfunction "1_1") (pintype "passive"))
    )
    (net (code "261") (name "unconnected-(SJ28-Pad2)") (class "Default")
      (node (ref "SJ28") (pin "2") (pinfunction "2_2") (pintype "passive"))
    )
    (net (code "262") (name "unconnected-(SJ29-Pad1)") (class "Default")
      (node (ref "SJ29") (pin "1") (pinfunction "1_1") (pintype "passive"))
    )
    (net (code "263") (name "unconnected-(SJ29-Pad2)") (class "Default")
      (node (ref "SJ29") (pin "2") (pinfunction "2_2") (pintype "passive"))
    )
    (net (code "264") (name "unconnected-(SJ30-Pad1)") (class "Default")
      (node (ref "SJ30") (pin "1") (pinfunction "1_1") (pintype "passive"))
    )
    (net (code "265") (name "unconnected-(SJ30-Pad2)") (class "Default")
      (node (ref "SJ30") (pin "2") (pinfunction "2_2") (pintype "passive"))
    )
    (net (code "266") (name "unconnected-(SJ31-Pad1)") (class "Default")
      (node (ref "SJ31") (pin "1") (pinfunction "1_1") (pintype "passive"))
    )
    (net (code "267") (name "unconnected-(SJ31-Pad2)") (class "Default")
      (node (ref "SJ31") (pin "2") (pinfunction "2_2") (pintype "passive"))
    )
    (net (code "268") (name "unconnected-(SJ31-Pad3)") (class "Default")
      (node (ref "SJ31") (pin "3") (pinfunction "3_3") (pintype "passive"))
    )
    (net (code "269") (name "unconnected-(SJ32-Pad1)") (class "Default")
      (node (ref "SJ32") (pin "1") (pinfunction "1_1") (pintype "passive"))
    )
    (net (code "270") (name "unconnected-(SJ32-Pad2)") (class "Default")
      (node (ref "SJ32") (pin "2") (pinfunction "2_2") (pintype "passive"))
    )
    (net (code "271") (name "unconnected-(SJ32-Pad3)") (class "Default")
      (node (ref "SJ32") (pin "3") (pinfunction "3_3") (pintype "passive"))
    )
    (net (code "272") (name "unconnected-(SJ45-Pad1)") (class "Default")
      (node (ref "SJ45") (pin "1") (pinfunction "1_1") (pintype "passive"))
    )
    (net (code "273") (name "unconnected-(SJ45-Pad2)") (class "Default")
      (node (ref "SJ45") (pin "2") (pinfunction "2_2") (pintype "passive"))
    )
    (net (code "274") (name "unconnected-(SJ46-Pad1)") (class "Default")
      (node (ref "SJ46") (pin "1") (pinfunction "1_1") (pintype "passive"))
    )
    (net (code "275") (name "unconnected-(SJ46-Pad2)") (class "Default")
      (node (ref "SJ46") (pin "2") (pinfunction "2_2") (pintype "passive"))
    )
    (net (code "276") (name "unconnected-(SJ47-Pad1)") (class "Default")
      (node (ref "SJ47") (pin "1") (pinfunction "1_1") (pintype "passive"))
    )
    (net (code "277") (name "unconnected-(SJ47-Pad2)") (class "Default")
      (node (ref "SJ47") (pin "2") (pinfunction "2_2") (pintype "passive"))
    )
    (net (code "278") (name "unconnected-(SJ47-Pad3)") (class "Default")
      (node (ref "SJ47") (pin "3") (pinfunction "3_3") (pintype "passive"))
    )
    (net (code "279") (name "unconnected-(SJ48-Pad1)") (class "Default")
      (node (ref "SJ48") (pin "1") (pinfunction "1_1") (pintype "passive"))
    )
    (net (code "280") (name "unconnected-(SJ48-Pad2)") (class "Default")
      (node (ref "SJ48") (pin "2") (pinfunction "2_2") (pintype "passive"))
    )
    (net (code "281") (name "unconnected-(SJ48-Pad3)") (class "Default")
      (node (ref "SJ48") (pin "3") (pinfunction "3_3") (pintype "passive"))
    )
    (net (code "282") (name "unconnected-(SJ73-Pad1)") (class "Default")
      (node (ref "SJ73") (pin "1") (pinfunction "1_1") (pintype "passive"))
    )
    (net (code "283") (name "unconnected-(SJ73-Pad2)") (class "Default")
      (node (ref "SJ73") (pin "2") (pinfunction "2_2") (pintype "passive"))
    )
    (net (code "284") (name "unconnected-(SJ73-Pad3)") (class "Default")
      (node (ref "SJ73") (pin "3") (pinfunction "3_3") (pintype "passive"))
    )
    (net (code "285") (name "unconnected-(SJ74-Pad1)") (class "Default")
      (node (ref "SJ74") (pin "1") (pinfunction "1_1") (pintype "passive"))
    )
    (net (code "286") (name "unconnected-(SJ74-Pad2)") (class "Default")
      (node (ref "SJ74") (pin "2") (pinfunction "2_2") (pintype "passive"))
    )
    (net (code "287") (name "unconnected-(SJ74-Pad3)") (class "Default")
      (node (ref "SJ74") (pin "3") (pinfunction "3_3") (pintype "passive"))
    )
    (net (code "288") (name "unconnected-(SJ75-Pad1)") (class "Default")
      (node (ref "SJ75") (pin "1") (pinfunction "1_1") (pintype "passive"))
    )
    (net (code "289") (name "unconnected-(SJ75-Pad2)") (class "Default")
      (node (ref "SJ75") (pin "2") (pinfunction "2_2") (pintype "passive"))
    )
    (net (code "290") (name "unconnected-(SJ75-Pad3)") (class "Default")
      (node (ref "SJ75") (pin "3") (pinfunction "3_3") (pintype "passive"))
    )
    (net (code "291") (name "unconnected-(SJ76-Pad1)") (class "Default")
      (node (ref "SJ76") (pin "1") (pinfunction "1_1") (pintype "passive"))
    )
    (net (code "292") (name "unconnected-(SJ76-Pad2)") (class "Default")
      (node (ref "SJ76") (pin "2") (pinfunction "2_2") (pintype "passive"))
    )
    (net (code "293") (name "unconnected-(SJ76-Pad3)") (class "Default")
      (node (ref "SJ76") (pin "3") (pinfunction "3_3") (pintype "passive"))
    )
    (net (code "294") (name "unconnected-(SJ77-Pad1)") (class "Default")
      (node (ref "SJ77") (pin "1") (pinfunction "1_1") (pintype "passive"))
    )
    (net (code "295") (name "unconnected-(SJ77-Pad2)") (class "Default")
      (node (ref "SJ77") (pin "2") (pinfunction "2_2") (pintype "passive"))
    )
    (net (code "296") (name "unconnected-(SJ78-Pad1)") (class "Default")
      (node (ref "SJ78") (pin "1") (pinfunction "1_1") (pintype "passive"))
    )
    (net (code "297") (name "unconnected-(SJ78-Pad2)") (class "Default")
      (node (ref "SJ78") (pin "2") (pinfunction "2_2") (pintype "passive"))
    )
    (net (code "298") (name "unconnected-(SJ79-Pad1)") (class "Default")
      (node (ref "SJ79") (pin "1") (pinfunction "1_1") (pintype "passive"))
    )
    (net (code "299") (name "unconnected-(SJ79-Pad2)") (class "Default")
      (node (ref "SJ79") (pin "2") (pinfunction "2_2") (pintype "passive"))
    )
    (net (code "300") (name "unconnected-(SJ80-Pad1)") (class "Default")
      (node (ref "SJ80") (pin "1") (pinfunction "1_1") (pintype "passive"))
    )
    (net (code "301") (name "unconnected-(SJ80-Pad2)") (class "Default")
      (node (ref "SJ80") (pin "2") (pinfunction "2_2") (pintype "passive"))
    )
    (net (code "302") (name "unconnected-(SJ81-Pad1)") (class "Default")
      (node (ref "SJ81") (pin "1") (pinfunction "1_1") (pintype "passive"))
    )
    (net (code "303") (name "unconnected-(SJ81-Pad2)") (class "Default")
      (node (ref "SJ81") (pin "2") (pinfunction "2_2") (pintype "passive"))
    )
    (net (code "304") (name "unconnected-(SJ82-Pad1)") (class "Default")
      (node (ref "SJ82") (pin "1") (pinfunction "1_1") (pintype "passive"))
    )
    (net (code "305") (name "unconnected-(SJ82-Pad2)") (class "Default")
      (node (ref "SJ82") (pin "2") (pinfunction "2_2") (pintype "passive"))
    )
    (net (code "306") (name "unconnected-(SJ83-Pad1)") (class "Default")
      (node (ref "SJ83") (pin "1") (pinfunction "1_1") (pintype "passive"))
    )
    (net (code "307") (name "unconnected-(SJ83-Pad2)") (class "Default")
      (node (ref "SJ83") (pin "2") (pinfunction "2_2") (pintype "passive"))
    )
    (net (code "308") (name "unconnected-(SJ83-Pad3)") (class "Default")
      (node (ref "SJ83") (pin "3") (pinfunction "3_3") (pintype "passive"))
    )
    (net (code "309") (name "unconnected-(SJ84-Pad1)") (class "Default")
      (node (ref "SJ84") (pin "1") (pinfunction "1_1") (pintype "passive"))
    )
    (net (code "310") (name "unconnected-(SJ84-Pad2)") (class "Default")
      (node (ref "SJ84") (pin "2") (pinfunction "2_2") (pintype "passive"))
    )
    (net (code "311") (name "unconnected-(SJ84-Pad3)") (class "Default")
      (node (ref "SJ84") (pin "3") (pinfunction "3_3") (pintype "passive"))
    )
    (net (code "312") (name "unconnected-(SJ85-Pad1)") (class "Default")
      (node (ref "SJ85") (pin "1") (pinfunction "1_1") (pintype "passive"))
    )
    (net (code "313") (name "unconnected-(SJ85-Pad2)") (class "Default")
      (node (ref "SJ85") (pin "2") (pinfunction "2_2") (pintype "passive"))
    )
    (net (code "314") (name "unconnected-(SJ86-Pad1)") (class "Default")
      (node (ref "SJ86") (pin "1") (pinfunction "1_1") (pintype "passive"))
    )
    (net (code "315") (name "unconnected-(SJ86-Pad2)") (class "Default")
      (node (ref "SJ86") (pin "2") (pinfunction "2_2") (pintype "passive"))
    )
    (net (code "316") (name "unconnected-(SJ87-Pad1)") (class "Default")
      (node (ref "SJ87") (pin "1") (pinfunction "1_1") (pintype "passive"))
    )
    (net (code "317") (name "unconnected-(SJ87-Pad2)") (class "Default")
      (node (ref "SJ87") (pin "2") (pinfunction "2_2") (pintype "passive"))
    )
    (net (code "318") (name "unconnected-(SJ87-Pad3)") (class "Default")
      (node (ref "SJ87") (pin "3") (pinfunction "3_3") (pintype "passive"))
    )
    (net (code "319") (name "unconnected-(SJ88-Pad1)") (class "Default")
      (node (ref "SJ88") (pin "1") (pinfunction "1_1") (pintype "passive"))
    )
    (net (code "320") (name "unconnected-(SJ88-Pad2)") (class "Default")
      (node (ref "SJ88") (pin "2") (pinfunction "2_2") (pintype "passive"))
    )
    (net (code "321") (name "unconnected-(SJ88-Pad3)") (class "Default")
      (node (ref "SJ88") (pin "3") (pinfunction "3_3") (pintype "passive"))
    )
    (net (code "322") (name "unconnected-(SJ113-Pad1)") (class "Default")
      (node (ref "SJ113") (pin "1") (pinfunction "1_1") (pintype "passive"))
    )
    (net (code "323") (name "unconnected-(SJ113-Pad2)") (class "Default")
      (node (ref "SJ113") (pin "2") (pinfunction "2_2") (pintype "passive"))
    )
    (net (code "324") (name "unconnected-(SJ113-Pad3)") (class "Default")
      (node (ref "SJ113") (pin "3") (pinfunction "3_3") (pintype "passive"))
    )
    (net (code "325") (name "unconnected-(SJ114-Pad1)") (class "Default")
      (node (ref "SJ114") (pin "1") (pinfunction "1_1") (pintype "passive"))
    )
    (net (code "326") (name "unconnected-(SJ114-Pad2)") (class "Default")
      (node (ref "SJ114") (pin "2") (pinfunction "2_2") (pintype "passive"))
    )
    (net (code "327") (name "unconnected-(SJ114-Pad3)") (class "Default")
      (node (ref "SJ114") (pin "3") (pinfunction "3_3") (pintype "passive"))
    )
    (net (code "328") (name "unconnected-(SJ115-Pad1)") (class "Default")
      (node (ref "SJ115") (pin "1") (pinfunction "1_1") (pintype "passive"))
    )
    (net (code "329") (name "unconnected-(SJ115-Pad2)") (class "Default")
      (node (ref "SJ115") (pin "2") (pinfunction "2_2") (pintype "passive"))
    )
    (net (code "330") (name "unconnected-(SJ115-Pad3)") (class "Default")
      (node (ref "SJ115") (pin "3") (pinfunction "3_3") (pintype "passive"))
    )
    (net (code "331") (name "unconnected-(SJ116-Pad1)") (class "Default")
      (node (ref "SJ116") (pin "1") (pinfunction "1_1") (pintype "passive"))
    )
    (net (code "332") (name "unconnected-(SJ116-Pad2)") (class "Default")
      (node (ref "SJ116") (pin "2") (pinfunction "2_2") (pintype "passive"))
    )
    (net (code "333") (name "unconnected-(SJ116-Pad3)") (class "Default")
      (node (ref "SJ116") (pin "3") (pinfunction "3_3") (pintype "passive"))
    )
    (net (code "334") (name "unconnected-(SJ117-Pad1)") (class "Default")
      (node (ref "SJ117") (pin "1") (pinfunction "1_1") (pintype "passive"))
    )
    (net (code "335") (name "unconnected-(SJ117-Pad2)") (class "Default")
      (node (ref "SJ117") (pin "2") (pinfunction "2_2") (pintype "passive"))
    )
    (net (code "336") (name "unconnected-(SJ118-Pad1)") (class "Default")
      (node (ref "SJ118") (pin "1") (pinfunction "1_1") (pintype "passive"))
    )
    (net (code "337") (name "unconnected-(SJ118-Pad2)") (class "Default")
      (node (ref "SJ118") (pin "2") (pinfunction "2_2") (pintype "passive"))
    )
    (net (code "338") (name "unconnected-(SJ119-Pad1)") (class "Default")
      (node (ref "SJ119") (pin "1") (pinfunction "1_1") (pintype "passive"))
    )
    (net (code "339") (name "unconnected-(SJ119-Pad2)") (class "Default")
      (node (ref "SJ119") (pin "2") (pinfunction "2_2") (pintype "passive"))
    )
    (net (code "340") (name "unconnected-(SJ120-Pad1)") (class "Default")
      (node (ref "SJ120") (pin "1") (pinfunction "1_1") (pintype "passive"))
    )
    (net (code "341") (name "unconnected-(SJ120-Pad2)") (class "Default")
      (node (ref "SJ120") (pin "2") (pinfunction "2_2") (pintype "passive"))
    )
    (net (code "342") (name "unconnected-(SJ121-Pad1)") (class "Default")
      (node (ref "SJ121") (pin "1") (pinfunction "1_1") (pintype "passive"))
    )
    (net (code "343") (name "unconnected-(SJ121-Pad2)") (class "Default")
      (node (ref "SJ121") (pin "2") (pinfunction "2_2") (pintype "passive"))
    )
    (net (code "344") (name "unconnected-(SJ122-Pad1)") (class "Default")
      (node (ref "SJ122") (pin "1") (pinfunction "1_1") (pintype "passive"))
    )
    (net (code "345") (name "unconnected-(SJ122-Pad2)") (class "Default")
      (node (ref "SJ122") (pin "2") (pinfunction "2_2") (pintype "passive"))
    )
    (net (code "346") (name "unconnected-(SJ123-Pad1)") (class "Default")
      (node (ref "SJ123") (pin "1") (pinfunction "1_1") (pintype "passive"))
    )
    (net (code "347") (name "unconnected-(SJ123-Pad2)") (class "Default")
      (node (ref "SJ123") (pin "2") (pinfunction "2_2") (pintype "passive"))
    )
    (net (code "348") (name "unconnected-(SJ123-Pad3)") (class "Default")
      (node (ref "SJ123") (pin "3") (pinfunction "3_3") (pintype "passive"))
    )
    (net (code "349") (name "unconnected-(SJ124-Pad1)") (class "Default")
      (node (ref "SJ124") (pin "1") (pinfunction "1_1") (pintype "passive"))
    )
    (net (code "350") (name "unconnected-(SJ124-Pad2)") (class "Default")
      (node (ref "SJ124") (pin "2") (pinfunction "2_2") (pintype "passive"))
    )
    (net (code "351") (name "unconnected-(SJ124-Pad3)") (class "Default")
      (node (ref "SJ124") (pin "3") (pinfunction "3_3") (pintype "passive"))
    )
    (net (code "352") (name "unconnected-(SJ125-Pad1)") (class "Default")
      (node (ref "SJ125") (pin "1") (pinfunction "1_1") (pintype "passive"))
    )
    (net (code "353") (name "unconnected-(SJ125-Pad2)") (class "Default")
      (node (ref "SJ125") (pin "2") (pinfunction "2_2") (pintype "passive"))
    )
    (net (code "354") (name "unconnected-(SJ126-Pad1)") (class "Default")
      (node (ref "SJ126") (pin "1") (pinfunction "1_1") (pintype "passive"))
    )
    (net (code "355") (name "unconnected-(SJ126-Pad2)") (class "Default")
      (node (ref "SJ126") (pin "2") (pinfunction "2_2") (pintype "passive"))
    )
    (net (code "356") (name "unconnected-(SJ127-Pad1)") (class "Default")
      (node (ref "SJ127") (pin "1") (pinfunction "1_1") (pintype "passive"))
    )
    (net (code "357") (name "unconnected-(SJ127-Pad2)") (class "Default")
      (node (ref "SJ127") (pin "2") (pinfunction "2_2") (pintype "passive"))
    )
    (net (code "358") (name "unconnected-(SJ127-Pad3)") (class "Default")
      (node (ref "SJ127") (pin "3") (pinfunction "3_3") (pintype "passive"))
    )
    (net (code "359") (name "unconnected-(SJ128-Pad1)") (class "Default")
      (node (ref "SJ128") (pin "1") (pinfunction "1_1") (pintype "passive"))
    )
    (net (code "360") (name "unconnected-(SJ128-Pad2)") (class "Default")
      (node (ref "SJ128") (pin "2") (pinfunction "2_2") (pintype "passive"))
    )
    (net (code "361") (name "unconnected-(SJ128-Pad3)") (class "Default")
      (node (ref "SJ128") (pin "3") (pinfunction "3_3") (pintype "passive"))
    )
    (net (code "362") (name "unconnected-(SJ153-Pad1)") (class "Default")
      (node (ref "SJ153") (pin "1") (pinfunction "1_1") (pintype "passive"))
    )
    (net (code "363") (name "unconnected-(SJ153-Pad2)") (class "Default")
      (node (ref "SJ153") (pin "2") (pinfunction "2_2") (pintype "passive"))
    )
    (net (code "364") (name "unconnected-(SJ153-Pad3)") (class "Default")
      (node (ref "SJ153") (pin "3") (pinfunction "3_3") (pintype "passive"))
    )
    (net (code "365") (name "unconnected-(SJ154-Pad1)") (class "Default")
      (node (ref "SJ154") (pin "1") (pinfunction "1_1") (pintype "passive"))
    )
    (net (code "366") (name "unconnected-(SJ154-Pad2)") (class "Default")
      (node (ref "SJ154") (pin "2") (pinfunction "2_2") (pintype "passive"))
    )
    (net (code "367") (name "unconnected-(SJ154-Pad3)") (class "Default")
      (node (ref "SJ154") (pin "3") (pinfunction "3_3") (pintype "passive"))
    )
    (net (code "368") (name "unconnected-(SJ155-Pad1)") (class "Default")
      (node (ref "SJ155") (pin "1") (pinfunction "1_1") (pintype "passive"))
    )
    (net (code "369") (name "unconnected-(SJ155-Pad2)") (class "Default")
      (node (ref "SJ155") (pin "2") (pinfunction "2_2") (pintype "passive"))
    )
    (net (code "370") (name "unconnected-(SJ155-Pad3)") (class "Default")
      (node (ref "SJ155") (pin "3") (pinfunction "3_3") (pintype "passive"))
    )
    (net (code "371") (name "unconnected-(SJ156-Pad1)") (class "Default")
      (node (ref "SJ156") (pin "1") (pinfunction "1_1") (pintype "passive"))
    )
    (net (code "372") (name "unconnected-(SJ156-Pad2)") (class "Default")
      (node (ref "SJ156") (pin "2") (pinfunction "2_2") (pintype "passive"))
    )
    (net (code "373") (name "unconnected-(SJ156-Pad3)") (class "Default")
      (node (ref "SJ156") (pin "3") (pinfunction "3_3") (pintype "passive"))
    )
    (net (code "374") (name "unconnected-(SJ157-Pad1)") (class "Default")
      (node (ref "SJ157") (pin "1") (pinfunction "1_1") (pintype "passive"))
    )
    (net (code "375") (name "unconnected-(SJ157-Pad2)") (class "Default")
      (node (ref "SJ157") (pin "2") (pinfunction "2_2") (pintype "passive"))
    )
    (net (code "376") (name "unconnected-(SJ158-Pad1)") (class "Default")
      (node (ref "SJ158") (pin "1") (pinfunction "1_1") (pintype "passive"))
    )
    (net (code "377") (name "unconnected-(SJ158-Pad2)") (class "Default")
      (node (ref "SJ158") (pin "2") (pinfunction "2_2") (pintype "passive"))
    )
    (net (code "378") (name "unconnected-(SJ159-Pad1)") (class "Default")
      (node (ref "SJ159") (pin "1") (pinfunction "1_1") (pintype "passive"))
    )
    (net (code "379") (name "unconnected-(SJ159-Pad2)") (class "Default")
      (node (ref "SJ159") (pin "2") (pinfunction "2_2") (pintype "passive"))
    )
    (net (code "380") (name "unconnected-(SJ160-Pad1)") (class "Default")
      (node (ref "SJ160") (pin "1") (pinfunction "1_1") (pintype "passive"))
    )
    (net (code "381") (name "unconnected-(SJ160-Pad2)") (class "Default")
      (node (ref "SJ160") (pin "2") (pinfunction "2_2") (pintype "passive"))
    )
    (net (code "382") (name "unconnected-(SJ161-Pad1)") (class "Default")
      (node (ref "SJ161") (pin "1") (pinfunction "1_1") (pintype "passive"))
    )
    (net (code "383") (name "unconnected-(SJ161-Pad2)") (class "Default")
      (node (ref "SJ161") (pin "2") (pinfunction "2_2") (pintype "passive"))
    )
    (net (code "384") (name "unconnected-(SJ162-Pad1)") (class "Default")
      (node (ref "SJ162") (pin "1") (pinfunction "1_1") (pintype "passive"))
    )
    (net (code "385") (name "unconnected-(SJ162-Pad2)") (class "Default")
      (node (ref "SJ162") (pin "2") (pinfunction "2_2") (pintype "passive"))
    )
    (net (code "386") (name "unconnected-(SJ163-Pad1)") (class "Default")
      (node (ref "SJ163") (pin "1") (pinfunction "1_1") (pintype "passive"))
    )
    (net (code "387") (name "unconnected-(SJ163-Pad2)") (class "Default")
      (node (ref "SJ163") (pin "2") (pinfunction "2_2") (pintype "passive"))
    )
    (net (code "388") (name "unconnected-(SJ163-Pad3)") (class "Default")
      (node (ref "SJ163") (pin "3") (pinfunction "3_3") (pintype "passive"))
    )
    (net (code "389") (name "unconnected-(SJ164-Pad1)") (class "Default")
      (node (ref "SJ164") (pin "1") (pinfunction "1_1") (pintype "passive"))
    )
    (net (code "390") (name "unconnected-(SJ164-Pad2)") (class "Default")
      (node (ref "SJ164") (pin "2") (pinfunction "2_2") (pintype "passive"))
    )
    (net (code "391") (name "unconnected-(SJ164-Pad3)") (class "Default")
      (node (ref "SJ164") (pin "3") (pinfunction "3_3") (pintype "passive"))
    )
    (net (code "392") (name "unconnected-(SJ165-Pad1)") (class "Default")
      (node (ref "SJ165") (pin "1") (pinfunction "1_1") (pintype "passive"))
    )
    (net (code "393") (name "unconnected-(SJ165-Pad2)") (class "Default")
      (node (ref "SJ165") (pin "2") (pinfunction "2_2") (pintype "passive"))
    )
    (net (code "394") (name "unconnected-(SJ166-Pad1)") (class "Default")
      (node (ref "SJ166") (pin "1") (pinfunction "1_1") (pintype "passive"))
    )
    (net (code "395") (name "unconnected-(SJ166-Pad2)") (class "Default")
      (node (ref "SJ166") (pin "2") (pinfunction "2_2") (pintype "passive"))
    )
    (net (code "396") (name "unconnected-(SJ167-Pad1)") (class "Default")
      (node (ref "SJ167") (pin "1") (pinfunction "1_1") (pintype "passive"))
    )
    (net (code "397") (name "unconnected-(SJ167-Pad2)") (class "Default")
      (node (ref "SJ167") (pin "2") (pinfunction "2_2") (pintype "passive"))
    )
    (net (code "398") (name "unconnected-(SJ167-Pad3)") (class "Default")
      (node (ref "SJ167") (pin "3") (pinfunction "3_3") (pintype "passive"))
    )
    (net (code "399") (name "unconnected-(SJ168-Pad1)") (class "Default")
      (node (ref "SJ168") (pin "1") (pinfunction "1_1") (pintype "passive"))
    )
    (net (code "400") (name "unconnected-(SJ168-Pad2)") (class "Default")
      (node (ref "SJ168") (pin "2") (pinfunction "2_2") (pintype "passive"))
    )
    (net (code "401") (name "unconnected-(SJ168-Pad3)") (class "Default")
      (node (ref "SJ168") (pin "3") (pinfunction "3_3") (pintype "passive"))
    )
    (net (code "402") (name "unconnected-(SJ193-Pad1)") (class "Default")
      (node (ref "SJ193") (pin "1") (pinfunction "1_1") (pintype "passive"))
    )
    (net (code "403") (name "unconnected-(SJ193-Pad2)") (class "Default")
      (node (ref "SJ193") (pin "2") (pinfunction "2_2") (pintype "passive"))
    )
    (net (code "404") (name "unconnected-(SJ193-Pad3)") (class "Default")
      (node (ref "SJ193") (pin "3") (pinfunction "3_3") (pintype "passive"))
    )
    (net (code "405") (name "unconnected-(SJ194-Pad1)") (class "Default")
      (node (ref "SJ194") (pin "1") (pinfunction "1_1") (pintype "passive"))
    )
    (net (code "406") (name "unconnected-(SJ194-Pad2)") (class "Default")
      (node (ref "SJ194") (pin "2") (pinfunction "2_2") (pintype "passive"))
    )
    (net (code "407") (name "unconnected-(SJ194-Pad3)") (class "Default")
      (node (ref "SJ194") (pin "3") (pinfunction "3_3") (pintype "passive"))
    )
    (net (code "408") (name "unconnected-(SJ195-Pad1)") (class "Default")
      (node (ref "SJ195") (pin "1") (pinfunction "1_1") (pintype "passive"))
    )
    (net (code "409") (name "unconnected-(SJ195-Pad2)") (class "Default")
      (node (ref "SJ195") (pin "2") (pinfunction "2_2") (pintype "passive"))
    )
    (net (code "410") (name "unconnected-(SJ195-Pad3)") (class "Default")
      (node (ref "SJ195") (pin "3") (pinfunction "3_3") (pintype "passive"))
    )
    (net (code "411") (name "unconnected-(SJ196-Pad1)") (class "Default")
      (node (ref "SJ196") (pin "1") (pinfunction "1_1") (pintype "passive"))
    )
    (net (code "412") (name "unconnected-(SJ196-Pad2)") (class "Default")
      (node (ref "SJ196") (pin "2") (pinfunction "2_2") (pintype "passive"))
    )
    (net (code "413") (name "unconnected-(SJ196-Pad3)") (class "Default")
      (node (ref "SJ196") (pin "3") (pinfunction "3_3") (pintype "passive"))
    )
    (net (code "414") (name "unconnected-(SJ197-Pad1)") (class "Default")
      (node (ref "SJ197") (pin "1") (pinfunction "1_1") (pintype "passive"))
    )
    (net (code "415") (name "unconnected-(SJ197-Pad2)") (class "Default")
      (node (ref "SJ197") (pin "2") (pinfunction "2_2") (pintype "passive"))
    )
    (net (code "416") (name "unconnected-(SJ198-Pad1)") (class "Default")
      (node (ref "SJ198") (pin "1") (pinfunction "1_1") (pintype "passive"))
    )
    (net (code "417") (name "unconnected-(SJ198-Pad2)") (class "Default")
      (node (ref "SJ198") (pin "2") (pinfunction "2_2") (pintype "passive"))
    )
    (net (code "418") (name "unconnected-(SJ199-Pad1)") (class "Default")
      (node (ref "SJ199") (pin "1") (pinfunction "1_1") (pintype "passive"))
    )
    (net (code "419") (name "unconnected-(SJ199-Pad2)") (class "Default")
      (node (ref "SJ199") (pin "2") (pinfunction "2_2") (pintype "passive"))
    )
    (net (code "420") (name "unconnected-(SJ200-Pad1)") (class "Default")
      (node (ref "SJ200") (pin "1") (pinfunction "1_1") (pintype "passive"))
    )
    (net (code "421") (name "unconnected-(SJ200-Pad2)") (class "Default")
      (node (ref "SJ200") (pin "2") (pinfunction "2_2") (pintype "passive"))
    )
  )
)
